# dsp_board_power_amplifier.net
KiCad netlist of a schematic drawn in EAGLE
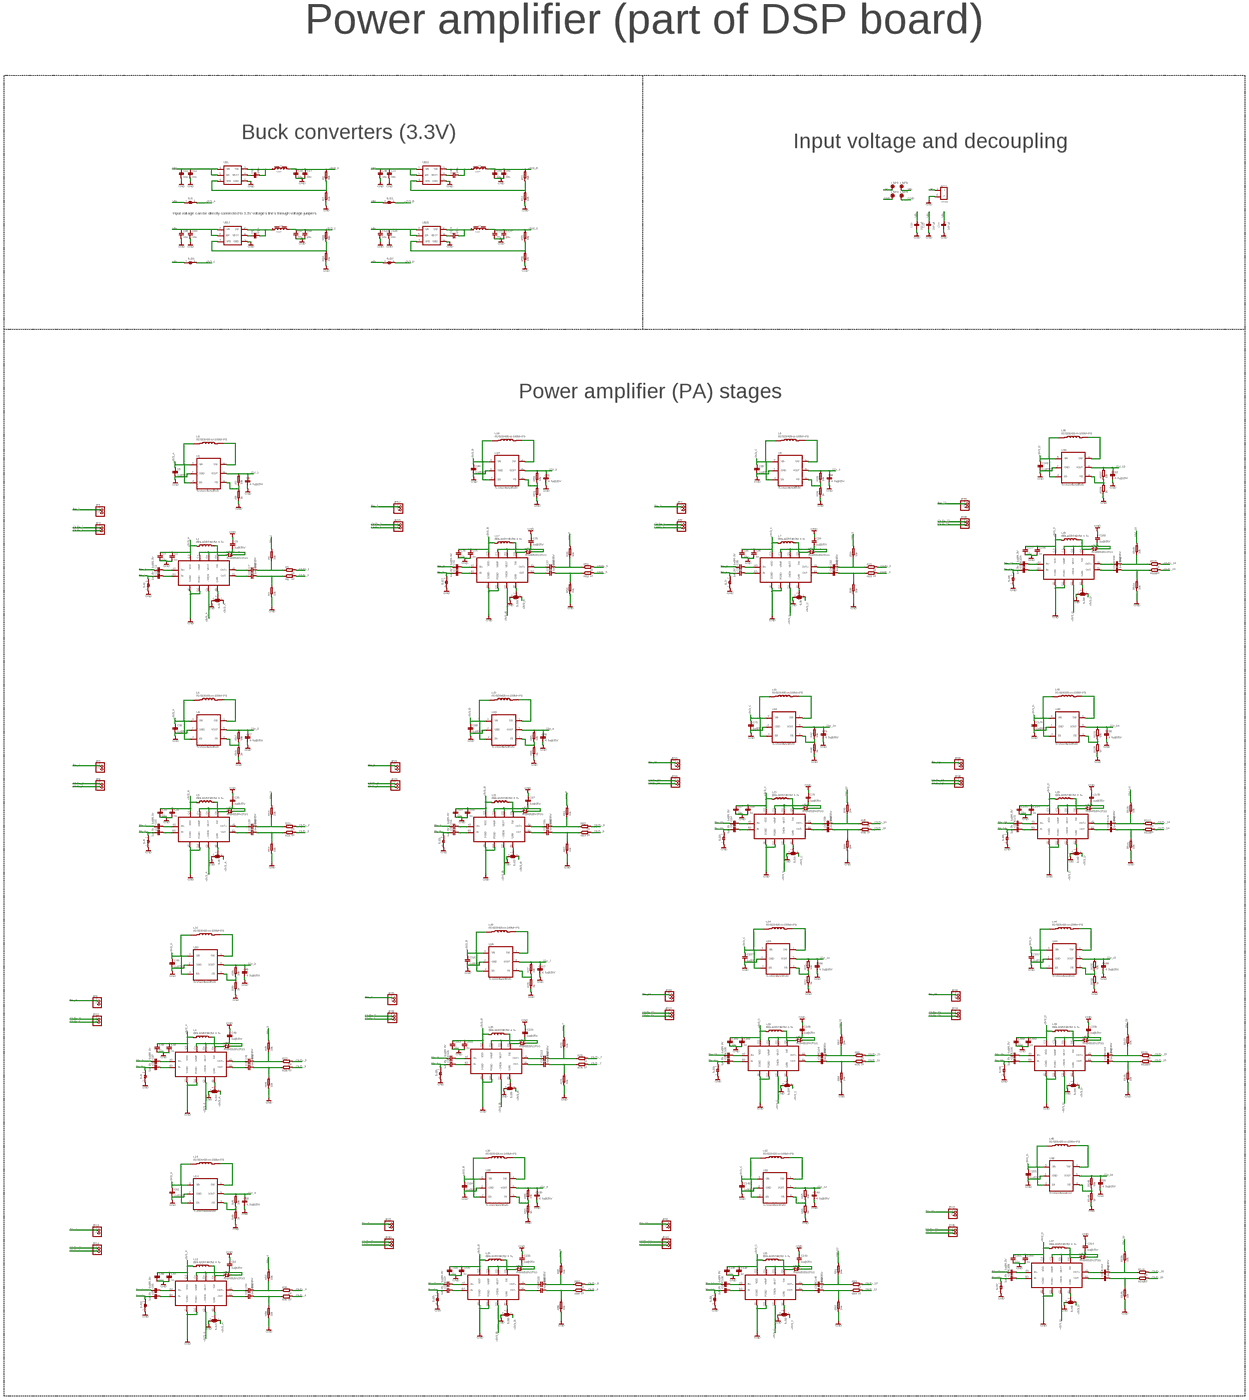
[diagram p0: schematic, sheet 1, overview]
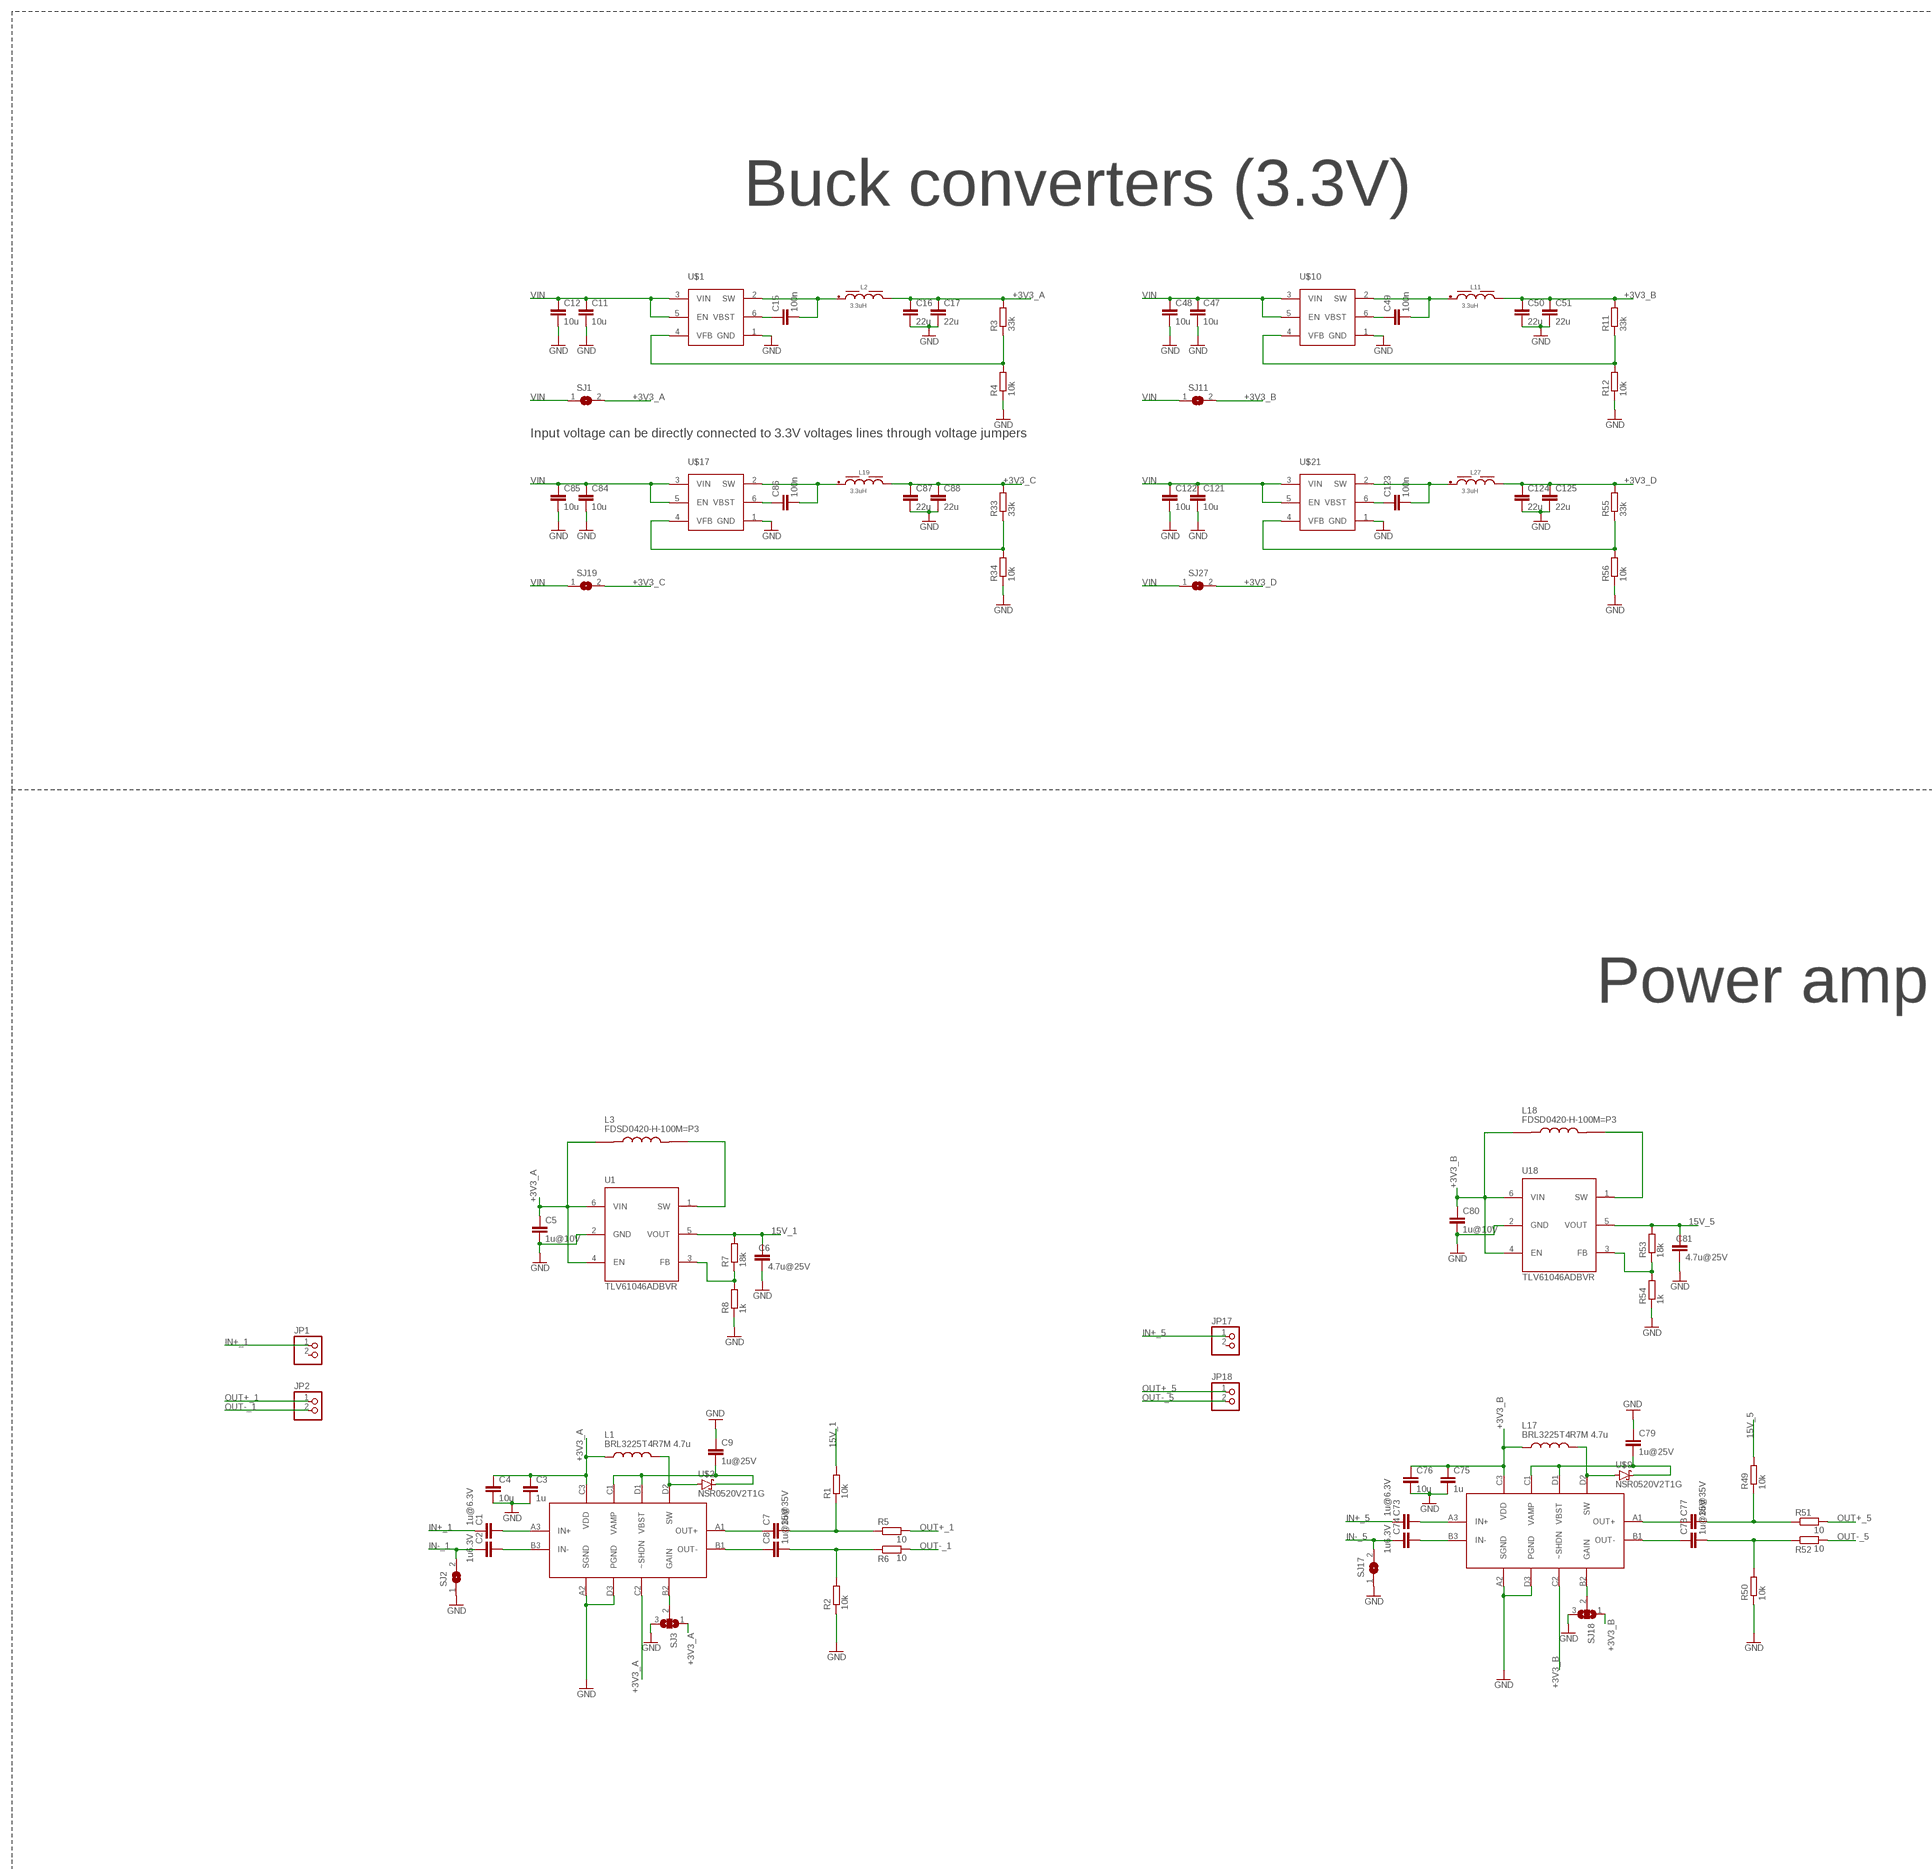
[diagram p1: schematic, sheet 1, part 1 of 6]
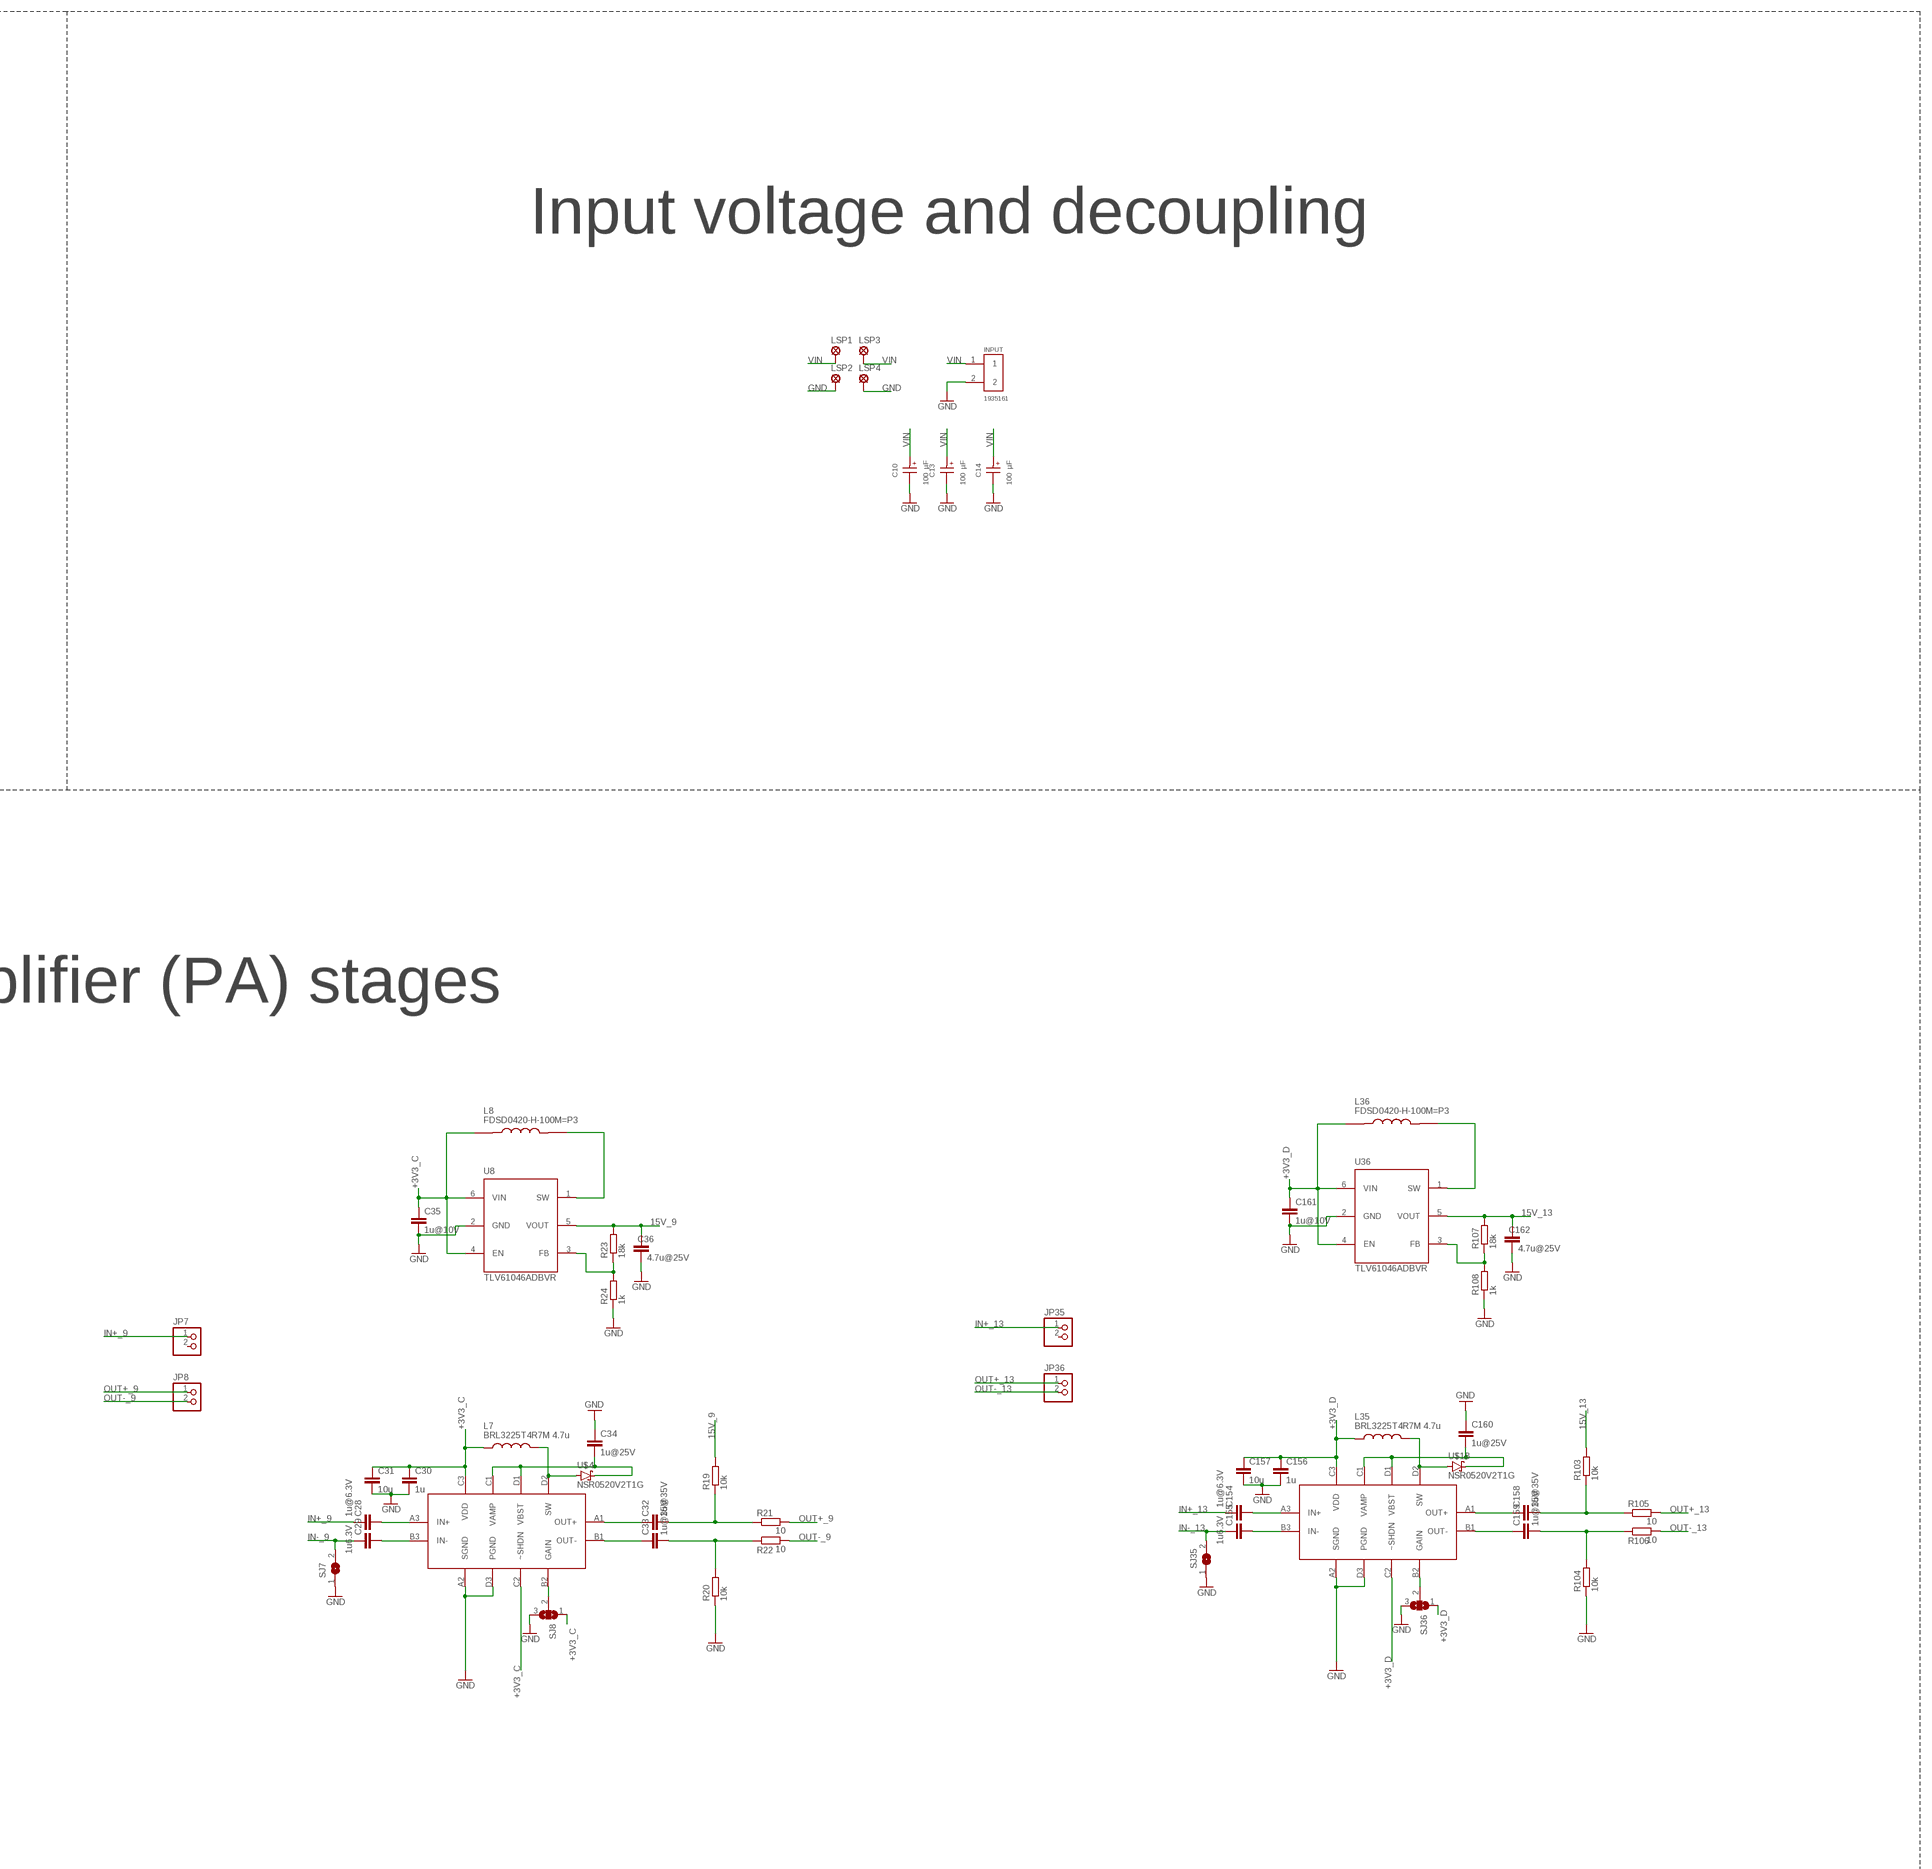
[diagram p2: schematic, sheet 1, part 2 of 6]
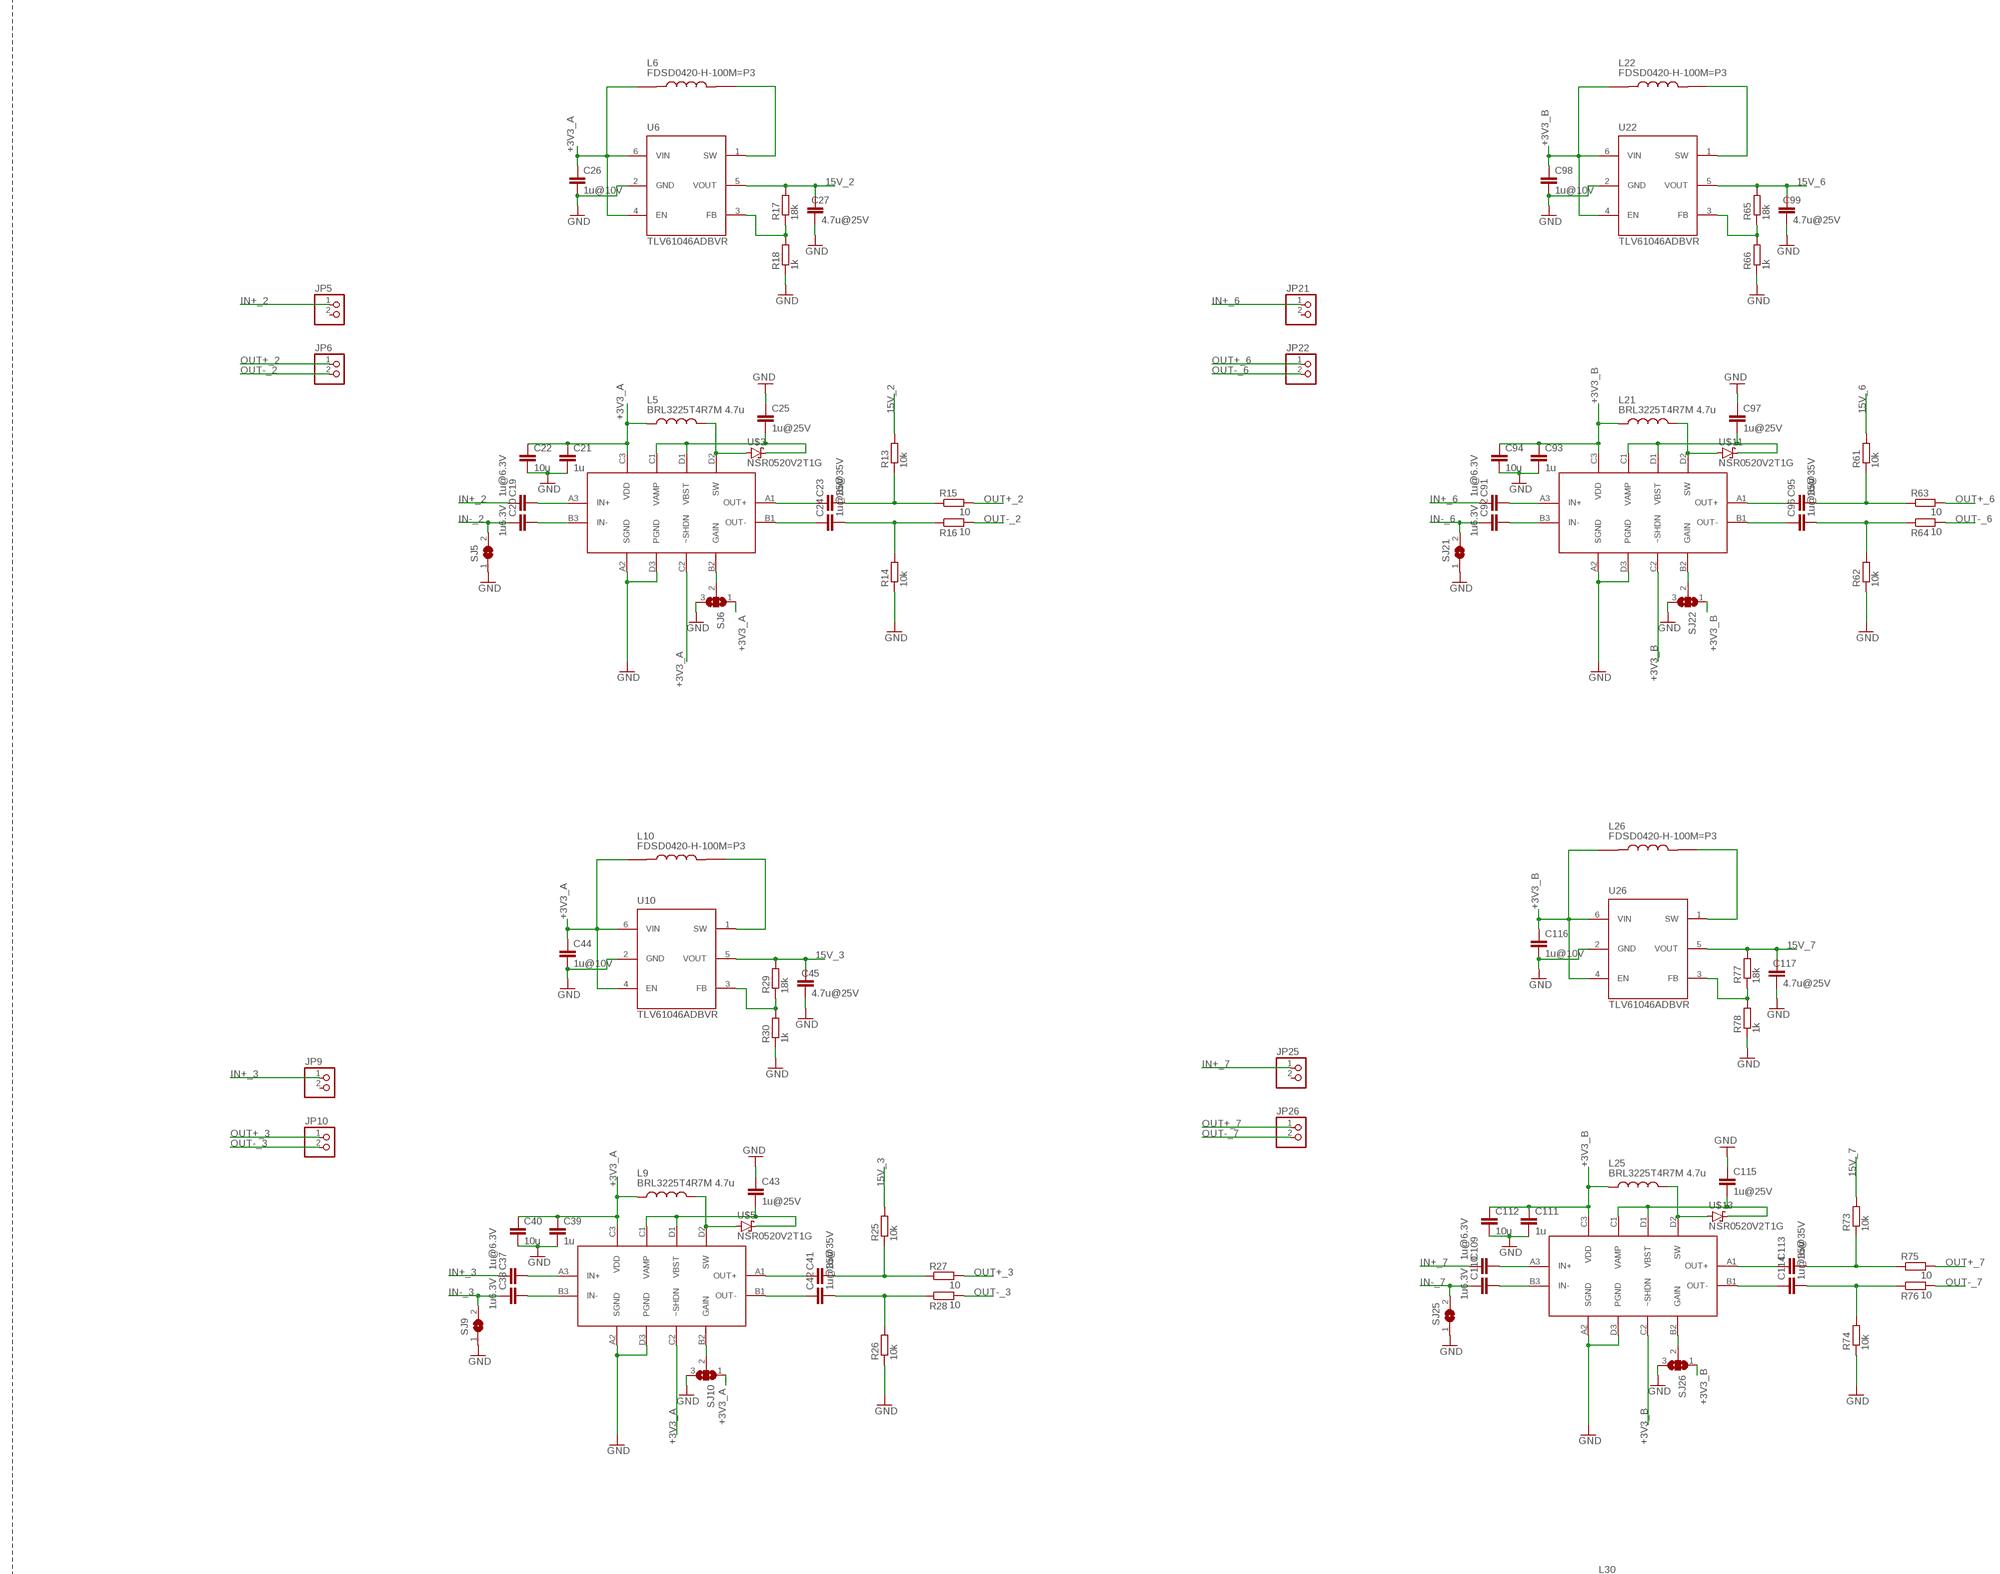
[diagram p3: schematic, sheet 1, part 3 of 6]
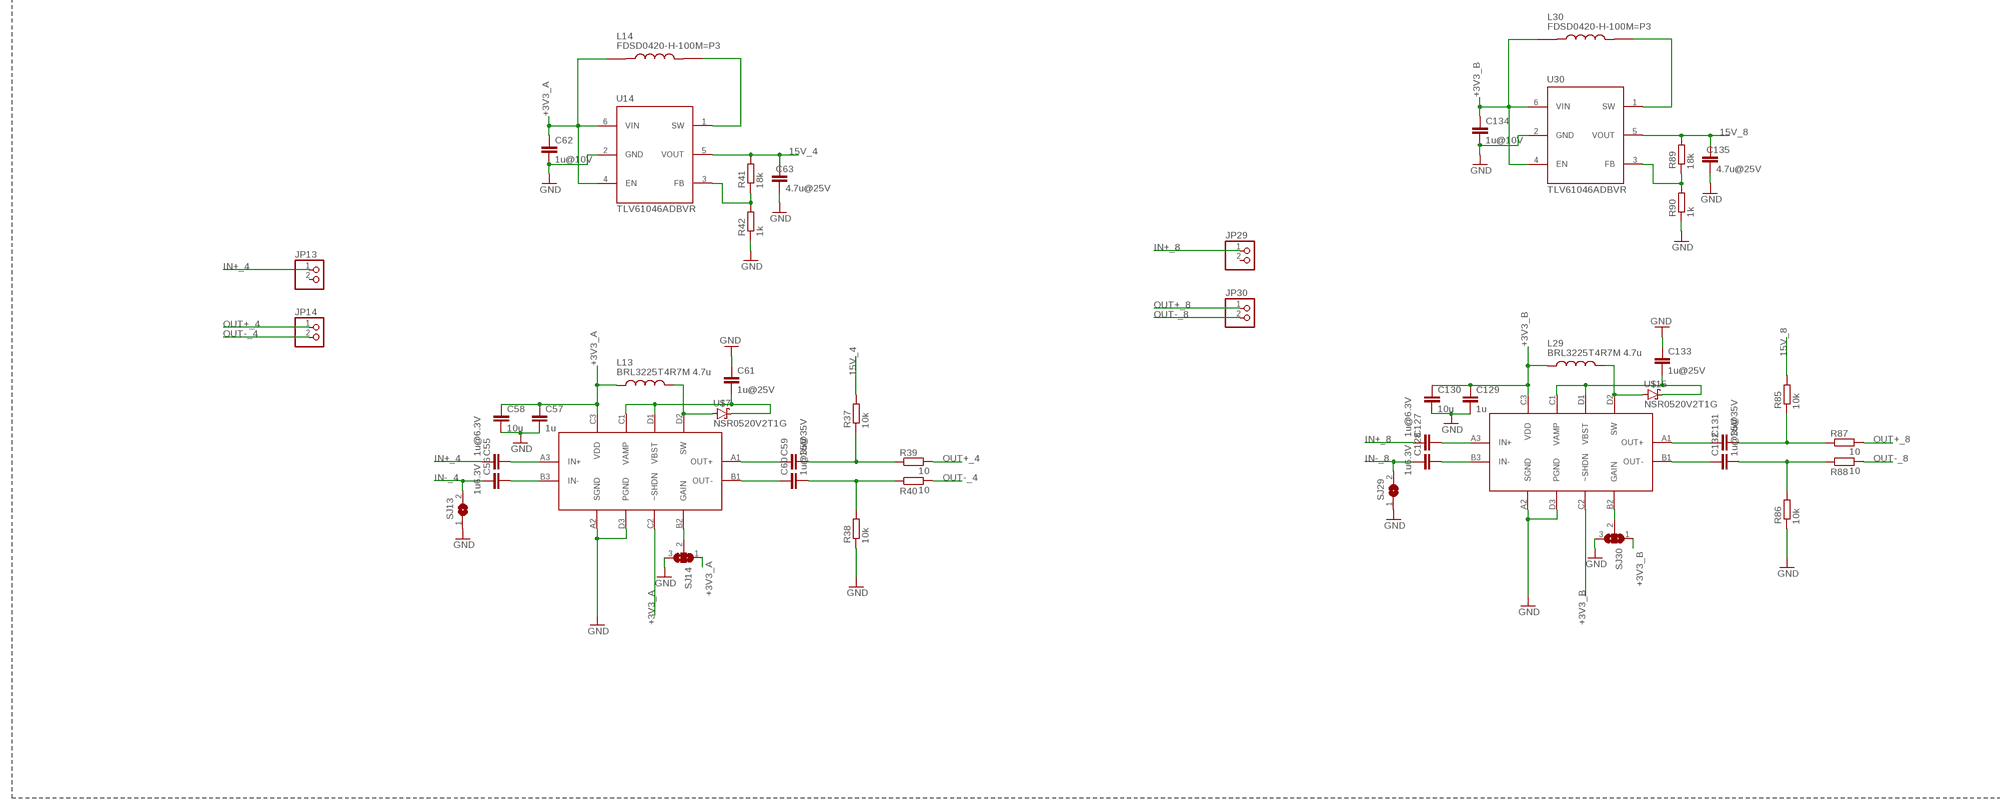
[diagram p4: schematic, sheet 1, part 4 of 6]
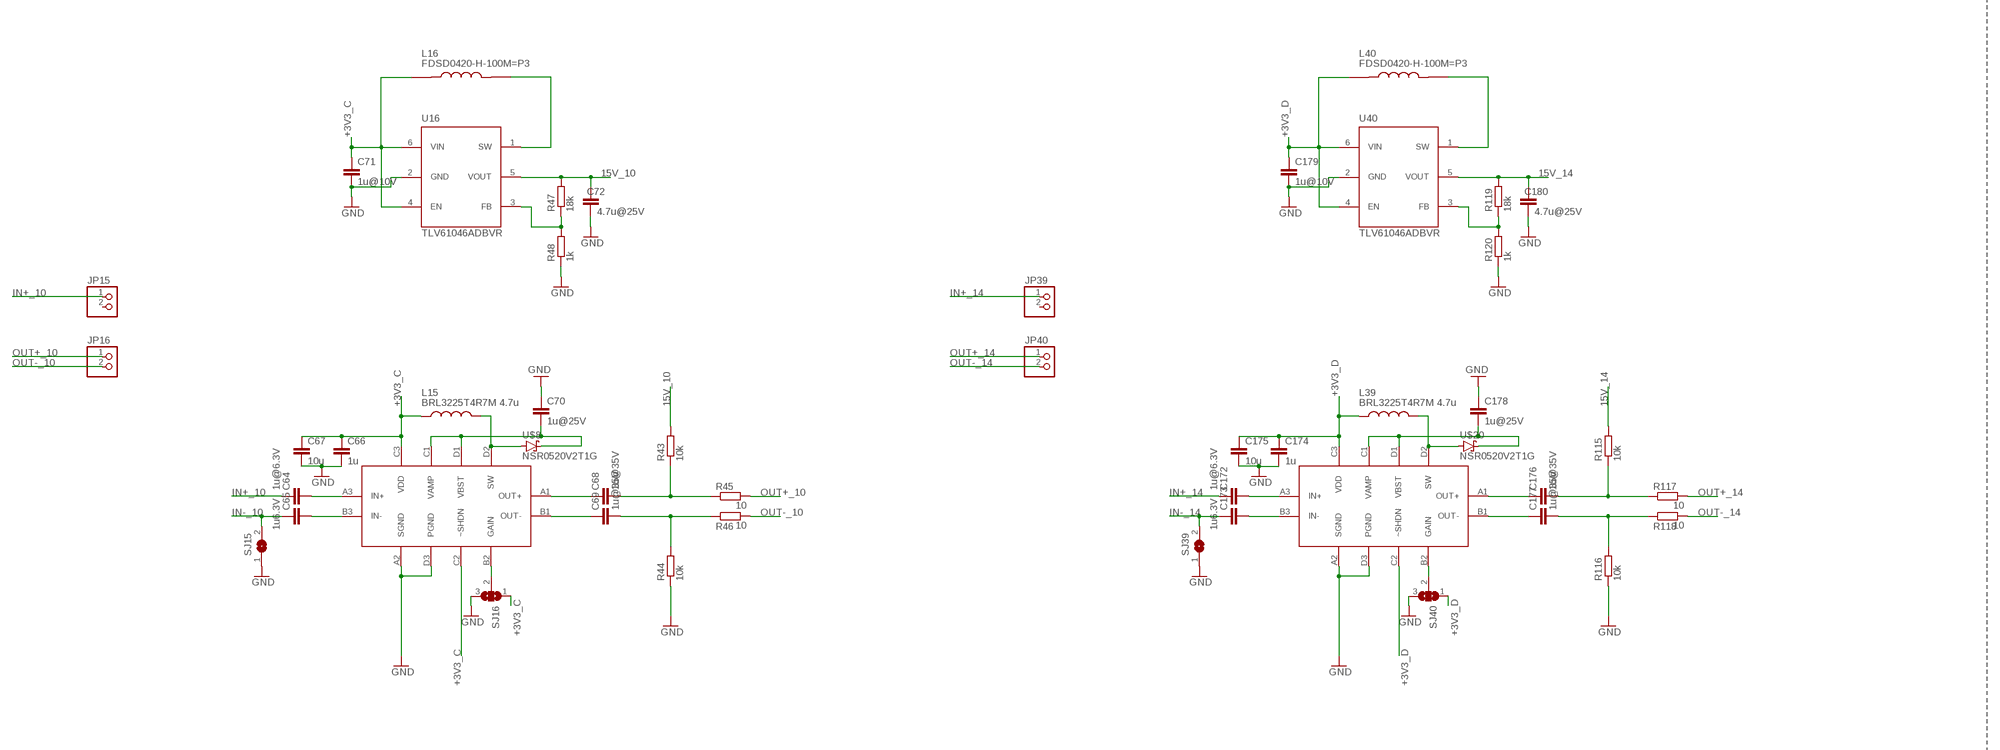
[diagram p5: schematic, sheet 1, part 5 of 6]
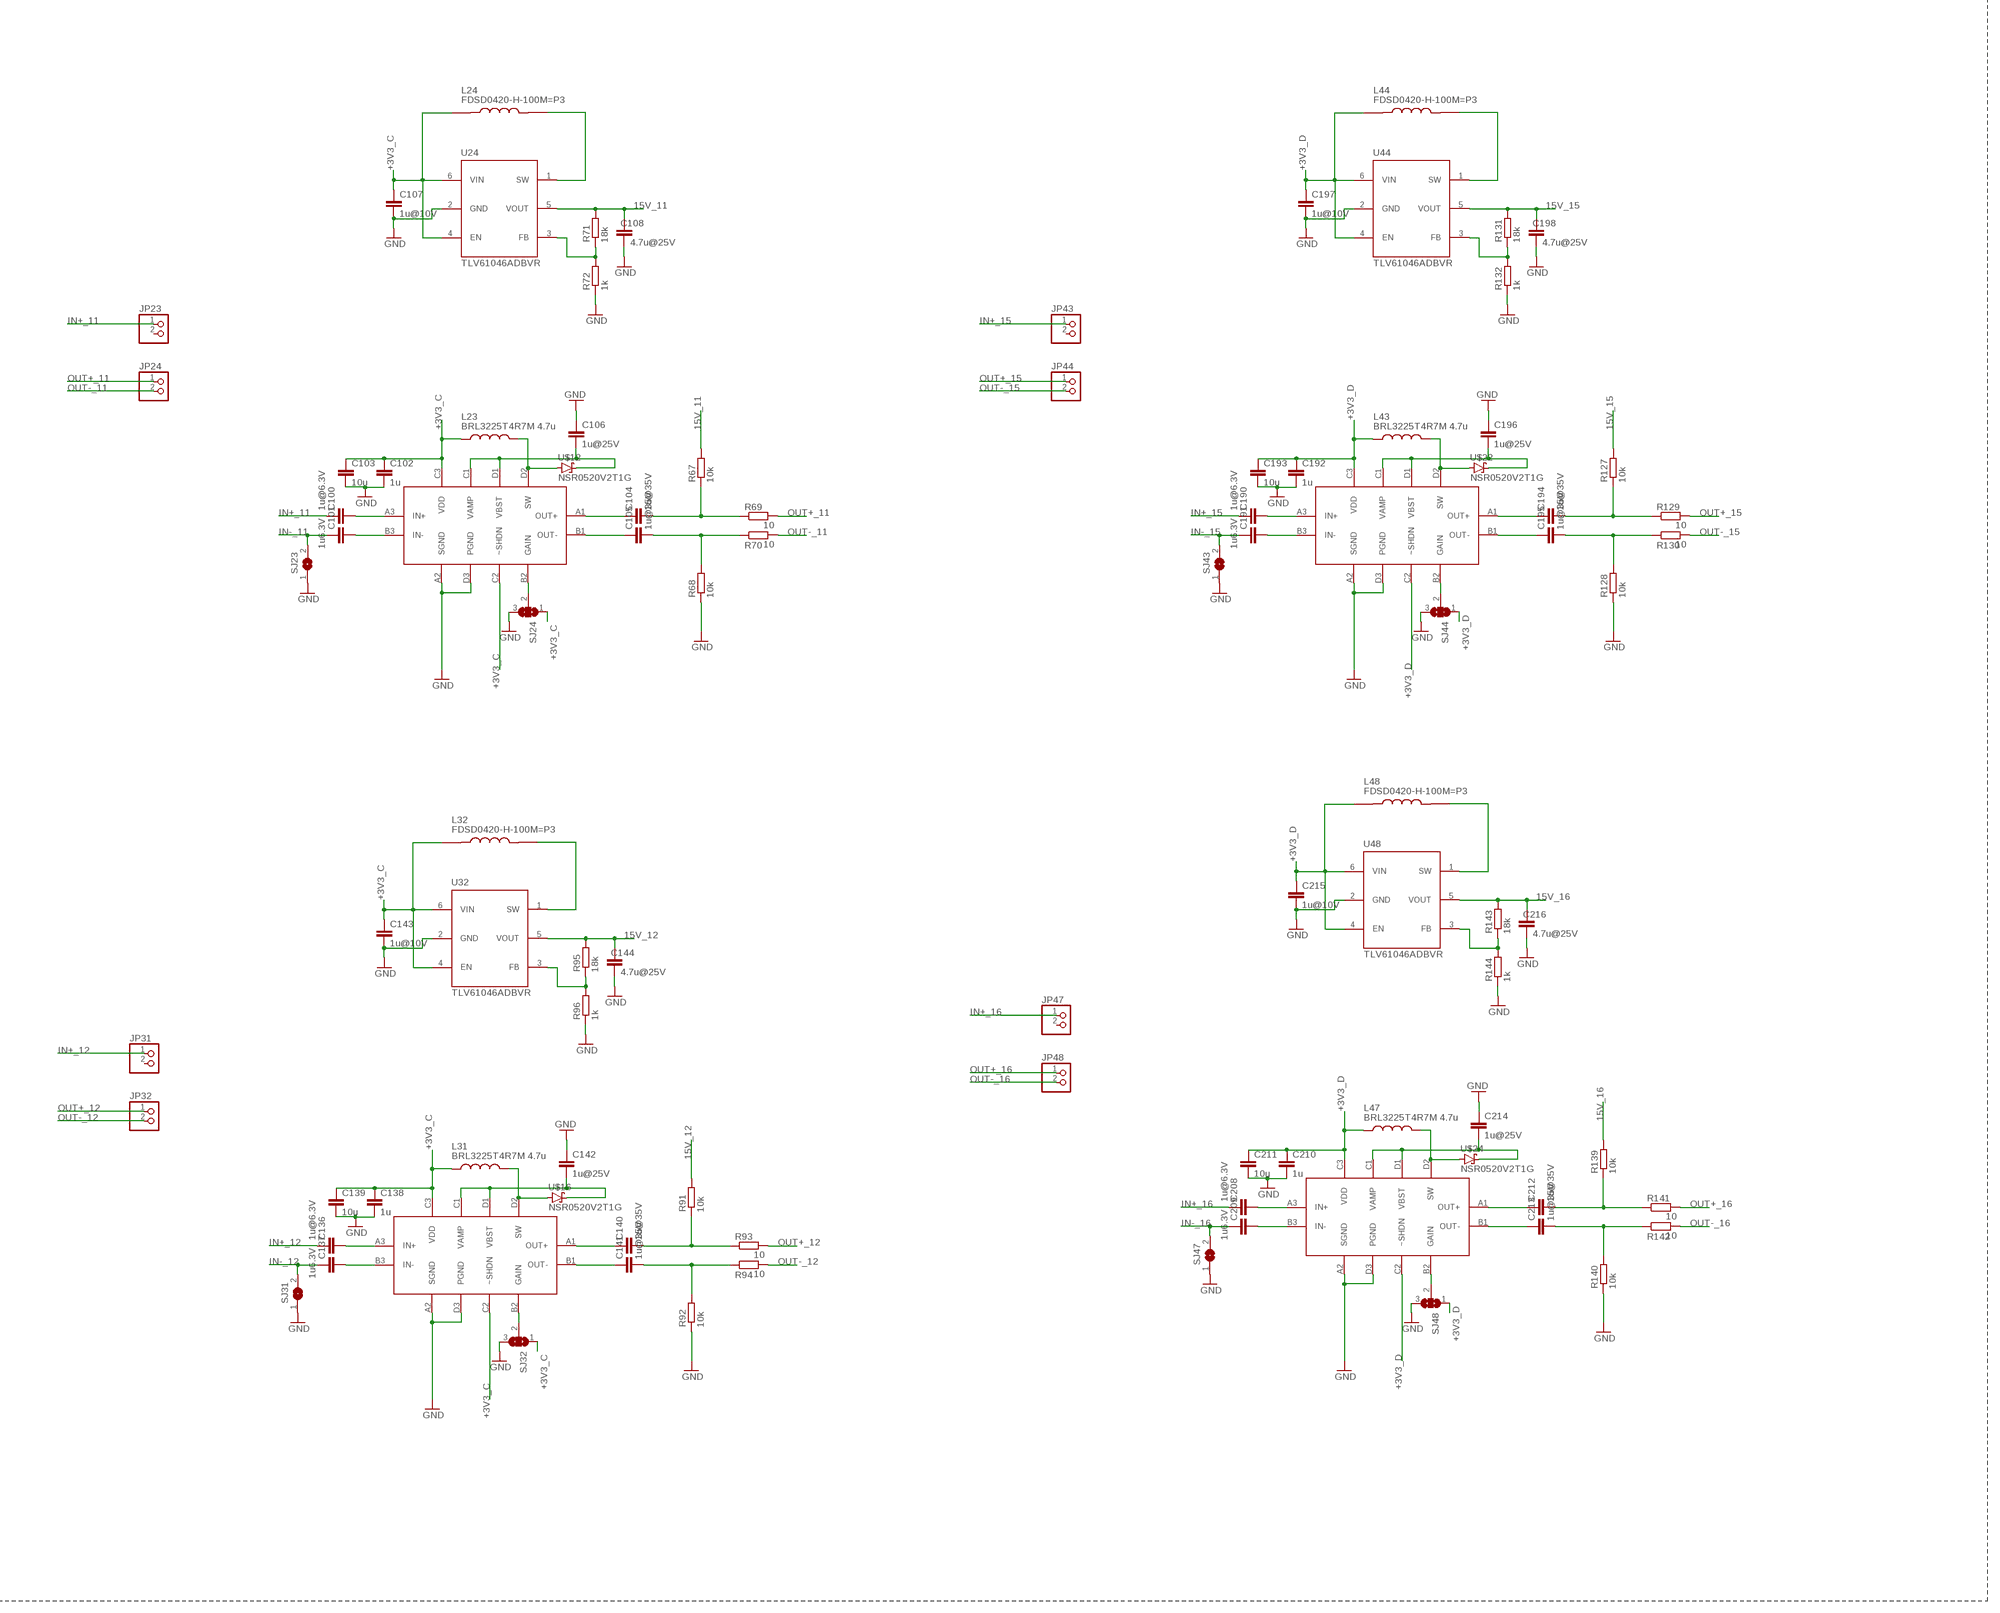
[diagram p6: schematic, sheet 1, part 6 of 6]

(export (version "E")
  (design (tool "Eeschema 10.0.6"))
  (components
    (comp (ref "C1")
      (value "1u@6.3V")
      (footprint "eagle-import:C0805")
      (libsource (lib "eagle-import") (part "C-EUC0805"))
    )
    (comp (ref "C2")
      (value "1u6.3V")
      (footprint "eagle-import:C0805")
      (libsource (lib "eagle-import") (part "C-EUC0805"))
    )
    (comp (ref "C3")
      (value "1u")
      (footprint "eagle-import:C0603")
      (libsource (lib "eagle-import") (part "C-EUC0603"))
    )
    (comp (ref "C4")
      (value "10u")
      (footprint "eagle-import:C0805")
      (libsource (lib "eagle-import") (part "C-EUC0805"))
    )
    (comp (ref "C5")
      (value "1u@10V")
      (footprint "eagle-import:C0603")
      (libsource (lib "eagle-import") (part "C-EUC0603"))
    )
    (comp (ref "C6")
      (value "4.7u@25V")
      (footprint "eagle-import:C0603")
      (libsource (lib "eagle-import") (part "C-EUC0603"))
    )
    (comp (ref "C7")
      (value "1u@35V")
      (footprint "eagle-import:C0603")
      (libsource (lib "eagle-import") (part "C-EUC0603"))
    )
    (comp (ref "C8")
      (value "1u@35V")
      (footprint "eagle-import:C0603")
      (libsource (lib "eagle-import") (part "C-EUC0603"))
    )
    (comp (ref "C9")
      (value "1u@25V")
      (footprint "eagle-import:C0603")
      (libsource (lib "eagle-import") (part "C-EUC0603"))
    )
    (comp (ref "C10")
      (value "100 µF")
      (footprint "eagle-import:WCAP-ASLU_6.3X7.7(DXL)")
      (libsource (lib "eagle-import") (part "WCAP-ASLU_6.3X7.7_865090445008"))
    )
    (comp (ref "C11")
      (value "10u")
      (footprint "eagle-import:C0805")
      (libsource (lib "eagle-import") (part "C-EUC0805"))
    )
    (comp (ref "C12")
      (value "10u")
      (footprint "eagle-import:C0805")
      (libsource (lib "eagle-import") (part "C-EUC0805"))
    )
    (comp (ref "C13")
      (value "100 µF")
      (footprint "eagle-import:WCAP-ASLU_6.3X7.7(DXL)")
      (libsource (lib "eagle-import") (part "WCAP-ASLU_6.3X7.7_865090445008"))
    )
    (comp (ref "C14")
      (value "100 µF")
      (footprint "eagle-import:WCAP-ASLU_6.3X7.7(DXL)")
      (libsource (lib "eagle-import") (part "WCAP-ASLU_6.3X7.7_865090445008"))
    )
    (comp (ref "C15")
      (value "100n")
      (footprint "eagle-import:C0603")
      (libsource (lib "eagle-import") (part "C-EUC0603"))
    )
    (comp (ref "C16")
      (value "22u")
      (footprint "eagle-import:C1206")
      (libsource (lib "eagle-import") (part "C-EUC1206"))
    )
    (comp (ref "C17")
      (value "22u")
      (footprint "eagle-import:C1206")
      (libsource (lib "eagle-import") (part "C-EUC1206"))
    )
    (comp (ref "C19")
      (value "1u@6.3V")
      (footprint "eagle-import:C0805")
      (libsource (lib "eagle-import") (part "C-EUC0805"))
    )
    (comp (ref "C20")
      (value "1u6.3V")
      (footprint "eagle-import:C0805")
      (libsource (lib "eagle-import") (part "C-EUC0805"))
    )
    (comp (ref "C21")
      (value "1u")
      (footprint "eagle-import:C0603")
      (libsource (lib "eagle-import") (part "C-EUC0603"))
    )
    (comp (ref "C22")
      (value "10u")
      (footprint "eagle-import:C0805")
      (libsource (lib "eagle-import") (part "C-EUC0805"))
    )
    (comp (ref "C23")
      (value "1u@35V")
      (footprint "eagle-import:C0603")
      (libsource (lib "eagle-import") (part "C-EUC0603"))
    )
    (comp (ref "C24")
      (value "1u@35V")
      (footprint "eagle-import:C0603")
      (libsource (lib "eagle-import") (part "C-EUC0603"))
    )
    (comp (ref "C25")
      (value "1u@25V")
      (footprint "eagle-import:C0603")
      (libsource (lib "eagle-import") (part "C-EUC0603"))
    )
    (comp (ref "C26")
      (value "1u@10V")
      (footprint "eagle-import:C0603")
      (libsource (lib "eagle-import") (part "C-EUC0603"))
    )
    (comp (ref "C27")
      (value "4.7u@25V")
      (footprint "eagle-import:C0603")
      (libsource (lib "eagle-import") (part "C-EUC0603"))
    )
    (comp (ref "C28")
      (value "1u@6.3V")
      (footprint "eagle-import:C0805")
      (libsource (lib "eagle-import") (part "C-EUC0805"))
    )
    (comp (ref "C29")
      (value "1u6.3V")
      (footprint "eagle-import:C0805")
      (libsource (lib "eagle-import") (part "C-EUC0805"))
    )
    (comp (ref "C30")
      (value "1u")
      (footprint "eagle-import:C0603")
      (libsource (lib "eagle-import") (part "C-EUC0603"))
    )
    (comp (ref "C31")
      (value "10u")
      (footprint "eagle-import:C0805")
      (libsource (lib "eagle-import") (part "C-EUC0805"))
    )
    (comp (ref "C32")
      (value "1u@35V")
      (footprint "eagle-import:C0603")
      (libsource (lib "eagle-import") (part "C-EUC0603"))
    )
    (comp (ref "C33")
      (value "1u@35V")
      (footprint "eagle-import:C0603")
      (libsource (lib "eagle-import") (part "C-EUC0603"))
    )
    (comp (ref "C34")
      (value "1u@25V")
      (footprint "eagle-import:C0603")
      (libsource (lib "eagle-import") (part "C-EUC0603"))
    )
    (comp (ref "C35")
      (value "1u@10V")
      (footprint "eagle-import:C0603")
      (libsource (lib "eagle-import") (part "C-EUC0603"))
    )
    (comp (ref "C36")
      (value "4.7u@25V")
      (footprint "eagle-import:C0603")
      (libsource (lib "eagle-import") (part "C-EUC0603"))
    )
    (comp (ref "C37")
      (value "1u@6.3V")
      (footprint "eagle-import:C0805")
      (libsource (lib "eagle-import") (part "C-EUC0805"))
    )
    (comp (ref "C38")
      (value "1u6.3V")
      (footprint "eagle-import:C0805")
      (libsource (lib "eagle-import") (part "C-EUC0805"))
    )
    (comp (ref "C39")
      (value "1u")
      (footprint "eagle-import:C0603")
      (libsource (lib "eagle-import") (part "C-EUC0603"))
    )
    (comp (ref "C40")
      (value "10u")
      (footprint "eagle-import:C0805")
      (libsource (lib "eagle-import") (part "C-EUC0805"))
    )
    (comp (ref "C41")
      (value "1u@35V")
      (footprint "eagle-import:C0603")
      (libsource (lib "eagle-import") (part "C-EUC0603"))
    )
    (comp (ref "C42")
      (value "1u@35V")
      (footprint "eagle-import:C0603")
      (libsource (lib "eagle-import") (part "C-EUC0603"))
    )
    (comp (ref "C43")
      (value "1u@25V")
      (footprint "eagle-import:C0603")
      (libsource (lib "eagle-import") (part "C-EUC0603"))
    )
    (comp (ref "C44")
      (value "1u@10V")
      (footprint "eagle-import:C0603")
      (libsource (lib "eagle-import") (part "C-EUC0603"))
    )
    (comp (ref "C45")
      (value "4.7u@25V")
      (footprint "eagle-import:C0603")
      (libsource (lib "eagle-import") (part "C-EUC0603"))
    )
    (comp (ref "C47")
      (value "10u")
      (footprint "eagle-import:C0805")
      (libsource (lib "eagle-import") (part "C-EUC0805"))
    )
    (comp (ref "C48")
      (value "10u")
      (footprint "eagle-import:C0805")
      (libsource (lib "eagle-import") (part "C-EUC0805"))
    )
    (comp (ref "C49")
      (value "100n")
      (footprint "eagle-import:C0603")
      (libsource (lib "eagle-import") (part "C-EUC0603"))
    )
    (comp (ref "C50")
      (value "22u")
      (footprint "eagle-import:C1206")
      (libsource (lib "eagle-import") (part "C-EUC1206"))
    )
    (comp (ref "C51")
      (value "22u")
      (footprint "eagle-import:C1206")
      (libsource (lib "eagle-import") (part "C-EUC1206"))
    )
    (comp (ref "C55")
      (value "1u@6.3V")
      (footprint "eagle-import:C0805")
      (libsource (lib "eagle-import") (part "C-EUC0805"))
    )
    (comp (ref "C56")
      (value "1u6.3V")
      (footprint "eagle-import:C0805")
      (libsource (lib "eagle-import") (part "C-EUC0805"))
    )
    (comp (ref "C57")
      (value "1u")
      (footprint "eagle-import:C0603")
      (libsource (lib "eagle-import") (part "C-EUC0603"))
    )
    (comp (ref "C58")
      (value "10u")
      (footprint "eagle-import:C0805")
      (libsource (lib "eagle-import") (part "C-EUC0805"))
    )
    (comp (ref "C59")
      (value "1u@35V")
      (footprint "eagle-import:C0603")
      (libsource (lib "eagle-import") (part "C-EUC0603"))
    )
    (comp (ref "C60")
      (value "1u@35V")
      (footprint "eagle-import:C0603")
      (libsource (lib "eagle-import") (part "C-EUC0603"))
    )
    (comp (ref "C61")
      (value "1u@25V")
      (footprint "eagle-import:C0603")
      (libsource (lib "eagle-import") (part "C-EUC0603"))
    )
    (comp (ref "C62")
      (value "1u@10V")
      (footprint "eagle-import:C0603")
      (libsource (lib "eagle-import") (part "C-EUC0603"))
    )
    (comp (ref "C63")
      (value "4.7u@25V")
      (footprint "eagle-import:C0603")
      (libsource (lib "eagle-import") (part "C-EUC0603"))
    )
    (comp (ref "C64")
      (value "1u@6.3V")
      (footprint "eagle-import:C0805")
      (libsource (lib "eagle-import") (part "C-EUC0805"))
    )
    (comp (ref "C65")
      (value "1u6.3V")
      (footprint "eagle-import:C0805")
      (libsource (lib "eagle-import") (part "C-EUC0805"))
    )
    (comp (ref "C66")
      (value "1u")
      (footprint "eagle-import:C0603")
      (libsource (lib "eagle-import") (part "C-EUC0603"))
    )
    (comp (ref "C67")
      (value "10u")
      (footprint "eagle-import:C0805")
      (libsource (lib "eagle-import") (part "C-EUC0805"))
    )
    (comp (ref "C68")
      (value "1u@35V")
      (footprint "eagle-import:C0603")
      (libsource (lib "eagle-import") (part "C-EUC0603"))
    )
    (comp (ref "C69")
      (value "1u@35V")
      (footprint "eagle-import:C0603")
      (libsource (lib "eagle-import") (part "C-EUC0603"))
    )
    (comp (ref "C70")
      (value "1u@25V")
      (footprint "eagle-import:C0603")
      (libsource (lib "eagle-import") (part "C-EUC0603"))
    )
    (comp (ref "C71")
      (value "1u@10V")
      (footprint "eagle-import:C0603")
      (libsource (lib "eagle-import") (part "C-EUC0603"))
    )
    (comp (ref "C72")
      (value "4.7u@25V")
      (footprint "eagle-import:C0603")
      (libsource (lib "eagle-import") (part "C-EUC0603"))
    )
    (comp (ref "C73")
      (value "1u@6.3V")
      (footprint "eagle-import:C0805")
      (libsource (lib "eagle-import") (part "C-EUC0805"))
    )
    (comp (ref "C74")
      (value "1u6.3V")
      (footprint "eagle-import:C0805")
      (libsource (lib "eagle-import") (part "C-EUC0805"))
    )
    (comp (ref "C75")
      (value "1u")
      (footprint "eagle-import:C0603")
      (libsource (lib "eagle-import") (part "C-EUC0603"))
    )
    (comp (ref "C76")
      (value "10u")
      (footprint "eagle-import:C0805")
      (libsource (lib "eagle-import") (part "C-EUC0805"))
    )
    (comp (ref "C77")
      (value "1u@35V")
      (footprint "eagle-import:C0603")
      (libsource (lib "eagle-import") (part "C-EUC0603"))
    )
    (comp (ref "C78")
      (value "1u@35V")
      (footprint "eagle-import:C0603")
      (libsource (lib "eagle-import") (part "C-EUC0603"))
    )
    (comp (ref "C79")
      (value "1u@25V")
      (footprint "eagle-import:C0603")
      (libsource (lib "eagle-import") (part "C-EUC0603"))
    )
    (comp (ref "C80")
      (value "1u@10V")
      (footprint "eagle-import:C0603")
      (libsource (lib "eagle-import") (part "C-EUC0603"))
    )
    (comp (ref "C81")
      (value "4.7u@25V")
      (footprint "eagle-import:C0603")
      (libsource (lib "eagle-import") (part "C-EUC0603"))
    )
    (comp (ref "C84")
      (value "10u")
      (footprint "eagle-import:C0805")
      (libsource (lib "eagle-import") (part "C-EUC0805"))
    )
    (comp (ref "C85")
      (value "10u")
      (footprint "eagle-import:C0805")
      (libsource (lib "eagle-import") (part "C-EUC0805"))
    )
    (comp (ref "C86")
      (value "100n")
      (footprint "eagle-import:C0603")
      (libsource (lib "eagle-import") (part "C-EUC0603"))
    )
    (comp (ref "C87")
      (value "22u")
      (footprint "eagle-import:C1206")
      (libsource (lib "eagle-import") (part "C-EUC1206"))
    )
    (comp (ref "C88")
      (value "22u")
      (footprint "eagle-import:C1206")
      (libsource (lib "eagle-import") (part "C-EUC1206"))
    )
    (comp (ref "C91")
      (value "1u@6.3V")
      (footprint "eagle-import:C0805")
      (libsource (lib "eagle-import") (part "C-EUC0805"))
    )
    (comp (ref "C92")
      (value "1u6.3V")
      (footprint "eagle-import:C0805")
      (libsource (lib "eagle-import") (part "C-EUC0805"))
    )
    (comp (ref "C93")
      (value "1u")
      (footprint "eagle-import:C0603")
      (libsource (lib "eagle-import") (part "C-EUC0603"))
    )
    (comp (ref "C94")
      (value "10u")
      (footprint "eagle-import:C0805")
      (libsource (lib "eagle-import") (part "C-EUC0805"))
    )
    (comp (ref "C95")
      (value "1u@35V")
      (footprint "eagle-import:C0603")
      (libsource (lib "eagle-import") (part "C-EUC0603"))
    )
    (comp (ref "C96")
      (value "1u@35V")
      (footprint "eagle-import:C0603")
      (libsource (lib "eagle-import") (part "C-EUC0603"))
    )
    (comp (ref "C97")
      (value "1u@25V")
      (footprint "eagle-import:C0603")
      (libsource (lib "eagle-import") (part "C-EUC0603"))
    )
    (comp (ref "C98")
      (value "1u@10V")
      (footprint "eagle-import:C0603")
      (libsource (lib "eagle-import") (part "C-EUC0603"))
    )
    (comp (ref "C99")
      (value "4.7u@25V")
      (footprint "eagle-import:C0603")
      (libsource (lib "eagle-import") (part "C-EUC0603"))
    )
    (comp (ref "C100")
      (value "1u@6.3V")
      (footprint "eagle-import:C0805")
      (libsource (lib "eagle-import") (part "C-EUC0805"))
    )
    (comp (ref "C101")
      (value "1u6.3V")
      (footprint "eagle-import:C0805")
      (libsource (lib "eagle-import") (part "C-EUC0805"))
    )
    (comp (ref "C102")
      (value "1u")
      (footprint "eagle-import:C0603")
      (libsource (lib "eagle-import") (part "C-EUC0603"))
    )
    (comp (ref "C103")
      (value "10u")
      (footprint "eagle-import:C0805")
      (libsource (lib "eagle-import") (part "C-EUC0805"))
    )
    (comp (ref "C104")
      (value "1u@35V")
      (footprint "eagle-import:C0603")
      (libsource (lib "eagle-import") (part "C-EUC0603"))
    )
    (comp (ref "C105")
      (value "1u@35V")
      (footprint "eagle-import:C0603")
      (libsource (lib "eagle-import") (part "C-EUC0603"))
    )
    (comp (ref "C106")
      (value "1u@25V")
      (footprint "eagle-import:C0603")
      (libsource (lib "eagle-import") (part "C-EUC0603"))
    )
    (comp (ref "C107")
      (value "1u@10V")
      (footprint "eagle-import:C0603")
      (libsource (lib "eagle-import") (part "C-EUC0603"))
    )
    (comp (ref "C108")
      (value "4.7u@25V")
      (footprint "eagle-import:C0603")
      (libsource (lib "eagle-import") (part "C-EUC0603"))
    )
    (comp (ref "C109")
      (value "1u@6.3V")
      (footprint "eagle-import:C0805")
      (libsource (lib "eagle-import") (part "C-EUC0805"))
    )
    (comp (ref "C110")
      (value "1u6.3V")
      (footprint "eagle-import:C0805")
      (libsource (lib "eagle-import") (part "C-EUC0805"))
    )
    (comp (ref "C111")
      (value "1u")
      (footprint "eagle-import:C0603")
      (libsource (lib "eagle-import") (part "C-EUC0603"))
    )
    (comp (ref "C112")
      (value "10u")
      (footprint "eagle-import:C0805")
      (libsource (lib "eagle-import") (part "C-EUC0805"))
    )
    (comp (ref "C113")
      (value "1u@35V")
      (footprint "eagle-import:C0603")
      (libsource (lib "eagle-import") (part "C-EUC0603"))
    )
    (comp (ref "C114")
      (value "1u@35V")
      (footprint "eagle-import:C0603")
      (libsource (lib "eagle-import") (part "C-EUC0603"))
    )
    (comp (ref "C115")
      (value "1u@25V")
      (footprint "eagle-import:C0603")
      (libsource (lib "eagle-import") (part "C-EUC0603"))
    )
    (comp (ref "C116")
      (value "1u@10V")
      (footprint "eagle-import:C0603")
      (libsource (lib "eagle-import") (part "C-EUC0603"))
    )
    (comp (ref "C117")
      (value "4.7u@25V")
      (footprint "eagle-import:C0603")
      (libsource (lib "eagle-import") (part "C-EUC0603"))
    )
    (comp (ref "C121")
      (value "10u")
      (footprint "eagle-import:C0805")
      (libsource (lib "eagle-import") (part "C-EUC0805"))
    )
    (comp (ref "C122")
      (value "10u")
      (footprint "eagle-import:C0805")
      (libsource (lib "eagle-import") (part "C-EUC0805"))
    )
    (comp (ref "C123")
      (value "100n")
      (footprint "eagle-import:C0603")
      (libsource (lib "eagle-import") (part "C-EUC0603"))
    )
    (comp (ref "C124")
      (value "22u")
      (footprint "eagle-import:C1206")
      (libsource (lib "eagle-import") (part "C-EUC1206"))
    )
    (comp (ref "C125")
      (value "22u")
      (footprint "eagle-import:C1206")
      (libsource (lib "eagle-import") (part "C-EUC1206"))
    )
    (comp (ref "C127")
      (value "1u@6.3V")
      (footprint "eagle-import:C0805")
      (libsource (lib "eagle-import") (part "C-EUC0805"))
    )
    (comp (ref "C128")
      (value "1u6.3V")
      (footprint "eagle-import:C0805")
      (libsource (lib "eagle-import") (part "C-EUC0805"))
    )
    (comp (ref "C129")
      (value "1u")
      (footprint "eagle-import:C0603")
      (libsource (lib "eagle-import") (part "C-EUC0603"))
    )
    (comp (ref "C130")
      (value "10u")
      (footprint "eagle-import:C0805")
      (libsource (lib "eagle-import") (part "C-EUC0805"))
    )
    (comp (ref "C131")
      (value "1u@35V")
      (footprint "eagle-import:C0603")
      (libsource (lib "eagle-import") (part "C-EUC0603"))
    )
    (comp (ref "C132")
      (value "1u@35V")
      (footprint "eagle-import:C0603")
      (libsource (lib "eagle-import") (part "C-EUC0603"))
    )
    (comp (ref "C133")
      (value "1u@25V")
      (footprint "eagle-import:C0603")
      (libsource (lib "eagle-import") (part "C-EUC0603"))
    )
    (comp (ref "C134")
      (value "1u@10V")
      (footprint "eagle-import:C0603")
      (libsource (lib "eagle-import") (part "C-EUC0603"))
    )
    (comp (ref "C135")
      (value "4.7u@25V")
      (footprint "eagle-import:C0603")
      (libsource (lib "eagle-import") (part "C-EUC0603"))
    )
    (comp (ref "C136")
      (value "1u@6.3V")
      (footprint "eagle-import:C0805")
      (libsource (lib "eagle-import") (part "C-EUC0805"))
    )
    (comp (ref "C137")
      (value "1u6.3V")
      (footprint "eagle-import:C0805")
      (libsource (lib "eagle-import") (part "C-EUC0805"))
    )
    (comp (ref "C138")
      (value "1u")
      (footprint "eagle-import:C0603")
      (libsource (lib "eagle-import") (part "C-EUC0603"))
    )
    (comp (ref "C139")
      (value "10u")
      (footprint "eagle-import:C0805")
      (libsource (lib "eagle-import") (part "C-EUC0805"))
    )
    (comp (ref "C140")
      (value "1u@35V")
      (footprint "eagle-import:C0603")
      (libsource (lib "eagle-import") (part "C-EUC0603"))
    )
    (comp (ref "C141")
      (value "1u@35V")
      (footprint "eagle-import:C0603")
      (libsource (lib "eagle-import") (part "C-EUC0603"))
    )
    (comp (ref "C142")
      (value "1u@25V")
      (footprint "eagle-import:C0603")
      (libsource (lib "eagle-import") (part "C-EUC0603"))
    )
    (comp (ref "C143")
      (value "1u@10V")
      (footprint "eagle-import:C0603")
      (libsource (lib "eagle-import") (part "C-EUC0603"))
    )
    (comp (ref "C144")
      (value "4.7u@25V")
      (footprint "eagle-import:C0603")
      (libsource (lib "eagle-import") (part "C-EUC0603"))
    )
    (comp (ref "C154")
      (value "1u@6.3V")
      (footprint "eagle-import:C0805")
      (libsource (lib "eagle-import") (part "C-EUC0805"))
    )
    (comp (ref "C155")
      (value "1u6.3V")
      (footprint "eagle-import:C0805")
      (libsource (lib "eagle-import") (part "C-EUC0805"))
    )
    (comp (ref "C156")
      (value "1u")
      (footprint "eagle-import:C0603")
      (libsource (lib "eagle-import") (part "C-EUC0603"))
    )
    (comp (ref "C157")
      (value "10u")
      (footprint "eagle-import:C0805")
      (libsource (lib "eagle-import") (part "C-EUC0805"))
    )
    (comp (ref "C158")
      (value "1u@35V")
      (footprint "eagle-import:C0603")
      (libsource (lib "eagle-import") (part "C-EUC0603"))
    )
    (comp (ref "C159")
      (value "1u@35V")
      (footprint "eagle-import:C0603")
      (libsource (lib "eagle-import") (part "C-EUC0603"))
    )
    (comp (ref "C160")
      (value "1u@25V")
      (footprint "eagle-import:C0603")
      (libsource (lib "eagle-import") (part "C-EUC0603"))
    )
    (comp (ref "C161")
      (value "1u@10V")
      (footprint "eagle-import:C0603")
      (libsource (lib "eagle-import") (part "C-EUC0603"))
    )
    (comp (ref "C162")
      (value "4.7u@25V")
      (footprint "eagle-import:C0603")
      (libsource (lib "eagle-import") (part "C-EUC0603"))
    )
    (comp (ref "C172")
      (value "1u@6.3V")
      (footprint "eagle-import:C0805")
      (libsource (lib "eagle-import") (part "C-EUC0805"))
    )
    (comp (ref "C173")
      (value "1u6.3V")
      (footprint "eagle-import:C0805")
      (libsource (lib "eagle-import") (part "C-EUC0805"))
    )
    (comp (ref "C174")
      (value "1u")
      (footprint "eagle-import:C0603")
      (libsource (lib "eagle-import") (part "C-EUC0603"))
    )
    (comp (ref "C175")
      (value "10u")
      (footprint "eagle-import:C0805")
      (libsource (lib "eagle-import") (part "C-EUC0805"))
    )
    (comp (ref "C176")
      (value "1u@35V")
      (footprint "eagle-import:C0603")
      (libsource (lib "eagle-import") (part "C-EUC0603"))
    )
    (comp (ref "C177")
      (value "1u@35V")
      (footprint "eagle-import:C0603")
      (libsource (lib "eagle-import") (part "C-EUC0603"))
    )
    (comp (ref "C178")
      (value "1u@25V")
      (footprint "eagle-import:C0603")
      (libsource (lib "eagle-import") (part "C-EUC0603"))
    )
    (comp (ref "C179")
      (value "1u@10V")
      (footprint "eagle-import:C0603")
      (libsource (lib "eagle-import") (part "C-EUC0603"))
    )
    (comp (ref "C180")
      (value "4.7u@25V")
      (footprint "eagle-import:C0603")
      (libsource (lib "eagle-import") (part "C-EUC0603"))
    )
    (comp (ref "C190")
      (value "1u@6.3V")
      (footprint "eagle-import:C0805")
      (libsource (lib "eagle-import") (part "C-EUC0805"))
    )
    (comp (ref "C191")
      (value "1u6.3V")
      (footprint "eagle-import:C0805")
      (libsource (lib "eagle-import") (part "C-EUC0805"))
    )
    (comp (ref "C192")
      (value "1u")
      (footprint "eagle-import:C0603")
      (libsource (lib "eagle-import") (part "C-EUC0603"))
    )
    (comp (ref "C193")
      (value "10u")
      (footprint "eagle-import:C0805")
      (libsource (lib "eagle-import") (part "C-EUC0805"))
    )
    (comp (ref "C194")
      (value "1u@35V")
      (footprint "eagle-import:C0603")
      (libsource (lib "eagle-import") (part "C-EUC0603"))
    )
    (comp (ref "C195")
      (value "1u@35V")
      (footprint "eagle-import:C0603")
      (libsource (lib "eagle-import") (part "C-EUC0603"))
    )
    (comp (ref "C196")
      (value "1u@25V")
      (footprint "eagle-import:C0603")
      (libsource (lib "eagle-import") (part "C-EUC0603"))
    )
    (comp (ref "C197")
      (value "1u@10V")
      (footprint "eagle-import:C0603")
      (libsource (lib "eagle-import") (part "C-EUC0603"))
    )
    (comp (ref "C198")
      (value "4.7u@25V")
      (footprint "eagle-import:C0603")
      (libsource (lib "eagle-import") (part "C-EUC0603"))
    )
    (comp (ref "C208")
      (value "1u@6.3V")
      (footprint "eagle-import:C0805")
      (libsource (lib "eagle-import") (part "C-EUC0805"))
    )
    (comp (ref "C209")
      (value "1u6.3V")
      (footprint "eagle-import:C0805")
      (libsource (lib "eagle-import") (part "C-EUC0805"))
    )
    (comp (ref "C210")
      (value "1u")
      (footprint "eagle-import:C0603")
      (libsource (lib "eagle-import") (part "C-EUC0603"))
    )
    (comp (ref "C211")
      (value "10u")
      (footprint "eagle-import:C0805")
      (libsource (lib "eagle-import") (part "C-EUC0805"))
    )
    (comp (ref "C212")
      (value "1u@35V")
      (footprint "eagle-import:C0603")
      (libsource (lib "eagle-import") (part "C-EUC0603"))
    )
    (comp (ref "C213")
      (value "1u@35V")
      (footprint "eagle-import:C0603")
      (libsource (lib "eagle-import") (part "C-EUC0603"))
    )
    (comp (ref "C214")
      (value "1u@25V")
      (footprint "eagle-import:C0603")
      (libsource (lib "eagle-import") (part "C-EUC0603"))
    )
    (comp (ref "C215")
      (value "1u@10V")
      (footprint "eagle-import:C0603")
      (libsource (lib "eagle-import") (part "C-EUC0603"))
    )
    (comp (ref "C216")
      (value "4.7u@25V")
      (footprint "eagle-import:C0603")
      (libsource (lib "eagle-import") (part "C-EUC0603"))
    )
    (comp (ref "INPUT")
      (value "1935161")
      (footprint "eagle-import:PHOENIX_1935161")
      (fields (field (name "MF") "Phoenix Contact"))
      (libsource (lib "eagle-import") (part "1935161"))
    )
    (comp (ref "JP1")
      (value "PINHD-1X2")
      (footprint "eagle-import:1X02")
      (libsource (lib "eagle-import") (part "PINHD-1X2"))
    )
    (comp (ref "JP2")
      (value "PINHD-1X2")
      (footprint "eagle-import:1X02")
      (libsource (lib "eagle-import") (part "PINHD-1X2"))
    )
    (comp (ref "JP5")
      (value "PINHD-1X2")
      (footprint "eagle-import:1X02")
      (libsource (lib "eagle-import") (part "PINHD-1X2"))
    )
    (comp (ref "JP6")
      (value "PINHD-1X2")
      (footprint "eagle-import:1X02")
      (libsource (lib "eagle-import") (part "PINHD-1X2"))
    )
    (comp (ref "JP7")
      (value "PINHD-1X2")
      (footprint "eagle-import:1X02")
      (libsource (lib "eagle-import") (part "PINHD-1X2"))
    )
    (comp (ref "JP8")
      (value "PINHD-1X2")
      (footprint "eagle-import:1X02")
      (libsource (lib "eagle-import") (part "PINHD-1X2"))
    )
    (comp (ref "JP9")
      (value "PINHD-1X2")
      (footprint "eagle-import:1X02")
      (libsource (lib "eagle-import") (part "PINHD-1X2"))
    )
    (comp (ref "JP10")
      (value "PINHD-1X2")
      (footprint "eagle-import:1X02")
      (libsource (lib "eagle-import") (part "PINHD-1X2"))
    )
    (comp (ref "JP13")
      (value "PINHD-1X2")
      (footprint "eagle-import:1X02")
      (libsource (lib "eagle-import") (part "PINHD-1X2"))
    )
    (comp (ref "JP14")
      (value "PINHD-1X2")
      (footprint "eagle-import:1X02")
      (libsource (lib "eagle-import") (part "PINHD-1X2"))
    )
    (comp (ref "JP15")
      (value "PINHD-1X2")
      (footprint "eagle-import:1X02")
      (libsource (lib "eagle-import") (part "PINHD-1X2"))
    )
    (comp (ref "JP16")
      (value "PINHD-1X2")
      (footprint "eagle-import:1X02")
      (libsource (lib "eagle-import") (part "PINHD-1X2"))
    )
    (comp (ref "JP17")
      (value "PINHD-1X2")
      (footprint "eagle-import:1X02")
      (libsource (lib "eagle-import") (part "PINHD-1X2"))
    )
    (comp (ref "JP18")
      (value "PINHD-1X2")
      (footprint "eagle-import:1X02")
      (libsource (lib "eagle-import") (part "PINHD-1X2"))
    )
    (comp (ref "JP21")
      (value "PINHD-1X2")
      (footprint "eagle-import:1X02")
      (libsource (lib "eagle-import") (part "PINHD-1X2"))
    )
    (comp (ref "JP22")
      (value "PINHD-1X2")
      (footprint "eagle-import:1X02")
      (libsource (lib "eagle-import") (part "PINHD-1X2"))
    )
    (comp (ref "JP23")
      (value "PINHD-1X2")
      (footprint "eagle-import:1X02")
      (libsource (lib "eagle-import") (part "PINHD-1X2"))
    )
    (comp (ref "JP24")
      (value "PINHD-1X2")
      (footprint "eagle-import:1X02")
      (libsource (lib "eagle-import") (part "PINHD-1X2"))
    )
    (comp (ref "JP25")
      (value "PINHD-1X2")
      (footprint "eagle-import:1X02")
      (libsource (lib "eagle-import") (part "PINHD-1X2"))
    )
    (comp (ref "JP26")
      (value "PINHD-1X2")
      (footprint "eagle-import:1X02")
      (libsource (lib "eagle-import") (part "PINHD-1X2"))
    )
    (comp (ref "JP29")
      (value "PINHD-1X2")
      (footprint "eagle-import:1X02")
      (libsource (lib "eagle-import") (part "PINHD-1X2"))
    )
    (comp (ref "JP30")
      (value "PINHD-1X2")
      (footprint "eagle-import:1X02")
      (libsource (lib "eagle-import") (part "PINHD-1X2"))
    )
    (comp (ref "JP31")
      (value "PINHD-1X2")
      (footprint "eagle-import:1X02")
      (libsource (lib "eagle-import") (part "PINHD-1X2"))
    )
    (comp (ref "JP32")
      (value "PINHD-1X2")
      (footprint "eagle-import:1X02")
      (libsource (lib "eagle-import") (part "PINHD-1X2"))
    )
    (comp (ref "JP35")
      (value "PINHD-1X2")
      (footprint "eagle-import:1X02")
      (libsource (lib "eagle-import") (part "PINHD-1X2"))
    )
    (comp (ref "JP36")
      (value "PINHD-1X2")
      (footprint "eagle-import:1X02")
      (libsource (lib "eagle-import") (part "PINHD-1X2"))
    )
    (comp (ref "JP39")
      (value "PINHD-1X2")
      (footprint "eagle-import:1X02")
      (libsource (lib "eagle-import") (part "PINHD-1X2"))
    )
    (comp (ref "JP40")
      (value "PINHD-1X2")
      (footprint "eagle-import:1X02")
      (libsource (lib "eagle-import") (part "PINHD-1X2"))
    )
    (comp (ref "JP43")
      (value "PINHD-1X2")
      (footprint "eagle-import:1X02")
      (libsource (lib "eagle-import") (part "PINHD-1X2"))
    )
    (comp (ref "JP44")
      (value "PINHD-1X2")
      (footprint "eagle-import:1X02")
      (libsource (lib "eagle-import") (part "PINHD-1X2"))
    )
    (comp (ref "JP47")
      (value "PINHD-1X2")
      (footprint "eagle-import:1X02")
      (libsource (lib "eagle-import") (part "PINHD-1X2"))
    )
    (comp (ref "JP48")
      (value "PINHD-1X2")
      (footprint "eagle-import:1X02")
      (libsource (lib "eagle-import") (part "PINHD-1X2"))
    )
    (comp (ref "L1")
      (value "BRL3225T4R7M 4.7u")
      (footprint "eagle-import:INDC3225X170N")
      (fields (field (name "MF") "Taiyo Yuden") (field (name "MP") "BRL3225T4R7M"))
      (libsource (lib "eagle-import") (part "BRL3225T4R7M"))
    )
    (comp (ref "L2")
      (value "3.3uH")
      (footprint "eagle-import:WE-PD_7345P")
      (libsource (lib "eagle-import") (part "WE-PD_7345P_7447773033"))
    )
    (comp (ref "L3")
      (value "FDSD0420-H-100M=P3")
      (footprint "eagle-import:IND_FDSD0420-H-100M=P3")
      (fields (field (name "MF") "Murata"))
      (libsource (lib "eagle-import") (part "FDSD0420-H-100M=P3"))
    )
    (comp (ref "L5")
      (value "BRL3225T4R7M 4.7u")
      (footprint "eagle-import:INDC3225X170N")
      (fields (field (name "MF") "Taiyo Yuden") (field (name "MP") "BRL3225T4R7M"))
      (libsource (lib "eagle-import") (part "BRL3225T4R7M"))
    )
    (comp (ref "L6")
      (value "FDSD0420-H-100M=P3")
      (footprint "eagle-import:IND_FDSD0420-H-100M=P3")
      (fields (field (name "MF") "Murata"))
      (libsource (lib "eagle-import") (part "FDSD0420-H-100M=P3"))
    )
    (comp (ref "L7")
      (value "BRL3225T4R7M 4.7u")
      (footprint "eagle-import:INDC3225X170N")
      (fields (field (name "MF") "Taiyo Yuden") (field (name "MP") "BRL3225T4R7M"))
      (libsource (lib "eagle-import") (part "BRL3225T4R7M"))
    )
    (comp (ref "L8")
      (value "FDSD0420-H-100M=P3")
      (footprint "eagle-import:IND_FDSD0420-H-100M=P3")
      (fields (field (name "MF") "Murata"))
      (libsource (lib "eagle-import") (part "FDSD0420-H-100M=P3"))
    )
    (comp (ref "L9")
      (value "BRL3225T4R7M 4.7u")
      (footprint "eagle-import:INDC3225X170N")
      (fields (field (name "MF") "Taiyo Yuden") (field (name "MP") "BRL3225T4R7M"))
      (libsource (lib "eagle-import") (part "BRL3225T4R7M"))
    )
    (comp (ref "L10")
      (value "FDSD0420-H-100M=P3")
      (footprint "eagle-import:IND_FDSD0420-H-100M=P3")
      (fields (field (name "MF") "Murata"))
      (libsource (lib "eagle-import") (part "FDSD0420-H-100M=P3"))
    )
    (comp (ref "L11")
      (value "3.3uH")
      (footprint "eagle-import:WE-PD_7345P")
      (libsource (lib "eagle-import") (part "WE-PD_7345P_7447773033"))
    )
    (comp (ref "L13")
      (value "BRL3225T4R7M 4.7u")
      (footprint "eagle-import:INDC3225X170N")
      (fields (field (name "MF") "Taiyo Yuden") (field (name "MP") "BRL3225T4R7M"))
      (libsource (lib "eagle-import") (part "BRL3225T4R7M"))
    )
    (comp (ref "L14")
      (value "FDSD0420-H-100M=P3")
      (footprint "eagle-import:IND_FDSD0420-H-100M=P3")
      (fields (field (name "MF") "Murata"))
      (libsource (lib "eagle-import") (part "FDSD0420-H-100M=P3"))
    )
    (comp (ref "L15")
      (value "BRL3225T4R7M 4.7u")
      (footprint "eagle-import:INDC3225X170N")
      (fields (field (name "MF") "Taiyo Yuden") (field (name "MP") "BRL3225T4R7M"))
      (libsource (lib "eagle-import") (part "BRL3225T4R7M"))
    )
    (comp (ref "L16")
      (value "FDSD0420-H-100M=P3")
      (footprint "eagle-import:IND_FDSD0420-H-100M=P3")
      (fields (field (name "MF") "Murata"))
      (libsource (lib "eagle-import") (part "FDSD0420-H-100M=P3"))
    )
    (comp (ref "L17")
      (value "BRL3225T4R7M 4.7u")
      (footprint "eagle-import:INDC3225X170N")
      (fields (field (name "MF") "Taiyo Yuden") (field (name "MP") "BRL3225T4R7M"))
      (libsource (lib "eagle-import") (part "BRL3225T4R7M"))
    )
    (comp (ref "L18")
      (value "FDSD0420-H-100M=P3")
      (footprint "eagle-import:IND_FDSD0420-H-100M=P3")
      (fields (field (name "MF") "Murata"))
      (libsource (lib "eagle-import") (part "FDSD0420-H-100M=P3"))
    )
    (comp (ref "L19")
      (value "3.3uH")
      (footprint "eagle-import:WE-PD_7345P")
      (libsource (lib "eagle-import") (part "WE-PD_7345P_7447773033"))
    )
    (comp (ref "L21")
      (value "BRL3225T4R7M 4.7u")
      (footprint "eagle-import:INDC3225X170N")
      (fields (field (name "MF") "Taiyo Yuden") (field (name "MP") "BRL3225T4R7M"))
      (libsource (lib "eagle-import") (part "BRL3225T4R7M"))
    )
    (comp (ref "L22")
      (value "FDSD0420-H-100M=P3")
      (footprint "eagle-import:IND_FDSD0420-H-100M=P3")
      (fields (field (name "MF") "Murata"))
      (libsource (lib "eagle-import") (part "FDSD0420-H-100M=P3"))
    )
    (comp (ref "L23")
      (value "BRL3225T4R7M 4.7u")
      (footprint "eagle-import:INDC3225X170N")
      (fields (field (name "MF") "Taiyo Yuden") (field (name "MP") "BRL3225T4R7M"))
      (libsource (lib "eagle-import") (part "BRL3225T4R7M"))
    )
    (comp (ref "L24")
      (value "FDSD0420-H-100M=P3")
      (footprint "eagle-import:IND_FDSD0420-H-100M=P3")
      (fields (field (name "MF") "Murata"))
      (libsource (lib "eagle-import") (part "FDSD0420-H-100M=P3"))
    )
    (comp (ref "L25")
      (value "BRL3225T4R7M 4.7u")
      (footprint "eagle-import:INDC3225X170N")
      (fields (field (name "MF") "Taiyo Yuden") (field (name "MP") "BRL3225T4R7M"))
      (libsource (lib "eagle-import") (part "BRL3225T4R7M"))
    )
    (comp (ref "L26")
      (value "FDSD0420-H-100M=P3")
      (footprint "eagle-import:IND_FDSD0420-H-100M=P3")
      (fields (field (name "MF") "Murata"))
      (libsource (lib "eagle-import") (part "FDSD0420-H-100M=P3"))
    )
    (comp (ref "L27")
      (value "3.3uH")
      (footprint "eagle-import:WE-PD_7345P")
      (libsource (lib "eagle-import") (part "WE-PD_7345P_7447773033"))
    )
    (comp (ref "L29")
      (value "BRL3225T4R7M 4.7u")
      (footprint "eagle-import:INDC3225X170N")
      (fields (field (name "MF") "Taiyo Yuden") (field (name "MP") "BRL3225T4R7M"))
      (libsource (lib "eagle-import") (part "BRL3225T4R7M"))
    )
    (comp (ref "L30")
      (value "FDSD0420-H-100M=P3")
      (footprint "eagle-import:IND_FDSD0420-H-100M=P3")
      (fields (field (name "MF") "Murata"))
      (libsource (lib "eagle-import") (part "FDSD0420-H-100M=P3"))
    )
    (comp (ref "L31")
      (value "BRL3225T4R7M 4.7u")
      (footprint "eagle-import:INDC3225X170N")
      (fields (field (name "MF") "Taiyo Yuden") (field (name "MP") "BRL3225T4R7M"))
      (libsource (lib "eagle-import") (part "BRL3225T4R7M"))
    )
    (comp (ref "L32")
      (value "FDSD0420-H-100M=P3")
      (footprint "eagle-import:IND_FDSD0420-H-100M=P3")
      (fields (field (name "MF") "Murata"))
      (libsource (lib "eagle-import") (part "FDSD0420-H-100M=P3"))
    )
    (comp (ref "L35")
      (value "BRL3225T4R7M 4.7u")
      (footprint "eagle-import:INDC3225X170N")
      (fields (field (name "MF") "Taiyo Yuden") (field (name "MP") "BRL3225T4R7M"))
      (libsource (lib "eagle-import") (part "BRL3225T4R7M"))
    )
    (comp (ref "L36")
      (value "FDSD0420-H-100M=P3")
      (footprint "eagle-import:IND_FDSD0420-H-100M=P3")
      (fields (field (name "MF") "Murata"))
      (libsource (lib "eagle-import") (part "FDSD0420-H-100M=P3"))
    )
    (comp (ref "L39")
      (value "BRL3225T4R7M 4.7u")
      (footprint "eagle-import:INDC3225X170N")
      (fields (field (name "MF") "Taiyo Yuden") (field (name "MP") "BRL3225T4R7M"))
      (libsource (lib "eagle-import") (part "BRL3225T4R7M"))
    )
    (comp (ref "L40")
      (value "FDSD0420-H-100M=P3")
      (footprint "eagle-import:IND_FDSD0420-H-100M=P3")
      (fields (field (name "MF") "Murata"))
      (libsource (lib "eagle-import") (part "FDSD0420-H-100M=P3"))
    )
    (comp (ref "L43")
      (value "BRL3225T4R7M 4.7u")
      (footprint "eagle-import:INDC3225X170N")
      (fields (field (name "MF") "Taiyo Yuden") (field (name "MP") "BRL3225T4R7M"))
      (libsource (lib "eagle-import") (part "BRL3225T4R7M"))
    )
    (comp (ref "L44")
      (value "FDSD0420-H-100M=P3")
      (footprint "eagle-import:IND_FDSD0420-H-100M=P3")
      (fields (field (name "MF") "Murata"))
      (libsource (lib "eagle-import") (part "FDSD0420-H-100M=P3"))
    )
    (comp (ref "L47")
      (value "BRL3225T4R7M 4.7u")
      (footprint "eagle-import:INDC3225X170N")
      (fields (field (name "MF") "Taiyo Yuden") (field (name "MP") "BRL3225T4R7M"))
      (libsource (lib "eagle-import") (part "BRL3225T4R7M"))
    )
    (comp (ref "L48")
      (value "FDSD0420-H-100M=P3")
      (footprint "eagle-import:IND_FDSD0420-H-100M=P3")
      (fields (field (name "MF") "Murata"))
      (libsource (lib "eagle-import") (part "FDSD0420-H-100M=P3"))
    )
    (comp (ref "LSP1")
      (value "LSP10")
      (footprint "eagle-import:LSP10")
      (libsource (lib "eagle-import") (part "LSP10"))
    )
    (comp (ref "LSP2")
      (value "LSP10")
      (footprint "eagle-import:LSP10")
      (libsource (lib "eagle-import") (part "LSP10"))
    )
    (comp (ref "LSP3")
      (value "LSP10")
      (footprint "eagle-import:LSP10")
      (libsource (lib "eagle-import") (part "LSP10"))
    )
    (comp (ref "LSP4")
      (value "LSP10")
      (footprint "eagle-import:LSP10")
      (libsource (lib "eagle-import") (part "LSP10"))
    )
    (comp (ref "R1")
      (value "10k")
      (footprint "eagle-import:R0603")
      (libsource (lib "eagle-import") (part "R-EU_R0603"))
    )
    (comp (ref "R2")
      (value "10k")
      (footprint "eagle-import:R0603")
      (libsource (lib "eagle-import") (part "R-EU_R0603"))
    )
    (comp (ref "R3")
      (value "33k")
      (footprint "eagle-import:R0603")
      (libsource (lib "eagle-import") (part "R-EU_R0603"))
    )
    (comp (ref "R4")
      (value "10k")
      (footprint "eagle-import:R0603")
      (libsource (lib "eagle-import") (part "R-EU_R0603"))
    )
    (comp (ref "R5")
      (value "10")
      (footprint "eagle-import:R0603")
      (libsource (lib "eagle-import") (part "R-EU_R0603"))
    )
    (comp (ref "R6")
      (value "10")
      (footprint "eagle-import:R0603")
      (libsource (lib "eagle-import") (part "R-EU_R0603"))
    )
    (comp (ref "R7")
      (value "18k")
      (footprint "eagle-import:R0603")
      (libsource (lib "eagle-import") (part "R-EU_R0603"))
    )
    (comp (ref "R8")
      (value "1k")
      (footprint "eagle-import:R0603")
      (libsource (lib "eagle-import") (part "R-EU_R0603"))
    )
    (comp (ref "R11")
      (value "33k")
      (footprint "eagle-import:R0603")
      (libsource (lib "eagle-import") (part "R-EU_R0603"))
    )
    (comp (ref "R12")
      (value "10k")
      (footprint "eagle-import:R0603")
      (libsource (lib "eagle-import") (part "R-EU_R0603"))
    )
    (comp (ref "R13")
      (value "10k")
      (footprint "eagle-import:R0603")
      (libsource (lib "eagle-import") (part "R-EU_R0603"))
    )
    (comp (ref "R14")
      (value "10k")
      (footprint "eagle-import:R0603")
      (libsource (lib "eagle-import") (part "R-EU_R0603"))
    )
    (comp (ref "R15")
      (value "10")
      (footprint "eagle-import:R0603")
      (libsource (lib "eagle-import") (part "R-EU_R0603"))
    )
    (comp (ref "R16")
      (value "10")
      (footprint "eagle-import:R0603")
      (libsource (lib "eagle-import") (part "R-EU_R0603"))
    )
    (comp (ref "R17")
      (value "18k")
      (footprint "eagle-import:R0603")
      (libsource (lib "eagle-import") (part "R-EU_R0603"))
    )
    (comp (ref "R18")
      (value "1k")
      (footprint "eagle-import:R0603")
      (libsource (lib "eagle-import") (part "R-EU_R0603"))
    )
    (comp (ref "R19")
      (value "10k")
      (footprint "eagle-import:R0603")
      (libsource (lib "eagle-import") (part "R-EU_R0603"))
    )
    (comp (ref "R20")
      (value "10k")
      (footprint "eagle-import:R0603")
      (libsource (lib "eagle-import") (part "R-EU_R0603"))
    )
    (comp (ref "R21")
      (value "10")
      (footprint "eagle-import:R0603")
      (libsource (lib "eagle-import") (part "R-EU_R0603"))
    )
    (comp (ref "R22")
      (value "10")
      (footprint "eagle-import:R0603")
      (libsource (lib "eagle-import") (part "R-EU_R0603"))
    )
    (comp (ref "R23")
      (value "18k")
      (footprint "eagle-import:R0603")
      (libsource (lib "eagle-import") (part "R-EU_R0603"))
    )
    (comp (ref "R24")
      (value "1k")
      (footprint "eagle-import:R0603")
      (libsource (lib "eagle-import") (part "R-EU_R0603"))
    )
    (comp (ref "R25")
      (value "10k")
      (footprint "eagle-import:R0603")
      (libsource (lib "eagle-import") (part "R-EU_R0603"))
    )
    (comp (ref "R26")
      (value "10k")
      (footprint "eagle-import:R0603")
      (libsource (lib "eagle-import") (part "R-EU_R0603"))
    )
    (comp (ref "R27")
      (value "10")
      (footprint "eagle-import:R0603")
      (libsource (lib "eagle-import") (part "R-EU_R0603"))
    )
    (comp (ref "R28")
      (value "10")
      (footprint "eagle-import:R0603")
      (libsource (lib "eagle-import") (part "R-EU_R0603"))
    )
    (comp (ref "R29")
      (value "18k")
      (footprint "eagle-import:R0603")
      (libsource (lib "eagle-import") (part "R-EU_R0603"))
    )
    (comp (ref "R30")
      (value "1k")
      (footprint "eagle-import:R0603")
      (libsource (lib "eagle-import") (part "R-EU_R0603"))
    )
    (comp (ref "R33")
      (value "33k")
      (footprint "eagle-import:R0603")
      (libsource (lib "eagle-import") (part "R-EU_R0603"))
    )
    (comp (ref "R34")
      (value "10k")
      (footprint "eagle-import:R0603")
      (libsource (lib "eagle-import") (part "R-EU_R0603"))
    )
    (comp (ref "R37")
      (value "10k")
      (footprint "eagle-import:R0603")
      (libsource (lib "eagle-import") (part "R-EU_R0603"))
    )
    (comp (ref "R38")
      (value "10k")
      (footprint "eagle-import:R0603")
      (libsource (lib "eagle-import") (part "R-EU_R0603"))
    )
    (comp (ref "R39")
      (value "10")
      (footprint "eagle-import:R0603")
      (libsource (lib "eagle-import") (part "R-EU_R0603"))
    )
    (comp (ref "R40")
      (value "10")
      (footprint "eagle-import:R0603")
      (libsource (lib "eagle-import") (part "R-EU_R0603"))
    )
    (comp (ref "R41")
      (value "18k")
      (footprint "eagle-import:R0603")
      (libsource (lib "eagle-import") (part "R-EU_R0603"))
    )
    (comp (ref "R42")
      (value "1k")
      (footprint "eagle-import:R0603")
      (libsource (lib "eagle-import") (part "R-EU_R0603"))
    )
    (comp (ref "R43")
      (value "10k")
      (footprint "eagle-import:R0603")
      (libsource (lib "eagle-import") (part "R-EU_R0603"))
    )
    (comp (ref "R44")
      (value "10k")
      (footprint "eagle-import:R0603")
      (libsource (lib "eagle-import") (part "R-EU_R0603"))
    )
    (comp (ref "R45")
      (value "10")
      (footprint "eagle-import:R0603")
      (libsource (lib "eagle-import") (part "R-EU_R0603"))
    )
    (comp (ref "R46")
      (value "10")
      (footprint "eagle-import:R0603")
      (libsource (lib "eagle-import") (part "R-EU_R0603"))
    )
    (comp (ref "R47")
      (value "18k")
      (footprint "eagle-import:R0603")
      (libsource (lib "eagle-import") (part "R-EU_R0603"))
    )
    (comp (ref "R48")
      (value "1k")
      (footprint "eagle-import:R0603")
      (libsource (lib "eagle-import") (part "R-EU_R0603"))
    )
    (comp (ref "R49")
      (value "10k")
      (footprint "eagle-import:R0603")
      (libsource (lib "eagle-import") (part "R-EU_R0603"))
    )
    (comp (ref "R50")
      (value "10k")
      (footprint "eagle-import:R0603")
      (libsource (lib "eagle-import") (part "R-EU_R0603"))
    )
    (comp (ref "R51")
      (value "10")
      (footprint "eagle-import:R0603")
      (libsource (lib "eagle-import") (part "R-EU_R0603"))
    )
    (comp (ref "R52")
      (value "10")
      (footprint "eagle-import:R0603")
      (libsource (lib "eagle-import") (part "R-EU_R0603"))
    )
    (comp (ref "R53")
      (value "18k")
      (footprint "eagle-import:R0603")
      (libsource (lib "eagle-import") (part "R-EU_R0603"))
    )
    (comp (ref "R54")
      (value "1k")
      (footprint "eagle-import:R0603")
      (libsource (lib "eagle-import") (part "R-EU_R0603"))
    )
    (comp (ref "R55")
      (value "33k")
      (footprint "eagle-import:R0603")
      (libsource (lib "eagle-import") (part "R-EU_R0603"))
    )
    (comp (ref "R56")
      (value "10k")
      (footprint "eagle-import:R0603")
      (libsource (lib "eagle-import") (part "R-EU_R0603"))
    )
    (comp (ref "R61")
      (value "10k")
      (footprint "eagle-import:R0603")
      (libsource (lib "eagle-import") (part "R-EU_R0603"))
    )
    (comp (ref "R62")
      (value "10k")
      (footprint "eagle-import:R0603")
      (libsource (lib "eagle-import") (part "R-EU_R0603"))
    )
    (comp (ref "R63")
      (value "10")
      (footprint "eagle-import:R0603")
      (libsource (lib "eagle-import") (part "R-EU_R0603"))
    )
    (comp (ref "R64")
      (value "10")
      (footprint "eagle-import:R0603")
      (libsource (lib "eagle-import") (part "R-EU_R0603"))
    )
    (comp (ref "R65")
      (value "18k")
      (footprint "eagle-import:R0603")
      (libsource (lib "eagle-import") (part "R-EU_R0603"))
    )
    (comp (ref "R66")
      (value "1k")
      (footprint "eagle-import:R0603")
      (libsource (lib "eagle-import") (part "R-EU_R0603"))
    )
    (comp (ref "R67")
      (value "10k")
      (footprint "eagle-import:R0603")
      (libsource (lib "eagle-import") (part "R-EU_R0603"))
    )
    (comp (ref "R68")
      (value "10k")
      (footprint "eagle-import:R0603")
      (libsource (lib "eagle-import") (part "R-EU_R0603"))
    )
    (comp (ref "R69")
      (value "10")
      (footprint "eagle-import:R0603")
      (libsource (lib "eagle-import") (part "R-EU_R0603"))
    )
    (comp (ref "R70")
      (value "10")
      (footprint "eagle-import:R0603")
      (libsource (lib "eagle-import") (part "R-EU_R0603"))
    )
    (comp (ref "R71")
      (value "18k")
      (footprint "eagle-import:R0603")
      (libsource (lib "eagle-import") (part "R-EU_R0603"))
    )
    (comp (ref "R72")
      (value "1k")
      (footprint "eagle-import:R0603")
      (libsource (lib "eagle-import") (part "R-EU_R0603"))
    )
    (comp (ref "R73")
      (value "10k")
      (footprint "eagle-import:R0603")
      (libsource (lib "eagle-import") (part "R-EU_R0603"))
    )
    (comp (ref "R74")
      (value "10k")
      (footprint "eagle-import:R0603")
      (libsource (lib "eagle-import") (part "R-EU_R0603"))
    )
    (comp (ref "R75")
      (value "10")
      (footprint "eagle-import:R0603")
      (libsource (lib "eagle-import") (part "R-EU_R0603"))
    )
    (comp (ref "R76")
      (value "10")
      (footprint "eagle-import:R0603")
      (libsource (lib "eagle-import") (part "R-EU_R0603"))
    )
    (comp (ref "R77")
      (value "18k")
      (footprint "eagle-import:R0603")
      (libsource (lib "eagle-import") (part "R-EU_R0603"))
    )
    (comp (ref "R78")
      (value "1k")
      (footprint "eagle-import:R0603")
      (libsource (lib "eagle-import") (part "R-EU_R0603"))
    )
    (comp (ref "R85")
      (value "10k")
      (footprint "eagle-import:R0603")
      (libsource (lib "eagle-import") (part "R-EU_R0603"))
    )
    (comp (ref "R86")
      (value "10k")
      (footprint "eagle-import:R0603")
      (libsource (lib "eagle-import") (part "R-EU_R0603"))
    )
    (comp (ref "R87")
      (value "10")
      (footprint "eagle-import:R0603")
      (libsource (lib "eagle-import") (part "R-EU_R0603"))
    )
    (comp (ref "R88")
      (value "10")
      (footprint "eagle-import:R0603")
      (libsource (lib "eagle-import") (part "R-EU_R0603"))
    )
    (comp (ref "R89")
      (value "18k")
      (footprint "eagle-import:R0603")
      (libsource (lib "eagle-import") (part "R-EU_R0603"))
    )
    (comp (ref "R90")
      (value "1k")
      (footprint "eagle-import:R0603")
      (libsource (lib "eagle-import") (part "R-EU_R0603"))
    )
    (comp (ref "R91")
      (value "10k")
      (footprint "eagle-import:R0603")
      (libsource (lib "eagle-import") (part "R-EU_R0603"))
    )
    (comp (ref "R92")
      (value "10k")
      (footprint "eagle-import:R0603")
      (libsource (lib "eagle-import") (part "R-EU_R0603"))
    )
    (comp (ref "R93")
      (value "10")
      (footprint "eagle-import:R0603")
      (libsource (lib "eagle-import") (part "R-EU_R0603"))
    )
    (comp (ref "R94")
      (value "10")
      (footprint "eagle-import:R0603")
      (libsource (lib "eagle-import") (part "R-EU_R0603"))
    )
    (comp (ref "R95")
      (value "18k")
      (footprint "eagle-import:R0603")
      (libsource (lib "eagle-import") (part "R-EU_R0603"))
    )
    (comp (ref "R96")
      (value "1k")
      (footprint "eagle-import:R0603")
      (libsource (lib "eagle-import") (part "R-EU_R0603"))
    )
    (comp (ref "R103")
      (value "10k")
      (footprint "eagle-import:R0603")
      (libsource (lib "eagle-import") (part "R-EU_R0603"))
    )
    (comp (ref "R104")
      (value "10k")
      (footprint "eagle-import:R0603")
      (libsource (lib "eagle-import") (part "R-EU_R0603"))
    )
    (comp (ref "R105")
      (value "10")
      (footprint "eagle-import:R0603")
      (libsource (lib "eagle-import") (part "R-EU_R0603"))
    )
    (comp (ref "R106")
      (value "10")
      (footprint "eagle-import:R0603")
      (libsource (lib "eagle-import") (part "R-EU_R0603"))
    )
    (comp (ref "R107")
      (value "18k")
      (footprint "eagle-import:R0603")
      (libsource (lib "eagle-import") (part "R-EU_R0603"))
    )
    (comp (ref "R108")
      (value "1k")
      (footprint "eagle-import:R0603")
      (libsource (lib "eagle-import") (part "R-EU_R0603"))
    )
    (comp (ref "R115")
      (value "10k")
      (footprint "eagle-import:R0603")
      (libsource (lib "eagle-import") (part "R-EU_R0603"))
    )
    (comp (ref "R116")
      (value "10k")
      (footprint "eagle-import:R0603")
      (libsource (lib "eagle-import") (part "R-EU_R0603"))
    )
    (comp (ref "R117")
      (value "10")
      (footprint "eagle-import:R0603")
      (libsource (lib "eagle-import") (part "R-EU_R0603"))
    )
    (comp (ref "R118")
      (value "10")
      (footprint "eagle-import:R0603")
      (libsource (lib "eagle-import") (part "R-EU_R0603"))
    )
    (comp (ref "R119")
      (value "18k")
      (footprint "eagle-import:R0603")
      (libsource (lib "eagle-import") (part "R-EU_R0603"))
    )
    (comp (ref "R120")
      (value "1k")
      (footprint "eagle-import:R0603")
      (libsource (lib "eagle-import") (part "R-EU_R0603"))
    )
    (comp (ref "R127")
      (value "10k")
      (footprint "eagle-import:R0603")
      (libsource (lib "eagle-import") (part "R-EU_R0603"))
    )
    (comp (ref "R128")
      (value "10k")
      (footprint "eagle-import:R0603")
      (libsource (lib "eagle-import") (part "R-EU_R0603"))
    )
    (comp (ref "R129")
      (value "10")
      (footprint "eagle-import:R0603")
      (libsource (lib "eagle-import") (part "R-EU_R0603"))
    )
    (comp (ref "R130")
      (value "10")
      (footprint "eagle-import:R0603")
      (libsource (lib "eagle-import") (part "R-EU_R0603"))
    )
    (comp (ref "R131")
      (value "18k")
      (footprint "eagle-import:R0603")
      (libsource (lib "eagle-import") (part "R-EU_R0603"))
    )
    (comp (ref "R132")
      (value "1k")
      (footprint "eagle-import:R0603")
      (libsource (lib "eagle-import") (part "R-EU_R0603"))
    )
    (comp (ref "R139")
      (value "10k")
      (footprint "eagle-import:R0603")
      (libsource (lib "eagle-import") (part "R-EU_R0603"))
    )
    (comp (ref "R140")
      (value "10k")
      (footprint "eagle-import:R0603")
      (libsource (lib "eagle-import") (part "R-EU_R0603"))
    )
    (comp (ref "R141")
      (value "10")
      (footprint "eagle-import:R0603")
      (libsource (lib "eagle-import") (part "R-EU_R0603"))
    )
    (comp (ref "R142")
      (value "10")
      (footprint "eagle-import:R0603")
      (libsource (lib "eagle-import") (part "R-EU_R0603"))
    )
    (comp (ref "R143")
      (value "18k")
      (footprint "eagle-import:R0603")
      (libsource (lib "eagle-import") (part "R-EU_R0603"))
    )
    (comp (ref "R144")
      (value "1k")
      (footprint "eagle-import:R0603")
      (libsource (lib "eagle-import") (part "R-EU_R0603"))
    )
    (comp (ref "SJ1") (value "SJ") (footprint "eagle-import:SJ") (libsource (lib "eagle-import") (part "SJ")))
    (comp (ref "SJ2") (value "SJ") (footprint "eagle-import:SJ") (libsource (lib "eagle-import") (part "SJ")))
    (comp (ref "SJ3")
      (value "SJ2W")
      (footprint "eagle-import:SJ_2")
      (libsource (lib "eagle-import") (part "SJ2W"))
    )
    (comp (ref "SJ5") (value "SJ") (footprint "eagle-import:SJ") (libsource (lib "eagle-import") (part "SJ")))
    (comp (ref "SJ6")
      (value "SJ2W")
      (footprint "eagle-import:SJ_2")
      (libsource (lib "eagle-import") (part "SJ2W"))
    )
    (comp (ref "SJ7") (value "SJ") (footprint "eagle-import:SJ") (libsource (lib "eagle-import") (part "SJ")))
    (comp (ref "SJ8")
      (value "SJ2W")
      (footprint "eagle-import:SJ_2")
      (libsource (lib "eagle-import") (part "SJ2W"))
    )
    (comp (ref "SJ9") (value "SJ") (footprint "eagle-import:SJ") (libsource (lib "eagle-import") (part "SJ")))
    (comp (ref "SJ10")
      (value "SJ2W")
      (footprint "eagle-import:SJ_2")
      (libsource (lib "eagle-import") (part "SJ2W"))
    )
    (comp (ref "SJ11")
      (value "SJ")
      (footprint "eagle-import:SJ")
      (libsource (lib "eagle-import") (part "SJ"))
    )
    (comp (ref "SJ13")
      (value "SJ")
      (footprint "eagle-import:SJ")
      (libsource (lib "eagle-import") (part "SJ"))
    )
    (comp (ref "SJ14")
      (value "SJ2W")
      (footprint "eagle-import:SJ_2")
      (libsource (lib "eagle-import") (part "SJ2W"))
    )
    (comp (ref "SJ15")
      (value "SJ")
      (footprint "eagle-import:SJ")
      (libsource (lib "eagle-import") (part "SJ"))
    )
    (comp (ref "SJ16")
      (value "SJ2W")
      (footprint "eagle-import:SJ_2")
      (libsource (lib "eagle-import") (part "SJ2W"))
    )
    (comp (ref "SJ17")
      (value "SJ")
      (footprint "eagle-import:SJ")
      (libsource (lib "eagle-import") (part "SJ"))
    )
    (comp (ref "SJ18")
      (value "SJ2W")
      (footprint "eagle-import:SJ_2")
      (libsource (lib "eagle-import") (part "SJ2W"))
    )
    (comp (ref "SJ19")
      (value "SJ")
      (footprint "eagle-import:SJ")
      (libsource (lib "eagle-import") (part "SJ"))
    )
    (comp (ref "SJ21")
      (value "SJ")
      (footprint "eagle-import:SJ")
      (libsource (lib "eagle-import") (part "SJ"))
    )
    (comp (ref "SJ22")
      (value "SJ2W")
      (footprint "eagle-import:SJ_2")
      (libsource (lib "eagle-import") (part "SJ2W"))
    )
    (comp (ref "SJ23")
      (value "SJ")
      (footprint "eagle-import:SJ")
      (libsource (lib "eagle-import") (part "SJ"))
    )
    (comp (ref "SJ24")
      (value "SJ2W")
      (footprint "eagle-import:SJ_2")
      (libsource (lib "eagle-import") (part "SJ2W"))
    )
    (comp (ref "SJ25")
      (value "SJ")
      (footprint "eagle-import:SJ")
      (libsource (lib "eagle-import") (part "SJ"))
    )
    (comp (ref "SJ26")
      (value "SJ2W")
      (footprint "eagle-import:SJ_2")
      (libsource (lib "eagle-import") (part "SJ2W"))
    )
    (comp (ref "SJ27")
      (value "SJ")
      (footprint "eagle-import:SJ")
      (libsource (lib "eagle-import") (part "SJ"))
    )
    (comp (ref "SJ29")
      (value "SJ")
      (footprint "eagle-import:SJ")
      (libsource (lib "eagle-import") (part "SJ"))
    )
    (comp (ref "SJ30")
      (value "SJ2W")
      (footprint "eagle-import:SJ_2")
      (libsource (lib "eagle-import") (part "SJ2W"))
    )
    (comp (ref "SJ31")
      (value "SJ")
      (footprint "eagle-import:SJ")
      (libsource (lib "eagle-import") (part "SJ"))
    )
    (comp (ref "SJ32")
      (value "SJ2W")
      (footprint "eagle-import:SJ_2")
      (libsource (lib "eagle-import") (part "SJ2W"))
    )
    (comp (ref "SJ35")
      (value "SJ")
      (footprint "eagle-import:SJ")
      (libsource (lib "eagle-import") (part "SJ"))
    )
    (comp (ref "SJ36")
      (value "SJ2W")
      (footprint "eagle-import:SJ_2")
      (libsource (lib "eagle-import") (part "SJ2W"))
    )
    (comp (ref "SJ39")
      (value "SJ")
      (footprint "eagle-import:SJ")
      (libsource (lib "eagle-import") (part "SJ"))
    )
    (comp (ref "SJ40")
      (value "SJ2W")
      (footprint "eagle-import:SJ_2")
      (libsource (lib "eagle-import") (part "SJ2W"))
    )
    (comp (ref "SJ43")
      (value "SJ")
      (footprint "eagle-import:SJ")
      (libsource (lib "eagle-import") (part "SJ"))
    )
    (comp (ref "SJ44")
      (value "SJ2W")
      (footprint "eagle-import:SJ_2")
      (libsource (lib "eagle-import") (part "SJ2W"))
    )
    (comp (ref "SJ47")
      (value "SJ")
      (footprint "eagle-import:SJ")
      (libsource (lib "eagle-import") (part "SJ"))
    )
    (comp (ref "SJ48")
      (value "SJ2W")
      (footprint "eagle-import:SJ_2")
      (libsource (lib "eagle-import") (part "SJ2W"))
    )
    (comp (ref "U$1")
      (value "TPS562209")
      (footprint "eagle-import:SOT95P280X110-6N")
      (libsource (lib "eagle-import") (part "TPS562209"))
    )
    (comp (ref "U$2")
      (value "NSR0520V2T1G")
      (footprint "eagle-import:SOD523")
      (libsource (lib "eagle-import") (part "NSR0520V2T1G"))
    )
    (comp (ref "U$3")
      (value "NSR0520V2T1G")
      (footprint "eagle-import:SOD523")
      (libsource (lib "eagle-import") (part "NSR0520V2T1G"))
    )
    (comp (ref "U$4")
      (value "NSR0520V2T1G")
      (footprint "eagle-import:SOD523")
      (libsource (lib "eagle-import") (part "NSR0520V2T1G"))
    )
    (comp (ref "U$5")
      (value "NSR0520V2T1G")
      (footprint "eagle-import:SOD523")
      (libsource (lib "eagle-import") (part "NSR0520V2T1G"))
    )
    (comp (ref "U$7")
      (value "NSR0520V2T1G")
      (footprint "eagle-import:SOD523")
      (libsource (lib "eagle-import") (part "NSR0520V2T1G"))
    )
    (comp (ref "U$8")
      (value "NSR0520V2T1G")
      (footprint "eagle-import:SOD523")
      (libsource (lib "eagle-import") (part "NSR0520V2T1G"))
    )
    (comp (ref "U$9")
      (value "NSR0520V2T1G")
      (footprint "eagle-import:SOD523")
      (libsource (lib "eagle-import") (part "NSR0520V2T1G"))
    )
    (comp (ref "U$10")
      (value "TPS562209")
      (footprint "eagle-import:SOT95P280X110-6N")
      (libsource (lib "eagle-import") (part "TPS562209"))
    )
    (comp (ref "U$11")
      (value "NSR0520V2T1G")
      (footprint "eagle-import:SOD523")
      (libsource (lib "eagle-import") (part "NSR0520V2T1G"))
    )
    (comp (ref "U$12")
      (value "NSR0520V2T1G")
      (footprint "eagle-import:SOD523")
      (libsource (lib "eagle-import") (part "NSR0520V2T1G"))
    )
    (comp (ref "U$13")
      (value "NSR0520V2T1G")
      (footprint "eagle-import:SOD523")
      (libsource (lib "eagle-import") (part "NSR0520V2T1G"))
    )
    (comp (ref "U$15")
      (value "NSR0520V2T1G")
      (footprint "eagle-import:SOD523")
      (libsource (lib "eagle-import") (part "NSR0520V2T1G"))
    )
    (comp (ref "U$16")
      (value "NSR0520V2T1G")
      (footprint "eagle-import:SOD523")
      (libsource (lib "eagle-import") (part "NSR0520V2T1G"))
    )
    (comp (ref "U$17")
      (value "TPS562209")
      (footprint "eagle-import:SOT95P280X110-6N")
      (libsource (lib "eagle-import") (part "TPS562209"))
    )
    (comp (ref "U$18")
      (value "NSR0520V2T1G")
      (footprint "eagle-import:SOD523")
      (libsource (lib "eagle-import") (part "NSR0520V2T1G"))
    )
    (comp (ref "U$20")
      (value "NSR0520V2T1G")
      (footprint "eagle-import:SOD523")
      (libsource (lib "eagle-import") (part "NSR0520V2T1G"))
    )
    (comp (ref "U$21")
      (value "TPS562209")
      (footprint "eagle-import:SOT95P280X110-6N")
      (libsource (lib "eagle-import") (part "TPS562209"))
    )
    (comp (ref "U$22")
      (value "NSR0520V2T1G")
      (footprint "eagle-import:SOD523")
      (libsource (lib "eagle-import") (part "NSR0520V2T1G"))
    )
    (comp (ref "U$24")
      (value "NSR0520V2T1G")
      (footprint "eagle-import:SOD523")
      (libsource (lib "eagle-import") (part "NSR0520V2T1G"))
    )
    (comp (ref "U1")
      (value "TLV61046ADBVR")
      (footprint "eagle-import:SOT95P280X145-6N")
      (fields (field (name "MF") "Texas Instruments"))
      (libsource (lib "eagle-import") (part "TLV61046ADBVR"))
    )
    (comp (ref "U2")
      (value "LM48580")
      (footprint "eagle-import:BGA12N40P3X4_119X159X62N")
      (libsource (lib "eagle-import") (part "LM48580"))
    )
    (comp (ref "U5")
      (value "LM48580")
      (footprint "eagle-import:BGA12N40P3X4_119X159X62N")
      (libsource (lib "eagle-import") (part "LM48580"))
    )
    (comp (ref "U6")
      (value "TLV61046ADBVR")
      (footprint "eagle-import:SOT95P280X145-6N")
      (fields (field (name "MF") "Texas Instruments"))
      (libsource (lib "eagle-import") (part "TLV61046ADBVR"))
    )
    (comp (ref "U7")
      (value "LM48580")
      (footprint "eagle-import:BGA12N40P3X4_119X159X62N")
      (libsource (lib "eagle-import") (part "LM48580"))
    )
    (comp (ref "U8")
      (value "TLV61046ADBVR")
      (footprint "eagle-import:SOT95P280X145-6N")
      (fields (field (name "MF") "Texas Instruments"))
      (libsource (lib "eagle-import") (part "TLV61046ADBVR"))
    )
    (comp (ref "U9")
      (value "LM48580")
      (footprint "eagle-import:BGA12N40P3X4_119X159X62N")
      (libsource (lib "eagle-import") (part "LM48580"))
    )
    (comp (ref "U10")
      (value "TLV61046ADBVR")
      (footprint "eagle-import:SOT95P280X145-6N")
      (fields (field (name "MF") "Texas Instruments"))
      (libsource (lib "eagle-import") (part "TLV61046ADBVR"))
    )
    (comp (ref "U13")
      (value "LM48580")
      (footprint "eagle-import:BGA12N40P3X4_119X159X62N")
      (libsource (lib "eagle-import") (part "LM48580"))
    )
    (comp (ref "U14")
      (value "TLV61046ADBVR")
      (footprint "eagle-import:SOT95P280X145-6N")
      (fields (field (name "MF") "Texas Instruments"))
      (libsource (lib "eagle-import") (part "TLV61046ADBVR"))
    )
    (comp (ref "U15")
      (value "LM48580")
      (footprint "eagle-import:BGA12N40P3X4_119X159X62N")
      (libsource (lib "eagle-import") (part "LM48580"))
    )
    (comp (ref "U16")
      (value "TLV61046ADBVR")
      (footprint "eagle-import:SOT95P280X145-6N")
      (fields (field (name "MF") "Texas Instruments"))
      (libsource (lib "eagle-import") (part "TLV61046ADBVR"))
    )
    (comp (ref "U17")
      (value "LM48580")
      (footprint "eagle-import:BGA12N40P3X4_119X159X62N")
      (libsource (lib "eagle-import") (part "LM48580"))
    )
    (comp (ref "U18")
      (value "TLV61046ADBVR")
      (footprint "eagle-import:SOT95P280X145-6N")
      (fields (field (name "MF") "Texas Instruments"))
      (libsource (lib "eagle-import") (part "TLV61046ADBVR"))
    )
    (comp (ref "U21")
      (value "LM48580")
      (footprint "eagle-import:BGA12N40P3X4_119X159X62N")
      (libsource (lib "eagle-import") (part "LM48580"))
    )
    (comp (ref "U22")
      (value "TLV61046ADBVR")
      (footprint "eagle-import:SOT95P280X145-6N")
      (fields (field (name "MF") "Texas Instruments"))
      (libsource (lib "eagle-import") (part "TLV61046ADBVR"))
    )
    (comp (ref "U23")
      (value "LM48580")
      (footprint "eagle-import:BGA12N40P3X4_119X159X62N")
      (libsource (lib "eagle-import") (part "LM48580"))
    )
    (comp (ref "U24")
      (value "TLV61046ADBVR")
      (footprint "eagle-import:SOT95P280X145-6N")
      (fields (field (name "MF") "Texas Instruments"))
      (libsource (lib "eagle-import") (part "TLV61046ADBVR"))
    )
    (comp (ref "U25")
      (value "LM48580")
      (footprint "eagle-import:BGA12N40P3X4_119X159X62N")
      (libsource (lib "eagle-import") (part "LM48580"))
    )
    (comp (ref "U26")
      (value "TLV61046ADBVR")
      (footprint "eagle-import:SOT95P280X145-6N")
      (fields (field (name "MF") "Texas Instruments"))
      (libsource (lib "eagle-import") (part "TLV61046ADBVR"))
    )
    (comp (ref "U29")
      (value "LM48580")
      (footprint "eagle-import:BGA12N40P3X4_119X159X62N")
      (libsource (lib "eagle-import") (part "LM48580"))
    )
    (comp (ref "U30")
      (value "TLV61046ADBVR")
      (footprint "eagle-import:SOT95P280X145-6N")
      (fields (field (name "MF") "Texas Instruments"))
      (libsource (lib "eagle-import") (part "TLV61046ADBVR"))
    )
    (comp (ref "U31")
      (value "LM48580")
      (footprint "eagle-import:BGA12N40P3X4_119X159X62N")
      (libsource (lib "eagle-import") (part "LM48580"))
    )
    (comp (ref "U32")
      (value "TLV61046ADBVR")
      (footprint "eagle-import:SOT95P280X145-6N")
      (fields (field (name "MF") "Texas Instruments"))
      (libsource (lib "eagle-import") (part "TLV61046ADBVR"))
    )
    (comp (ref "U35")
      (value "LM48580")
      (footprint "eagle-import:BGA12N40P3X4_119X159X62N")
      (libsource (lib "eagle-import") (part "LM48580"))
    )
    (comp (ref "U36")
      (value "TLV61046ADBVR")
      (footprint "eagle-import:SOT95P280X145-6N")
      (fields (field (name "MF") "Texas Instruments"))
      (libsource (lib "eagle-import") (part "TLV61046ADBVR"))
    )
    (comp (ref "U39")
      (value "LM48580")
      (footprint "eagle-import:BGA12N40P3X4_119X159X62N")
      (libsource (lib "eagle-import") (part "LM48580"))
    )
    (comp (ref "U40")
      (value "TLV61046ADBVR")
      (footprint "eagle-import:SOT95P280X145-6N")
      (fields (field (name "MF") "Texas Instruments"))
      (libsource (lib "eagle-import") (part "TLV61046ADBVR"))
    )
    (comp (ref "U43")
      (value "LM48580")
      (footprint "eagle-import:BGA12N40P3X4_119X159X62N")
      (libsource (lib "eagle-import") (part "LM48580"))
    )
    (comp (ref "U44")
      (value "TLV61046ADBVR")
      (footprint "eagle-import:SOT95P280X145-6N")
      (fields (field (name "MF") "Texas Instruments"))
      (libsource (lib "eagle-import") (part "TLV61046ADBVR"))
    )
    (comp (ref "U47")
      (value "LM48580")
      (footprint "eagle-import:BGA12N40P3X4_119X159X62N")
      (libsource (lib "eagle-import") (part "LM48580"))
    )
    (comp (ref "U48")
      (value "TLV61046ADBVR")
      (footprint "eagle-import:SOT95P280X145-6N")
      (fields (field (name "MF") "Texas Instruments"))
      (libsource (lib "eagle-import") (part "TLV61046ADBVR"))
    )
  )
  (nets
    (net (code "1") (name "/+3V3_A") (class "Default")
      (node (ref "C16") (pin "1") (pinfunction "1_1") (pintype "passive"))
      (node (ref "C17") (pin "1") (pinfunction "1_1") (pintype "passive"))
      (node (ref "C21") (pin "1") (pinfunction "1_1") (pintype "passive"))
      (node (ref "C22") (pin "1") (pinfunction "1_1") (pintype "passive"))
      (node (ref "C26") (pin "1") (pinfunction "1_1") (pintype "passive"))
      (node (ref "C3") (pin "1") (pinfunction "1_1") (pintype "passive"))
      (node (ref "C39") (pin "1") (pinfunction "1_1") (pintype "passive"))
      (node (ref "C4") (pin "1") (pinfunction "1_1") (pintype "passive"))
      (node (ref "C40") (pin "1") (pinfunction "1_1") (pintype "passive"))
      (node (ref "C44") (pin "1") (pinfunction "1_1") (pintype "passive"))
      (node (ref "C5") (pin "1") (pinfunction "1_1") (pintype "passive"))
      (node (ref "C57") (pin "1") (pinfunction "1_1") (pintype "passive"))
      (node (ref "C58") (pin "1") (pinfunction "1_1") (pintype "passive"))
      (node (ref "C62") (pin "1") (pinfunction "1_1") (pintype "passive"))
      (node (ref "L1") (pin "1") (pinfunction "1_1") (pintype "passive"))
      (node (ref "L10") (pin "1") (pinfunction "1_1") (pintype "passive"))
      (node (ref "L13") (pin "1") (pinfunction "1_1") (pintype "passive"))
      (node (ref "L14") (pin "1") (pinfunction "1_1") (pintype "passive"))
      (node (ref "L2") (pin "2") (pinfunction "2_2") (pintype "passive"))
      (node (ref "L3") (pin "1") (pinfunction "1_1") (pintype "passive"))
      (node (ref "L5") (pin "1") (pinfunction "1_1") (pintype "passive"))
      (node (ref "L6") (pin "1") (pinfunction "1_1") (pintype "passive"))
      (node (ref "L9") (pin "1") (pinfunction "1_1") (pintype "passive"))
      (node (ref "R3") (pin "2") (pinfunction "2_2") (pintype "passive"))
      (node (ref "SJ1") (pin "2") (pinfunction "2_2") (pintype "passive"))
      (node (ref "SJ10") (pin "1") (pinfunction "1_1") (pintype "passive"))
      (node (ref "SJ14") (pin "1") (pinfunction "1_1") (pintype "passive"))
      (node (ref "SJ3") (pin "1") (pinfunction "1_1") (pintype "passive"))
      (node (ref "SJ6") (pin "1") (pinfunction "1_1") (pintype "passive"))
      (node (ref "U1") (pin "4") (pinfunction "EN_4") (pintype "input"))
      (node (ref "U1") (pin "6") (pinfunction "VIN_6") (pintype "input"))
      (node (ref "U10") (pin "4") (pinfunction "EN_4") (pintype "input"))
      (node (ref "U10") (pin "6") (pinfunction "VIN_6") (pintype "input"))
      (node (ref "U13") (pin "C2") (pinfunction "~{SHDN}_C2") (pintype "bidirectional"))
      (node (ref "U13") (pin "C3") (pinfunction "VDD_C3") (pintype "bidirectional"))
      (node (ref "U14") (pin "4") (pinfunction "EN_4") (pintype "input"))
      (node (ref "U14") (pin "6") (pinfunction "VIN_6") (pintype "input"))
      (node (ref "U2") (pin "C2") (pinfunction "~{SHDN}_C2") (pintype "bidirectional"))
      (node (ref "U2") (pin "C3") (pinfunction "VDD_C3") (pintype "bidirectional"))
      (node (ref "U5") (pin "C2") (pinfunction "~{SHDN}_C2") (pintype "bidirectional"))
      (node (ref "U5") (pin "C3") (pinfunction "VDD_C3") (pintype "bidirectional"))
      (node (ref "U6") (pin "4") (pinfunction "EN_4") (pintype "input"))
      (node (ref "U6") (pin "6") (pinfunction "VIN_6") (pintype "input"))
      (node (ref "U9") (pin "C2") (pinfunction "~{SHDN}_C2") (pintype "bidirectional"))
      (node (ref "U9") (pin "C3") (pinfunction "VDD_C3") (pintype "bidirectional"))
    )
    (net (code "2") (name "/+3V3_B") (class "Default")
      (node (ref "C111") (pin "1") (pinfunction "1_1") (pintype "passive"))
      (node (ref "C112") (pin "1") (pinfunction "1_1") (pintype "passive"))
      (node (ref "C116") (pin "1") (pinfunction "1_1") (pintype "passive"))
      (node (ref "C129") (pin "1") (pinfunction "1_1") (pintype "passive"))
      (node (ref "C130") (pin "1") (pinfunction "1_1") (pintype "passive"))
      (node (ref "C134") (pin "1") (pinfunction "1_1") (pintype "passive"))
      (node (ref "C50") (pin "1") (pinfunction "1_1") (pintype "passive"))
      (node (ref "C51") (pin "1") (pinfunction "1_1") (pintype "passive"))
      (node (ref "C75") (pin "1") (pinfunction "1_1") (pintype "passive"))
      (node (ref "C76") (pin "1") (pinfunction "1_1") (pintype "passive"))
      (node (ref "C80") (pin "1") (pinfunction "1_1") (pintype "passive"))
      (node (ref "C93") (pin "1") (pinfunction "1_1") (pintype "passive"))
      (node (ref "C94") (pin "1") (pinfunction "1_1") (pintype "passive"))
      (node (ref "C98") (pin "1") (pinfunction "1_1") (pintype "passive"))
      (node (ref "L11") (pin "2") (pinfunction "2_2") (pintype "passive"))
      (node (ref "L17") (pin "1") (pinfunction "1_1") (pintype "passive"))
      (node (ref "L18") (pin "1") (pinfunction "1_1") (pintype "passive"))
      (node (ref "L21") (pin "1") (pinfunction "1_1") (pintype "passive"))
      (node (ref "L22") (pin "1") (pinfunction "1_1") (pintype "passive"))
      (node (ref "L25") (pin "1") (pinfunction "1_1") (pintype "passive"))
      (node (ref "L26") (pin "1") (pinfunction "1_1") (pintype "passive"))
      (node (ref "L29") (pin "1") (pinfunction "1_1") (pintype "passive"))
      (node (ref "L30") (pin "1") (pinfunction "1_1") (pintype "passive"))
      (node (ref "R11") (pin "2") (pinfunction "2_2") (pintype "passive"))
      (node (ref "SJ11") (pin "2") (pinfunction "2_2") (pintype "passive"))
      (node (ref "SJ18") (pin "1") (pinfunction "1_1") (pintype "passive"))
      (node (ref "SJ22") (pin "1") (pinfunction "1_1") (pintype "passive"))
      (node (ref "SJ26") (pin "1") (pinfunction "1_1") (pintype "passive"))
      (node (ref "SJ30") (pin "1") (pinfunction "1_1") (pintype "passive"))
      (node (ref "U17") (pin "C2") (pinfunction "~{SHDN}_C2") (pintype "bidirectional"))
      (node (ref "U17") (pin "C3") (pinfunction "VDD_C3") (pintype "bidirectional"))
      (node (ref "U18") (pin "4") (pinfunction "EN_4") (pintype "input"))
      (node (ref "U18") (pin "6") (pinfunction "VIN_6") (pintype "input"))
      (node (ref "U21") (pin "C2") (pinfunction "~{SHDN}_C2") (pintype "bidirectional"))
      (node (ref "U21") (pin "C3") (pinfunction "VDD_C3") (pintype "bidirectional"))
      (node (ref "U22") (pin "4") (pinfunction "EN_4") (pintype "input"))
      (node (ref "U22") (pin "6") (pinfunction "VIN_6") (pintype "input"))
      (node (ref "U25") (pin "C2") (pinfunction "~{SHDN}_C2") (pintype "bidirectional"))
      (node (ref "U25") (pin "C3") (pinfunction "VDD_C3") (pintype "bidirectional"))
      (node (ref "U26") (pin "4") (pinfunction "EN_4") (pintype "input"))
      (node (ref "U26") (pin "6") (pinfunction "VIN_6") (pintype "input"))
      (node (ref "U29") (pin "C2") (pinfunction "~{SHDN}_C2") (pintype "bidirectional"))
      (node (ref "U29") (pin "C3") (pinfunction "VDD_C3") (pintype "bidirectional"))
      (node (ref "U30") (pin "4") (pinfunction "EN_4") (pintype "input"))
      (node (ref "U30") (pin "6") (pinfunction "VIN_6") (pintype "input"))
    )
    (net (code "3") (name "/+3V3_C") (class "Default")
      (node (ref "C102") (pin "1") (pinfunction "1_1") (pintype "passive"))
      (node (ref "C103") (pin "1") (pinfunction "1_1") (pintype "passive"))
      (node (ref "C107") (pin "1") (pinfunction "1_1") (pintype "passive"))
      (node (ref "C138") (pin "1") (pinfunction "1_1") (pintype "passive"))
      (node (ref "C139") (pin "1") (pinfunction "1_1") (pintype "passive"))
      (node (ref "C143") (pin "1") (pinfunction "1_1") (pintype "passive"))
      (node (ref "C30") (pin "1") (pinfunction "1_1") (pintype "passive"))
      (node (ref "C31") (pin "1") (pinfunction "1_1") (pintype "passive"))
      (node (ref "C35") (pin "1") (pinfunction "1_1") (pintype "passive"))
      (node (ref "C66") (pin "1") (pinfunction "1_1") (pintype "passive"))
      (node (ref "C67") (pin "1") (pinfunction "1_1") (pintype "passive"))
      (node (ref "C71") (pin "1") (pinfunction "1_1") (pintype "passive"))
      (node (ref "C87") (pin "1") (pinfunction "1_1") (pintype "passive"))
      (node (ref "C88") (pin "1") (pinfunction "1_1") (pintype "passive"))
      (node (ref "L15") (pin "1") (pinfunction "1_1") (pintype "passive"))
      (node (ref "L16") (pin "1") (pinfunction "1_1") (pintype "passive"))
      (node (ref "L19") (pin "2") (pinfunction "2_2") (pintype "passive"))
      (node (ref "L23") (pin "1") (pinfunction "1_1") (pintype "passive"))
      (node (ref "L24") (pin "1") (pinfunction "1_1") (pintype "passive"))
      (node (ref "L31") (pin "1") (pinfunction "1_1") (pintype "passive"))
      (node (ref "L32") (pin "1") (pinfunction "1_1") (pintype "passive"))
      (node (ref "L7") (pin "1") (pinfunction "1_1") (pintype "passive"))
      (node (ref "L8") (pin "1") (pinfunction "1_1") (pintype "passive"))
      (node (ref "R33") (pin "2") (pinfunction "2_2") (pintype "passive"))
      (node (ref "SJ16") (pin "1") (pinfunction "1_1") (pintype "passive"))
      (node (ref "SJ19") (pin "2") (pinfunction "2_2") (pintype "passive"))
      (node (ref "SJ24") (pin "1") (pinfunction "1_1") (pintype "passive"))
      (node (ref "SJ32") (pin "1") (pinfunction "1_1") (pintype "passive"))
      (node (ref "SJ8") (pin "1") (pinfunction "1_1") (pintype "passive"))
      (node (ref "U15") (pin "C2") (pinfunction "~{SHDN}_C2") (pintype "bidirectional"))
      (node (ref "U15") (pin "C3") (pinfunction "VDD_C3") (pintype "bidirectional"))
      (node (ref "U16") (pin "4") (pinfunction "EN_4") (pintype "input"))
      (node (ref "U16") (pin "6") (pinfunction "VIN_6") (pintype "input"))
      (node (ref "U23") (pin "C2") (pinfunction "~{SHDN}_C2") (pintype "bidirectional"))
      (node (ref "U23") (pin "C3") (pinfunction "VDD_C3") (pintype "bidirectional"))
      (node (ref "U24") (pin "4") (pinfunction "EN_4") (pintype "input"))
      (node (ref "U24") (pin "6") (pinfunction "VIN_6") (pintype "input"))
      (node (ref "U31") (pin "C2") (pinfunction "~{SHDN}_C2") (pintype "bidirectional"))
      (node (ref "U31") (pin "C3") (pinfunction "VDD_C3") (pintype "bidirectional"))
      (node (ref "U32") (pin "4") (pinfunction "EN_4") (pintype "input"))
      (node (ref "U32") (pin "6") (pinfunction "VIN_6") (pintype "input"))
      (node (ref "U7") (pin "C2") (pinfunction "~{SHDN}_C2") (pintype "bidirectional"))
      (node (ref "U7") (pin "C3") (pinfunction "VDD_C3") (pintype "bidirectional"))
      (node (ref "U8") (pin "4") (pinfunction "EN_4") (pintype "input"))
      (node (ref "U8") (pin "6") (pinfunction "VIN_6") (pintype "input"))
    )
    (net (code "4") (name "/+3V3_D") (class "Default")
      (node (ref "C124") (pin "1") (pinfunction "1_1") (pintype "passive"))
      (node (ref "C125") (pin "1") (pinfunction "1_1") (pintype "passive"))
      (node (ref "C156") (pin "1") (pinfunction "1_1") (pintype "passive"))
      (node (ref "C157") (pin "1") (pinfunction "1_1") (pintype "passive"))
      (node (ref "C161") (pin "1") (pinfunction "1_1") (pintype "passive"))
      (node (ref "C174") (pin "1") (pinfunction "1_1") (pintype "passive"))
      (node (ref "C175") (pin "1") (pinfunction "1_1") (pintype "passive"))
      (node (ref "C179") (pin "1") (pinfunction "1_1") (pintype "passive"))
      (node (ref "C192") (pin "1") (pinfunction "1_1") (pintype "passive"))
      (node (ref "C193") (pin "1") (pinfunction "1_1") (pintype "passive"))
      (node (ref "C197") (pin "1") (pinfunction "1_1") (pintype "passive"))
      (node (ref "C210") (pin "1") (pinfunction "1_1") (pintype "passive"))
      (node (ref "C211") (pin "1") (pinfunction "1_1") (pintype "passive"))
      (node (ref "C215") (pin "1") (pinfunction "1_1") (pintype "passive"))
      (node (ref "L27") (pin "2") (pinfunction "2_2") (pintype "passive"))
      (node (ref "L35") (pin "1") (pinfunction "1_1") (pintype "passive"))
      (node (ref "L36") (pin "1") (pinfunction "1_1") (pintype "passive"))
      (node (ref "L39") (pin "1") (pinfunction "1_1") (pintype "passive"))
      (node (ref "L40") (pin "1") (pinfunction "1_1") (pintype "passive"))
      (node (ref "L43") (pin "1") (pinfunction "1_1") (pintype "passive"))
      (node (ref "L44") (pin "1") (pinfunction "1_1") (pintype "passive"))
      (node (ref "L47") (pin "1") (pinfunction "1_1") (pintype "passive"))
      (node (ref "L48") (pin "1") (pinfunction "1_1") (pintype "passive"))
      (node (ref "R55") (pin "2") (pinfunction "2_2") (pintype "passive"))
      (node (ref "SJ27") (pin "2") (pinfunction "2_2") (pintype "passive"))
      (node (ref "SJ36") (pin "1") (pinfunction "1_1") (pintype "passive"))
      (node (ref "SJ40") (pin "1") (pinfunction "1_1") (pintype "passive"))
      (node (ref "SJ44") (pin "1") (pinfunction "1_1") (pintype "passive"))
      (node (ref "SJ48") (pin "1") (pinfunction "1_1") (pintype "passive"))
      (node (ref "U35") (pin "C2") (pinfunction "~{SHDN}_C2") (pintype "bidirectional"))
      (node (ref "U35") (pin "C3") (pinfunction "VDD_C3") (pintype "bidirectional"))
      (node (ref "U36") (pin "4") (pinfunction "EN_4") (pintype "input"))
      (node (ref "U36") (pin "6") (pinfunction "VIN_6") (pintype "input"))
      (node (ref "U39") (pin "C2") (pinfunction "~{SHDN}_C2") (pintype "bidirectional"))
      (node (ref "U39") (pin "C3") (pinfunction "VDD_C3") (pintype "bidirectional"))
      (node (ref "U40") (pin "4") (pinfunction "EN_4") (pintype "input"))
      (node (ref "U40") (pin "6") (pinfunction "VIN_6") (pintype "input"))
      (node (ref "U43") (pin "C2") (pinfunction "~{SHDN}_C2") (pintype "bidirectional"))
      (node (ref "U43") (pin "C3") (pinfunction "VDD_C3") (pintype "bidirectional"))
      (node (ref "U44") (pin "4") (pinfunction "EN_4") (pintype "input"))
      (node (ref "U44") (pin "6") (pinfunction "VIN_6") (pintype "input"))
      (node (ref "U47") (pin "C2") (pinfunction "~{SHDN}_C2") (pintype "bidirectional"))
      (node (ref "U47") (pin "C3") (pinfunction "VDD_C3") (pintype "bidirectional"))
      (node (ref "U48") (pin "4") (pinfunction "EN_4") (pintype "input"))
      (node (ref "U48") (pin "6") (pinfunction "VIN_6") (pintype "input"))
    )
    (net (code "5") (name "/15V_1") (class "Default")
      (node (ref "C6") (pin "1") (pinfunction "1_1") (pintype "passive"))
      (node (ref "R1") (pin "2") (pinfunction "2_2") (pintype "passive"))
      (node (ref "R7") (pin "2") (pinfunction "2_2") (pintype "passive"))
      (node (ref "U1") (pin "5") (pinfunction "VOUT_5") (pintype "output"))
    )
    (net (code "6") (name "/15V_2") (class "Default")
      (node (ref "C27") (pin "1") (pinfunction "1_1") (pintype "passive"))
      (node (ref "R13") (pin "2") (pinfunction "2_2") (pintype "passive"))
      (node (ref "R17") (pin "2") (pinfunction "2_2") (pintype "passive"))
      (node (ref "U6") (pin "5") (pinfunction "VOUT_5") (pintype "output"))
    )
    (net (code "7") (name "/15V_3") (class "Default")
      (node (ref "C45") (pin "1") (pinfunction "1_1") (pintype "passive"))
      (node (ref "R25") (pin "2") (pinfunction "2_2") (pintype "passive"))
      (node (ref "R29") (pin "2") (pinfunction "2_2") (pintype "passive"))
      (node (ref "U10") (pin "5") (pinfunction "VOUT_5") (pintype "output"))
    )
    (net (code "8") (name "/15V_4") (class "Default")
      (node (ref "C63") (pin "1") (pinfunction "1_1") (pintype "passive"))
      (node (ref "R37") (pin "2") (pinfunction "2_2") (pintype "passive"))
      (node (ref "R41") (pin "2") (pinfunction "2_2") (pintype "passive"))
      (node (ref "U14") (pin "5") (pinfunction "VOUT_5") (pintype "output"))
    )
    (net (code "9") (name "/15V_5") (class "Default")
      (node (ref "C81") (pin "1") (pinfunction "1_1") (pintype "passive"))
      (node (ref "R49") (pin "2") (pinfunction "2_2") (pintype "passive"))
      (node (ref "R53") (pin "2") (pinfunction "2_2") (pintype "passive"))
      (node (ref "U18") (pin "5") (pinfunction "VOUT_5") (pintype "output"))
    )
    (net (code "10") (name "/15V_6") (class "Default")
      (node (ref "C99") (pin "1") (pinfunction "1_1") (pintype "passive"))
      (node (ref "R61") (pin "2") (pinfunction "2_2") (pintype "passive"))
      (node (ref "R65") (pin "2") (pinfunction "2_2") (pintype "passive"))
      (node (ref "U22") (pin "5") (pinfunction "VOUT_5") (pintype "output"))
    )
    (net (code "11") (name "/15V_7") (class "Default")
      (node (ref "C117") (pin "1") (pinfunction "1_1") (pintype "passive"))
      (node (ref "R73") (pin "2") (pinfunction "2_2") (pintype "passive"))
      (node (ref "R77") (pin "2") (pinfunction "2_2") (pintype "passive"))
      (node (ref "U26") (pin "5") (pinfunction "VOUT_5") (pintype "output"))
    )
    (net (code "12") (name "/15V_8") (class "Default")
      (node (ref "C135") (pin "1") (pinfunction "1_1") (pintype "passive"))
      (node (ref "R85") (pin "2") (pinfunction "2_2") (pintype "passive"))
      (node (ref "R89") (pin "2") (pinfunction "2_2") (pintype "passive"))
      (node (ref "U30") (pin "5") (pinfunction "VOUT_5") (pintype "output"))
    )
    (net (code "13") (name "/15V_9") (class "Default")
      (node (ref "C36") (pin "1") (pinfunction "1_1") (pintype "passive"))
      (node (ref "R19") (pin "2") (pinfunction "2_2") (pintype "passive"))
      (node (ref "R23") (pin "2") (pinfunction "2_2") (pintype "passive"))
      (node (ref "U8") (pin "5") (pinfunction "VOUT_5") (pintype "output"))
    )
    (net (code "14") (name "/15V_10") (class "Default")
      (node (ref "C72") (pin "1") (pinfunction "1_1") (pintype "passive"))
      (node (ref "R43") (pin "2") (pinfunction "2_2") (pintype "passive"))
      (node (ref "R47") (pin "2") (pinfunction "2_2") (pintype "passive"))
      (node (ref "U16") (pin "5") (pinfunction "VOUT_5") (pintype "output"))
    )
    (net (code "15") (name "/15V_11") (class "Default")
      (node (ref "C108") (pin "1") (pinfunction "1_1") (pintype "passive"))
      (node (ref "R67") (pin "2") (pinfunction "2_2") (pintype "passive"))
      (node (ref "R71") (pin "2") (pinfunction "2_2") (pintype "passive"))
      (node (ref "U24") (pin "5") (pinfunction "VOUT_5") (pintype "output"))
    )
    (net (code "16") (name "/15V_12") (class "Default")
      (node (ref "C144") (pin "1") (pinfunction "1_1") (pintype "passive"))
      (node (ref "R91") (pin "2") (pinfunction "2_2") (pintype "passive"))
      (node (ref "R95") (pin "2") (pinfunction "2_2") (pintype "passive"))
      (node (ref "U32") (pin "5") (pinfunction "VOUT_5") (pintype "output"))
    )
    (net (code "17") (name "/15V_13") (class "Default")
      (node (ref "C162") (pin "1") (pinfunction "1_1") (pintype "passive"))
      (node (ref "R103") (pin "2") (pinfunction "2_2") (pintype "passive"))
      (node (ref "R107") (pin "2") (pinfunction "2_2") (pintype "passive"))
      (node (ref "U36") (pin "5") (pinfunction "VOUT_5") (pintype "output"))
    )
    (net (code "18") (name "/15V_14") (class "Default")
      (node (ref "C180") (pin "1") (pinfunction "1_1") (pintype "passive"))
      (node (ref "R115") (pin "2") (pinfunction "2_2") (pintype "passive"))
      (node (ref "R119") (pin "2") (pinfunction "2_2") (pintype "passive"))
      (node (ref "U40") (pin "5") (pinfunction "VOUT_5") (pintype "output"))
    )
    (net (code "19") (name "/15V_15") (class "Default")
      (node (ref "C198") (pin "1") (pinfunction "1_1") (pintype "passive"))
      (node (ref "R127") (pin "2") (pinfunction "2_2") (pintype "passive"))
      (node (ref "R131") (pin "2") (pinfunction "2_2") (pintype "passive"))
      (node (ref "U44") (pin "5") (pinfunction "VOUT_5") (pintype "output"))
    )
    (net (code "20") (name "/15V_16") (class "Default")
      (node (ref "C216") (pin "1") (pinfunction "1_1") (pintype "passive"))
      (node (ref "R139") (pin "2") (pinfunction "2_2") (pintype "passive"))
      (node (ref "R143") (pin "2") (pinfunction "2_2") (pintype "passive"))
      (node (ref "U48") (pin "5") (pinfunction "VOUT_5") (pintype "output"))
    )
    (net (code "21") (name "/IN+_1") (class "Default")
      (node (ref "C1") (pin "1") (pinfunction "1_1") (pintype "passive"))
      (node (ref "JP1") (pin "1") (pinfunction "1_1") (pintype "passive"))
    )
    (net (code "22") (name "/IN+_2") (class "Default")
      (node (ref "C19") (pin "1") (pinfunction "1_1") (pintype "passive"))
      (node (ref "JP5") (pin "1") (pinfunction "1_1") (pintype "passive"))
    )
    (net (code "23") (name "/IN+_3") (class "Default")
      (node (ref "C37") (pin "1") (pinfunction "1_1") (pintype "passive"))
      (node (ref "JP9") (pin "1") (pinfunction "1_1") (pintype "passive"))
    )
    (net (code "24") (name "/IN+_4") (class "Default")
      (node (ref "C55") (pin "1") (pinfunction "1_1") (pintype "passive"))
      (node (ref "JP13") (pin "1") (pinfunction "1_1") (pintype "passive"))
    )
    (net (code "25") (name "/IN+_5") (class "Default")
      (node (ref "C73") (pin "1") (pinfunction "1_1") (pintype "passive"))
      (node (ref "JP17") (pin "1") (pinfunction "1_1") (pintype "passive"))
    )
    (net (code "26") (name "/IN+_6") (class "Default")
      (node (ref "C91") (pin "1") (pinfunction "1_1") (pintype "passive"))
      (node (ref "JP21") (pin "1") (pinfunction "1_1") (pintype "passive"))
    )
    (net (code "27") (name "/IN+_7") (class "Default")
      (node (ref "C109") (pin "1") (pinfunction "1_1") (pintype "passive"))
      (node (ref "JP25") (pin "1") (pinfunction "1_1") (pintype "passive"))
    )
    (net (code "28") (name "/IN+_8") (class "Default")
      (node (ref "C127") (pin "1") (pinfunction "1_1") (pintype "passive"))
      (node (ref "JP29") (pin "1") (pinfunction "1_1") (pintype "passive"))
    )
    (net (code "29") (name "/IN+_9") (class "Default")
      (node (ref "C28") (pin "1") (pinfunction "1_1") (pintype "passive"))
      (node (ref "JP7") (pin "1") (pinfunction "1_1") (pintype "passive"))
    )
    (net (code "30") (name "/IN+_10") (class "Default")
      (node (ref "C64") (pin "1") (pinfunction "1_1") (pintype "passive"))
      (node (ref "JP15") (pin "1") (pinfunction "1_1") (pintype "passive"))
    )
    (net (code "31") (name "/IN+_11") (class "Default")
      (node (ref "C100") (pin "1") (pinfunction "1_1") (pintype "passive"))
      (node (ref "JP23") (pin "1") (pinfunction "1_1") (pintype "passive"))
    )
    (net (code "32") (name "/IN+_12") (class "Default")
      (node (ref "C136") (pin "1") (pinfunction "1_1") (pintype "passive"))
      (node (ref "JP31") (pin "1") (pinfunction "1_1") (pintype "passive"))
    )
    (net (code "33") (name "/IN+_13") (class "Default")
      (node (ref "C154") (pin "1") (pinfunction "1_1") (pintype "passive"))
      (node (ref "JP35") (pin "1") (pinfunction "1_1") (pintype "passive"))
    )
    (net (code "34") (name "/IN+_14") (class "Default")
      (node (ref "C172") (pin "1") (pinfunction "1_1") (pintype "passive"))
      (node (ref "JP39") (pin "1") (pinfunction "1_1") (pintype "passive"))
    )
    (net (code "35") (name "/IN+_15") (class "Default")
      (node (ref "C190") (pin "1") (pinfunction "1_1") (pintype "passive"))
      (node (ref "JP43") (pin "1") (pinfunction "1_1") (pintype "passive"))
    )
    (net (code "36") (name "/IN+_16") (class "Default")
      (node (ref "C208") (pin "1") (pinfunction "1_1") (pintype "passive"))
      (node (ref "JP47") (pin "1") (pinfunction "1_1") (pintype "passive"))
    )
    (net (code "37") (name "/IN-_1") (class "Default")
      (node (ref "C2") (pin "1") (pinfunction "1_1") (pintype "passive"))
      (node (ref "SJ2") (pin "2") (pinfunction "2_2") (pintype "passive"))
    )
    (net (code "38") (name "/IN-_2") (class "Default")
      (node (ref "C20") (pin "1") (pinfunction "1_1") (pintype "passive"))
      (node (ref "SJ5") (pin "2") (pinfunction "2_2") (pintype "passive"))
    )
    (net (code "39") (name "/IN-_3") (class "Default")
      (node (ref "C38") (pin "1") (pinfunction "1_1") (pintype "passive"))
      (node (ref "SJ9") (pin "2") (pinfunction "2_2") (pintype "passive"))
    )
    (net (code "40") (name "/IN-_4") (class "Default")
      (node (ref "C56") (pin "1") (pinfunction "1_1") (pintype "passive"))
      (node (ref "SJ13") (pin "2") (pinfunction "2_2") (pintype "passive"))
    )
    (net (code "41") (name "/IN-_5") (class "Default")
      (node (ref "C74") (pin "1") (pinfunction "1_1") (pintype "passive"))
      (node (ref "SJ17") (pin "2") (pinfunction "2_2") (pintype "passive"))
    )
    (net (code "42") (name "/IN-_6") (class "Default")
      (node (ref "C92") (pin "1") (pinfunction "1_1") (pintype "passive"))
      (node (ref "SJ21") (pin "2") (pinfunction "2_2") (pintype "passive"))
    )
    (net (code "43") (name "/IN-_7") (class "Default")
      (node (ref "C110") (pin "1") (pinfunction "1_1") (pintype "passive"))
      (node (ref "SJ25") (pin "2") (pinfunction "2_2") (pintype "passive"))
    )
    (net (code "44") (name "/IN-_8") (class "Default")
      (node (ref "C128") (pin "1") (pinfunction "1_1") (pintype "passive"))
      (node (ref "SJ29") (pin "2") (pinfunction "2_2") (pintype "passive"))
    )
    (net (code "45") (name "/IN-_9") (class "Default")
      (node (ref "C29") (pin "1") (pinfunction "1_1") (pintype "passive"))
      (node (ref "SJ7") (pin "2") (pinfunction "2_2") (pintype "passive"))
    )
    (net (code "46") (name "/IN-_10") (class "Default")
      (node (ref "C65") (pin "1") (pinfunction "1_1") (pintype "passive"))
      (node (ref "SJ15") (pin "2") (pinfunction "2_2") (pintype "passive"))
    )
    (net (code "47") (name "/IN-_11") (class "Default")
      (node (ref "C101") (pin "1") (pinfunction "1_1") (pintype "passive"))
      (node (ref "SJ23") (pin "2") (pinfunction "2_2") (pintype "passive"))
    )
    (net (code "48") (name "/IN-_12") (class "Default")
      (node (ref "C137") (pin "1") (pinfunction "1_1") (pintype "passive"))
      (node (ref "SJ31") (pin "2") (pinfunction "2_2") (pintype "passive"))
    )
    (net (code "49") (name "/IN-_13") (class "Default")
      (node (ref "C155") (pin "1") (pinfunction "1_1") (pintype "passive"))
      (node (ref "SJ35") (pin "2") (pinfunction "2_2") (pintype "passive"))
    )
    (net (code "50") (name "/IN-_14") (class "Default")
      (node (ref "C173") (pin "1") (pinfunction "1_1") (pintype "passive"))
      (node (ref "SJ39") (pin "2") (pinfunction "2_2") (pintype "passive"))
    )
    (net (code "51") (name "/IN-_15") (class "Default")
      (node (ref "C191") (pin "1") (pinfunction "1_1") (pintype "passive"))
      (node (ref "SJ43") (pin "2") (pinfunction "2_2") (pintype "passive"))
    )
    (net (code "52") (name "/IN-_16") (class "Default")
      (node (ref "C209") (pin "1") (pinfunction "1_1") (pintype "passive"))
      (node (ref "SJ47") (pin "2") (pinfunction "2_2") (pintype "passive"))
    )
    (net (code "53") (name "/OUT+_1") (class "Default")
      (node (ref "JP2") (pin "1") (pinfunction "1_1") (pintype "passive"))
      (node (ref "R5") (pin "2") (pinfunction "2_2") (pintype "passive"))
    )
    (net (code "54") (name "/OUT+_2") (class "Default")
      (node (ref "JP6") (pin "1") (pinfunction "1_1") (pintype "passive"))
      (node (ref "R15") (pin "2") (pinfunction "2_2") (pintype "passive"))
    )
    (net (code "55") (name "/OUT+_3") (class "Default")
      (node (ref "JP10") (pin "1") (pinfunction "1_1") (pintype "passive"))
      (node (ref "R27") (pin "2") (pinfunction "2_2") (pintype "passive"))
    )
    (net (code "56") (name "/OUT+_4") (class "Default")
      (node (ref "JP14") (pin "1") (pinfunction "1_1") (pintype "passive"))
      (node (ref "R39") (pin "2") (pinfunction "2_2") (pintype "passive"))
    )
    (net (code "57") (name "/OUT+_5") (class "Default")
      (node (ref "JP18") (pin "1") (pinfunction "1_1") (pintype "passive"))
      (node (ref "R51") (pin "2") (pinfunction "2_2") (pintype "passive"))
    )
    (net (code "58") (name "/OUT+_6") (class "Default")
      (node (ref "JP22") (pin "1") (pinfunction "1_1") (pintype "passive"))
      (node (ref "R63") (pin "2") (pinfunction "2_2") (pintype "passive"))
    )
    (net (code "59") (name "/OUT+_7") (class "Default")
      (node (ref "JP26") (pin "1") (pinfunction "1_1") (pintype "passive"))
      (node (ref "R75") (pin "2") (pinfunction "2_2") (pintype "passive"))
    )
    (net (code "60") (name "/OUT+_8") (class "Default")
      (node (ref "JP30") (pin "1") (pinfunction "1_1") (pintype "passive"))
      (node (ref "R87") (pin "2") (pinfunction "2_2") (pintype "passive"))
    )
    (net (code "61") (name "/OUT+_9") (class "Default")
      (node (ref "JP8") (pin "1") (pinfunction "1_1") (pintype "passive"))
      (node (ref "R21") (pin "2") (pinfunction "2_2") (pintype "passive"))
    )
    (net (code "62") (name "/OUT+_10") (class "Default")
      (node (ref "JP16") (pin "1") (pinfunction "1_1") (pintype "passive"))
      (node (ref "R45") (pin "2") (pinfunction "2_2") (pintype "passive"))
    )
    (net (code "63") (name "/OUT+_11") (class "Default")
      (node (ref "JP24") (pin "1") (pinfunction "1_1") (pintype "passive"))
      (node (ref "R69") (pin "2") (pinfunction "2_2") (pintype "passive"))
    )
    (net (code "64") (name "/OUT+_12") (class "Default")
      (node (ref "JP32") (pin "1") (pinfunction "1_1") (pintype "passive"))
      (node (ref "R93") (pin "2") (pinfunction "2_2") (pintype "passive"))
    )
    (net (code "65") (name "/OUT+_13") (class "Default")
      (node (ref "JP36") (pin "1") (pinfunction "1_1") (pintype "passive"))
      (node (ref "R105") (pin "2") (pinfunction "2_2") (pintype "passive"))
    )
    (net (code "66") (name "/OUT+_14") (class "Default")
      (node (ref "JP40") (pin "1") (pinfunction "1_1") (pintype "passive"))
      (node (ref "R117") (pin "2") (pinfunction "2_2") (pintype "passive"))
    )
    (net (code "67") (name "/OUT+_15") (class "Default")
      (node (ref "JP44") (pin "1") (pinfunction "1_1") (pintype "passive"))
      (node (ref "R129") (pin "2") (pinfunction "2_2") (pintype "passive"))
    )
    (net (code "68") (name "/OUT+_16") (class "Default")
      (node (ref "JP48") (pin "1") (pinfunction "1_1") (pintype "passive"))
      (node (ref "R141") (pin "2") (pinfunction "2_2") (pintype "passive"))
    )
    (net (code "69") (name "/OUT-_1") (class "Default")
      (node (ref "JP2") (pin "2") (pinfunction "2_2") (pintype "passive"))
      (node (ref "R6") (pin "2") (pinfunction "2_2") (pintype "passive"))
    )
    (net (code "70") (name "/OUT-_2") (class "Default")
      (node (ref "JP6") (pin "2") (pinfunction "2_2") (pintype "passive"))
      (node (ref "R16") (pin "2") (pinfunction "2_2") (pintype "passive"))
    )
    (net (code "71") (name "/OUT-_3") (class "Default")
      (node (ref "JP10") (pin "2") (pinfunction "2_2") (pintype "passive"))
      (node (ref "R28") (pin "2") (pinfunction "2_2") (pintype "passive"))
    )
    (net (code "72") (name "/OUT-_4") (class "Default")
      (node (ref "JP14") (pin "2") (pinfunction "2_2") (pintype "passive"))
      (node (ref "R40") (pin "2") (pinfunction "2_2") (pintype "passive"))
    )
    (net (code "73") (name "/OUT-_5") (class "Default")
      (node (ref "JP18") (pin "2") (pinfunction "2_2") (pintype "passive"))
      (node (ref "R52") (pin "2") (pinfunction "2_2") (pintype "passive"))
    )
    (net (code "74") (name "/OUT-_6") (class "Default")
      (node (ref "JP22") (pin "2") (pinfunction "2_2") (pintype "passive"))
      (node (ref "R64") (pin "2") (pinfunction "2_2") (pintype "passive"))
    )
    (net (code "75") (name "/OUT-_7") (class "Default")
      (node (ref "JP26") (pin "2") (pinfunction "2_2") (pintype "passive"))
      (node (ref "R76") (pin "2") (pinfunction "2_2") (pintype "passive"))
    )
    (net (code "76") (name "/OUT-_8") (class "Default")
      (node (ref "JP30") (pin "2") (pinfunction "2_2") (pintype "passive"))
      (node (ref "R88") (pin "2") (pinfunction "2_2") (pintype "passive"))
    )
    (net (code "77") (name "/OUT-_9") (class "Default")
      (node (ref "JP8") (pin "2") (pinfunction "2_2") (pintype "passive"))
      (node (ref "R22") (pin "2") (pinfunction "2_2") (pintype "passive"))
    )
    (net (code "78") (name "/OUT-_10") (class "Default")
      (node (ref "JP16") (pin "2") (pinfunction "2_2") (pintype "passive"))
      (node (ref "R46") (pin "2") (pinfunction "2_2") (pintype "passive"))
    )
    (net (code "79") (name "/OUT-_11") (class "Default")
      (node (ref "JP24") (pin "2") (pinfunction "2_2") (pintype "passive"))
      (node (ref "R70") (pin "2") (pinfunction "2_2") (pintype "passive"))
    )
    (net (code "80") (name "/OUT-_12") (class "Default")
      (node (ref "JP32") (pin "2") (pinfunction "2_2") (pintype "passive"))
      (node (ref "R94") (pin "2") (pinfunction "2_2") (pintype "passive"))
    )
    (net (code "81") (name "/OUT-_13") (class "Default")
      (node (ref "JP36") (pin "2") (pinfunction "2_2") (pintype "passive"))
      (node (ref "R106") (pin "2") (pinfunction "2_2") (pintype "passive"))
    )
    (net (code "82") (name "/OUT-_14") (class "Default")
      (node (ref "JP40") (pin "2") (pinfunction "2_2") (pintype "passive"))
      (node (ref "R118") (pin "2") (pinfunction "2_2") (pintype "passive"))
    )
    (net (code "83") (name "/OUT-_15") (class "Default")
      (node (ref "JP44") (pin "2") (pinfunction "2_2") (pintype "passive"))
      (node (ref "R130") (pin "2") (pinfunction "2_2") (pintype "passive"))
    )
    (net (code "84") (name "/OUT-_16") (class "Default")
      (node (ref "JP48") (pin "2") (pinfunction "2_2") (pintype "passive"))
      (node (ref "R142") (pin "2") (pinfunction "2_2") (pintype "passive"))
    )
    (net (code "85") (name "/VIN") (class "Default")
      (node (ref "C10") (pin "1") (pinfunction "+_1") (pintype "passive"))
      (node (ref "C11") (pin "1") (pinfunction "1_1") (pintype "passive"))
      (node (ref "C12") (pin "1") (pinfunction "1_1") (pintype "passive"))
      (node (ref "C121") (pin "1") (pinfunction "1_1") (pintype "passive"))
      (node (ref "C122") (pin "1") (pinfunction "1_1") (pintype "passive"))
      (node (ref "C13") (pin "1") (pinfunction "+_1") (pintype "passive"))
      (node (ref "C14") (pin "1") (pinfunction "+_1") (pintype "passive"))
      (node (ref "C47") (pin "1") (pinfunction "1_1") (pintype "passive"))
      (node (ref "C48") (pin "1") (pinfunction "1_1") (pintype "passive"))
      (node (ref "C84") (pin "1") (pinfunction "1_1") (pintype "passive"))
      (node (ref "C85") (pin "1") (pinfunction "1_1") (pintype "passive"))
      (node (ref "INPUT") (pin "1") (pinfunction "1_1") (pintype "passive"))
      (node (ref "LSP1") (pin "MP") (pinfunction "MP_MP") (pintype "passive"))
      (node (ref "LSP3") (pin "MP") (pinfunction "MP_MP") (pintype "passive"))
      (node (ref "SJ1") (pin "1") (pinfunction "1_1") (pintype "passive"))
      (node (ref "SJ11") (pin "1") (pinfunction "1_1") (pintype "passive"))
      (node (ref "SJ19") (pin "1") (pinfunction "1_1") (pintype "passive"))
      (node (ref "SJ27") (pin "1") (pinfunction "1_1") (pintype "passive"))
      (node (ref "U$1") (pin "3") (pinfunction "VIN_3") (pintype "bidirectional"))
      (node (ref "U$1") (pin "5") (pinfunction "EN_5") (pintype "bidirectional"))
      (node (ref "U$10") (pin "3") (pinfunction "VIN_3") (pintype "bidirectional"))
      (node (ref "U$10") (pin "5") (pinfunction "EN_5") (pintype "bidirectional"))
      (node (ref "U$17") (pin "3") (pinfunction "VIN_3") (pintype "bidirectional"))
      (node (ref "U$17") (pin "5") (pinfunction "EN_5") (pintype "bidirectional"))
      (node (ref "U$21") (pin "3") (pinfunction "VIN_3") (pintype "bidirectional"))
      (node (ref "U$21") (pin "5") (pinfunction "EN_5") (pintype "bidirectional"))
    )
    (net (code "86") (name "GND") (class "Default")
      (node (ref "C10") (pin "2") (pinfunction "-_2") (pintype "passive"))
      (node (ref "C102") (pin "2") (pinfunction "2_2") (pintype "passive"))
      (node (ref "C103") (pin "2") (pinfunction "2_2") (pintype "passive"))
      (node (ref "C106") (pin "1") (pinfunction "1_1") (pintype "passive"))
      (node (ref "C107") (pin "2") (pinfunction "2_2") (pintype "passive"))
      (node (ref "C108") (pin "2") (pinfunction "2_2") (pintype "passive"))
      (node (ref "C11") (pin "2") (pinfunction "2_2") (pintype "passive"))
      (node (ref "C111") (pin "2") (pinfunction "2_2") (pintype "passive"))
      (node (ref "C112") (pin "2") (pinfunction "2_2") (pintype "passive"))
      (node (ref "C115") (pin "1") (pinfunction "1_1") (pintype "passive"))
      (node (ref "C116") (pin "2") (pinfunction "2_2") (pintype "passive"))
      (node (ref "C117") (pin "2") (pinfunction "2_2") (pintype "passive"))
      (node (ref "C12") (pin "2") (pinfunction "2_2") (pintype "passive"))
      (node (ref "C121") (pin "2") (pinfunction "2_2") (pintype "passive"))
      (node (ref "C122") (pin "2") (pinfunction "2_2") (pintype "passive"))
      (node (ref "C124") (pin "2") (pinfunction "2_2") (pintype "passive"))
      (node (ref "C125") (pin "2") (pinfunction "2_2") (pintype "passive"))
      (node (ref "C129") (pin "2") (pinfunction "2_2") (pintype "passive"))
      (node (ref "C13") (pin "2") (pinfunction "-_2") (pintype "passive"))
      (node (ref "C130") (pin "2") (pinfunction "2_2") (pintype "passive"))
      (node (ref "C133") (pin "1") (pinfunction "1_1") (pintype "passive"))
      (node (ref "C134") (pin "2") (pinfunction "2_2") (pintype "passive"))
      (node (ref "C135") (pin "2") (pinfunction "2_2") (pintype "passive"))
      (node (ref "C138") (pin "2") (pinfunction "2_2") (pintype "passive"))
      (node (ref "C139") (pin "2") (pinfunction "2_2") (pintype "passive"))
      (node (ref "C14") (pin "2") (pinfunction "-_2") (pintype "passive"))
      (node (ref "C142") (pin "1") (pinfunction "1_1") (pintype "passive"))
      (node (ref "C143") (pin "2") (pinfunction "2_2") (pintype "passive"))
      (node (ref "C144") (pin "2") (pinfunction "2_2") (pintype "passive"))
      (node (ref "C156") (pin "2") (pinfunction "2_2") (pintype "passive"))
      (node (ref "C157") (pin "2") (pinfunction "2_2") (pintype "passive"))
      (node (ref "C16") (pin "2") (pinfunction "2_2") (pintype "passive"))
      (node (ref "C160") (pin "1") (pinfunction "1_1") (pintype "passive"))
      (node (ref "C161") (pin "2") (pinfunction "2_2") (pintype "passive"))
      (node (ref "C162") (pin "2") (pinfunction "2_2") (pintype "passive"))
      (node (ref "C17") (pin "2") (pinfunction "2_2") (pintype "passive"))
      (node (ref "C174") (pin "2") (pinfunction "2_2") (pintype "passive"))
      (node (ref "C175") (pin "2") (pinfunction "2_2") (pintype "passive"))
      (node (ref "C178") (pin "1") (pinfunction "1_1") (pintype "passive"))
      (node (ref "C179") (pin "2") (pinfunction "2_2") (pintype "passive"))
      (node (ref "C180") (pin "2") (pinfunction "2_2") (pintype "passive"))
      (node (ref "C192") (pin "2") (pinfunction "2_2") (pintype "passive"))
      (node (ref "C193") (pin "2") (pinfunction "2_2") (pintype "passive"))
      (node (ref "C196") (pin "1") (pinfunction "1_1") (pintype "passive"))
      (node (ref "C197") (pin "2") (pinfunction "2_2") (pintype "passive"))
      (node (ref "C198") (pin "2") (pinfunction "2_2") (pintype "passive"))
      (node (ref "C21") (pin "2") (pinfunction "2_2") (pintype "passive"))
      (node (ref "C210") (pin "2") (pinfunction "2_2") (pintype "passive"))
      (node (ref "C211") (pin "2") (pinfunction "2_2") (pintype "passive"))
      (node (ref "C214") (pin "1") (pinfunction "1_1") (pintype "passive"))
      (node (ref "C215") (pin "2") (pinfunction "2_2") (pintype "passive"))
      (node (ref "C216") (pin "2") (pinfunction "2_2") (pintype "passive"))
      (node (ref "C22") (pin "2") (pinfunction "2_2") (pintype "passive"))
      (node (ref "C25") (pin "1") (pinfunction "1_1") (pintype "passive"))
      (node (ref "C26") (pin "2") (pinfunction "2_2") (pintype "passive"))
      (node (ref "C27") (pin "2") (pinfunction "2_2") (pintype "passive"))
      (node (ref "C3") (pin "2") (pinfunction "2_2") (pintype "passive"))
      (node (ref "C30") (pin "2") (pinfunction "2_2") (pintype "passive"))
      (node (ref "C31") (pin "2") (pinfunction "2_2") (pintype "passive"))
      (node (ref "C34") (pin "1") (pinfunction "1_1") (pintype "passive"))
      (node (ref "C35") (pin "2") (pinfunction "2_2") (pintype "passive"))
      (node (ref "C36") (pin "2") (pinfunction "2_2") (pintype "passive"))
      (node (ref "C39") (pin "2") (pinfunction "2_2") (pintype "passive"))
      (node (ref "C4") (pin "2") (pinfunction "2_2") (pintype "passive"))
      (node (ref "C40") (pin "2") (pinfunction "2_2") (pintype "passive"))
      (node (ref "C43") (pin "1") (pinfunction "1_1") (pintype "passive"))
      (node (ref "C44") (pin "2") (pinfunction "2_2") (pintype "passive"))
      (node (ref "C45") (pin "2") (pinfunction "2_2") (pintype "passive"))
      (node (ref "C47") (pin "2") (pinfunction "2_2") (pintype "passive"))
      (node (ref "C48") (pin "2") (pinfunction "2_2") (pintype "passive"))
      (node (ref "C5") (pin "2") (pinfunction "2_2") (pintype "passive"))
      (node (ref "C50") (pin "2") (pinfunction "2_2") (pintype "passive"))
      (node (ref "C51") (pin "2") (pinfunction "2_2") (pintype "passive"))
      (node (ref "C57") (pin "2") (pinfunction "2_2") (pintype "passive"))
      (node (ref "C58") (pin "2") (pinfunction "2_2") (pintype "passive"))
      (node (ref "C6") (pin "2") (pinfunction "2_2") (pintype "passive"))
      (node (ref "C61") (pin "1") (pinfunction "1_1") (pintype "passive"))
      (node (ref "C62") (pin "2") (pinfunction "2_2") (pintype "passive"))
      (node (ref "C63") (pin "2") (pinfunction "2_2") (pintype "passive"))
      (node (ref "C66") (pin "2") (pinfunction "2_2") (pintype "passive"))
      (node (ref "C67") (pin "2") (pinfunction "2_2") (pintype "passive"))
      (node (ref "C70") (pin "1") (pinfunction "1_1") (pintype "passive"))
      (node (ref "C71") (pin "2") (pinfunction "2_2") (pintype "passive"))
      (node (ref "C72") (pin "2") (pinfunction "2_2") (pintype "passive"))
      (node (ref "C75") (pin "2") (pinfunction "2_2") (pintype "passive"))
      (node (ref "C76") (pin "2") (pinfunction "2_2") (pintype "passive"))
      (node (ref "C79") (pin "1") (pinfunction "1_1") (pintype "passive"))
      (node (ref "C80") (pin "2") (pinfunction "2_2") (pintype "passive"))
      (node (ref "C81") (pin "2") (pinfunction "2_2") (pintype "passive"))
      (node (ref "C84") (pin "2") (pinfunction "2_2") (pintype "passive"))
      (node (ref "C85") (pin "2") (pinfunction "2_2") (pintype "passive"))
      (node (ref "C87") (pin "2") (pinfunction "2_2") (pintype "passive"))
      (node (ref "C88") (pin "2") (pinfunction "2_2") (pintype "passive"))
      (node (ref "C9") (pin "1") (pinfunction "1_1") (pintype "passive"))
      (node (ref "C93") (pin "2") (pinfunction "2_2") (pintype "passive"))
      (node (ref "C94") (pin "2") (pinfunction "2_2") (pintype "passive"))
      (node (ref "C97") (pin "1") (pinfunction "1_1") (pintype "passive"))
      (node (ref "C98") (pin "2") (pinfunction "2_2") (pintype "passive"))
      (node (ref "C99") (pin "2") (pinfunction "2_2") (pintype "passive"))
      (node (ref "INPUT") (pin "2") (pinfunction "2_2") (pintype "passive"))
      (node (ref "LSP2") (pin "MP") (pinfunction "MP_MP") (pintype "passive"))
      (node (ref "LSP4") (pin "MP") (pinfunction "MP_MP") (pintype "passive"))
      (node (ref "R104") (pin "1") (pinfunction "1_1") (pintype "passive"))
      (node (ref "R108") (pin "1") (pinfunction "1_1") (pintype "passive"))
      (node (ref "R116") (pin "1") (pinfunction "1_1") (pintype "passive"))
      (node (ref "R12") (pin "1") (pinfunction "1_1") (pintype "passive"))
      (node (ref "R120") (pin "1") (pinfunction "1_1") (pintype "passive"))
      (node (ref "R128") (pin "1") (pinfunction "1_1") (pintype "passive"))
      (node (ref "R132") (pin "1") (pinfunction "1_1") (pintype "passive"))
      (node (ref "R14") (pin "1") (pinfunction "1_1") (pintype "passive"))
      (node (ref "R140") (pin "1") (pinfunction "1_1") (pintype "passive"))
      (node (ref "R144") (pin "1") (pinfunction "1_1") (pintype "passive"))
      (node (ref "R18") (pin "1") (pinfunction "1_1") (pintype "passive"))
      (node (ref "R2") (pin "1") (pinfunction "1_1") (pintype "passive"))
      (node (ref "R20") (pin "1") (pinfunction "1_1") (pintype "passive"))
      (node (ref "R24") (pin "1") (pinfunction "1_1") (pintype "passive"))
      (node (ref "R26") (pin "1") (pinfunction "1_1") (pintype "passive"))
      (node (ref "R30") (pin "1") (pinfunction "1_1") (pintype "passive"))
      (node (ref "R34") (pin "1") (pinfunction "1_1") (pintype "passive"))
      (node (ref "R38") (pin "1") (pinfunction "1_1") (pintype "passive"))
      (node (ref "R4") (pin "1") (pinfunction "1_1") (pintype "passive"))
      (node (ref "R42") (pin "1") (pinfunction "1_1") (pintype "passive"))
      (node (ref "R44") (pin "1") (pinfunction "1_1") (pintype "passive"))
      (node (ref "R48") (pin "1") (pinfunction "1_1") (pintype "passive"))
      (node (ref "R50") (pin "1") (pinfunction "1_1") (pintype "passive"))
      (node (ref "R54") (pin "1") (pinfunction "1_1") (pintype "passive"))
      (node (ref "R56") (pin "1") (pinfunction "1_1") (pintype "passive"))
      (node (ref "R62") (pin "1") (pinfunction "1_1") (pintype "passive"))
      (node (ref "R66") (pin "1") (pinfunction "1_1") (pintype "passive"))
      (node (ref "R68") (pin "1") (pinfunction "1_1") (pintype "passive"))
      (node (ref "R72") (pin "1") (pinfunction "1_1") (pintype "passive"))
      (node (ref "R74") (pin "1") (pinfunction "1_1") (pintype "passive"))
      (node (ref "R78") (pin "1") (pinfunction "1_1") (pintype "passive"))
      (node (ref "R8") (pin "1") (pinfunction "1_1") (pintype "passive"))
      (node (ref "R86") (pin "1") (pinfunction "1_1") (pintype "passive"))
      (node (ref "R90") (pin "1") (pinfunction "1_1") (pintype "passive"))
      (node (ref "R92") (pin "1") (pinfunction "1_1") (pintype "passive"))
      (node (ref "R96") (pin "1") (pinfunction "1_1") (pintype "passive"))
      (node (ref "SJ10") (pin "3") (pinfunction "3_3") (pintype "passive"))
      (node (ref "SJ13") (pin "1") (pinfunction "1_1") (pintype "passive"))
      (node (ref "SJ14") (pin "3") (pinfunction "3_3") (pintype "passive"))
      (node (ref "SJ15") (pin "1") (pinfunction "1_1") (pintype "passive"))
      (node (ref "SJ16") (pin "3") (pinfunction "3_3") (pintype "passive"))
      (node (ref "SJ17") (pin "1") (pinfunction "1_1") (pintype "passive"))
      (node (ref "SJ18") (pin "3") (pinfunction "3_3") (pintype "passive"))
      (node (ref "SJ2") (pin "1") (pinfunction "1_1") (pintype "passive"))
      (node (ref "SJ21") (pin "1") (pinfunction "1_1") (pintype "passive"))
      (node (ref "SJ22") (pin "3") (pinfunction "3_3") (pintype "passive"))
      (node (ref "SJ23") (pin "1") (pinfunction "1_1") (pintype "passive"))
      (node (ref "SJ24") (pin "3") (pinfunction "3_3") (pintype "passive"))
      (node (ref "SJ25") (pin "1") (pinfunction "1_1") (pintype "passive"))
      (node (ref "SJ26") (pin "3") (pinfunction "3_3") (pintype "passive"))
      (node (ref "SJ29") (pin "1") (pinfunction "1_1") (pintype "passive"))
      (node (ref "SJ3") (pin "3") (pinfunction "3_3") (pintype "passive"))
      (node (ref "SJ30") (pin "3") (pinfunction "3_3") (pintype "passive"))
      (node (ref "SJ31") (pin "1") (pinfunction "1_1") (pintype "passive"))
      (node (ref "SJ32") (pin "3") (pinfunction "3_3") (pintype "passive"))
      (node (ref "SJ35") (pin "1") (pinfunction "1_1") (pintype "passive"))
      (node (ref "SJ36") (pin "3") (pinfunction "3_3") (pintype "passive"))
      (node (ref "SJ39") (pin "1") (pinfunction "1_1") (pintype "passive"))
      (node (ref "SJ40") (pin "3") (pinfunction "3_3") (pintype "passive"))
      (node (ref "SJ43") (pin "1") (pinfunction "1_1") (pintype "passive"))
      (node (ref "SJ44") (pin "3") (pinfunction "3_3") (pintype "passive"))
      (node (ref "SJ47") (pin "1") (pinfunction "1_1") (pintype "passive"))
      (node (ref "SJ48") (pin "3") (pinfunction "3_3") (pintype "passive"))
      (node (ref "SJ5") (pin "1") (pinfunction "1_1") (pintype "passive"))
      (node (ref "SJ6") (pin "3") (pinfunction "3_3") (pintype "passive"))
      (node (ref "SJ7") (pin "1") (pinfunction "1_1") (pintype "passive"))
      (node (ref "SJ8") (pin "3") (pinfunction "3_3") (pintype "passive"))
      (node (ref "SJ9") (pin "1") (pinfunction "1_1") (pintype "passive"))
      (node (ref "U$1") (pin "1") (pinfunction "GND_1") (pintype "bidirectional"))
      (node (ref "U$10") (pin "1") (pinfunction "GND_1") (pintype "bidirectional"))
      (node (ref "U$17") (pin "1") (pinfunction "GND_1") (pintype "bidirectional"))
      (node (ref "U$21") (pin "1") (pinfunction "GND_1") (pintype "bidirectional"))
      (node (ref "U1") (pin "2") (pinfunction "GND_2") (pintype "power_in"))
      (node (ref "U10") (pin "2") (pinfunction "GND_2") (pintype "power_in"))
      (node (ref "U13") (pin "A2") (pinfunction "SGND_A2") (pintype "bidirectional"))
      (node (ref "U13") (pin "D3") (pinfunction "PGND_D3") (pintype "bidirectional"))
      (node (ref "U14") (pin "2") (pinfunction "GND_2") (pintype "power_in"))
      (node (ref "U15") (pin "A2") (pinfunction "SGND_A2") (pintype "bidirectional"))
      (node (ref "U15") (pin "D3") (pinfunction "PGND_D3") (pintype "bidirectional"))
      (node (ref "U16") (pin "2") (pinfunction "GND_2") (pintype "power_in"))
      (node (ref "U17") (pin "A2") (pinfunction "SGND_A2") (pintype "bidirectional"))
      (node (ref "U17") (pin "D3") (pinfunction "PGND_D3") (pintype "bidirectional"))
      (node (ref "U18") (pin "2") (pinfunction "GND_2") (pintype "power_in"))
      (node (ref "U2") (pin "A2") (pinfunction "SGND_A2") (pintype "bidirectional"))
      (node (ref "U2") (pin "D3") (pinfunction "PGND_D3") (pintype "bidirectional"))
      (node (ref "U21") (pin "A2") (pinfunction "SGND_A2") (pintype "bidirectional"))
      (node (ref "U21") (pin "D3") (pinfunction "PGND_D3") (pintype "bidirectional"))
      (node (ref "U22") (pin "2") (pinfunction "GND_2") (pintype "power_in"))
      (node (ref "U23") (pin "A2") (pinfunction "SGND_A2") (pintype "bidirectional"))
      (node (ref "U23") (pin "D3") (pinfunction "PGND_D3") (pintype "bidirectional"))
      (node (ref "U24") (pin "2") (pinfunction "GND_2") (pintype "power_in"))
      (node (ref "U25") (pin "A2") (pinfunction "SGND_A2") (pintype "bidirectional"))
      (node (ref "U25") (pin "D3") (pinfunction "PGND_D3") (pintype "bidirectional"))
      (node (ref "U26") (pin "2") (pinfunction "GND_2") (pintype "power_in"))
      (node (ref "U29") (pin "A2") (pinfunction "SGND_A2") (pintype "bidirectional"))
      (node (ref "U29") (pin "D3") (pinfunction "PGND_D3") (pintype "bidirectional"))
      (node (ref "U30") (pin "2") (pinfunction "GND_2") (pintype "power_in"))
      (node (ref "U31") (pin "A2") (pinfunction "SGND_A2") (pintype "bidirectional"))
      (node (ref "U31") (pin "D3") (pinfunction "PGND_D3") (pintype "bidirectional"))
      (node (ref "U32") (pin "2") (pinfunction "GND_2") (pintype "power_in"))
      (node (ref "U35") (pin "A2") (pinfunction "SGND_A2") (pintype "bidirectional"))
      (node (ref "U35") (pin "D3") (pinfunction "PGND_D3") (pintype "bidirectional"))
      (node (ref "U36") (pin "2") (pinfunction "GND_2") (pintype "power_in"))
      (node (ref "U39") (pin "A2") (pinfunction "SGND_A2") (pintype "bidirectional"))
      (node (ref "U39") (pin "D3") (pinfunction "PGND_D3") (pintype "bidirectional"))
      (node (ref "U40") (pin "2") (pinfunction "GND_2") (pintype "power_in"))
      (node (ref "U43") (pin "A2") (pinfunction "SGND_A2") (pintype "bidirectional"))
      (node (ref "U43") (pin "D3") (pinfunction "PGND_D3") (pintype "bidirectional"))
      (node (ref "U44") (pin "2") (pinfunction "GND_2") (pintype "power_in"))
      (node (ref "U47") (pin "A2") (pinfunction "SGND_A2") (pintype "bidirectional"))
      (node (ref "U47") (pin "D3") (pinfunction "PGND_D3") (pintype "bidirectional"))
      (node (ref "U48") (pin "2") (pinfunction "GND_2") (pintype "power_in"))
      (node (ref "U5") (pin "A2") (pinfunction "SGND_A2") (pintype "bidirectional"))
      (node (ref "U5") (pin "D3") (pinfunction "PGND_D3") (pintype "bidirectional"))
      (node (ref "U6") (pin "2") (pinfunction "GND_2") (pintype "power_in"))
      (node (ref "U7") (pin "A2") (pinfunction "SGND_A2") (pintype "bidirectional"))
      (node (ref "U7") (pin "D3") (pinfunction "PGND_D3") (pintype "bidirectional"))
      (node (ref "U8") (pin "2") (pinfunction "GND_2") (pintype "power_in"))
      (node (ref "U9") (pin "A2") (pinfunction "SGND_A2") (pintype "bidirectional"))
      (node (ref "U9") (pin "D3") (pinfunction "PGND_D3") (pintype "bidirectional"))
    )
    (net (code "87") (name "Net-(C7-Pad2)") (class "Default")
      (node (ref "C7") (pin "2") (pinfunction "2_2") (pintype "passive"))
      (node (ref "R1") (pin "1") (pinfunction "1_1") (pintype "passive"))
      (node (ref "R5") (pin "1") (pinfunction "1_1") (pintype "passive"))
    )
    (net (code "88") (name "Net-(C8-Pad2)") (class "Default")
      (node (ref "C8") (pin "2") (pinfunction "2_2") (pintype "passive"))
      (node (ref "R2") (pin "2") (pinfunction "2_2") (pintype "passive"))
      (node (ref "R6") (pin "1") (pinfunction "1_1") (pintype "passive"))
    )
    (net (code "89") (name "Net-(C23-Pad2)") (class "Default")
      (node (ref "C23") (pin "2") (pinfunction "2_2") (pintype "passive"))
      (node (ref "R13") (pin "1") (pinfunction "1_1") (pintype "passive"))
      (node (ref "R15") (pin "1") (pinfunction "1_1") (pintype "passive"))
    )
    (net (code "90") (name "Net-(C24-Pad2)") (class "Default")
      (node (ref "C24") (pin "2") (pinfunction "2_2") (pintype "passive"))
      (node (ref "R14") (pin "2") (pinfunction "2_2") (pintype "passive"))
      (node (ref "R16") (pin "1") (pinfunction "1_1") (pintype "passive"))
    )
    (net (code "91") (name "Net-(C32-Pad2)") (class "Default")
      (node (ref "C32") (pin "2") (pinfunction "2_2") (pintype "passive"))
      (node (ref "R19") (pin "1") (pinfunction "1_1") (pintype "passive"))
      (node (ref "R21") (pin "1") (pinfunction "1_1") (pintype "passive"))
    )
    (net (code "92") (name "Net-(C33-Pad2)") (class "Default")
      (node (ref "C33") (pin "2") (pinfunction "2_2") (pintype "passive"))
      (node (ref "R20") (pin "2") (pinfunction "2_2") (pintype "passive"))
      (node (ref "R22") (pin "1") (pinfunction "1_1") (pintype "passive"))
    )
    (net (code "93") (name "Net-(C41-Pad2)") (class "Default")
      (node (ref "C41") (pin "2") (pinfunction "2_2") (pintype "passive"))
      (node (ref "R25") (pin "1") (pinfunction "1_1") (pintype "passive"))
      (node (ref "R27") (pin "1") (pinfunction "1_1") (pintype "passive"))
    )
    (net (code "94") (name "Net-(C42-Pad2)") (class "Default")
      (node (ref "C42") (pin "2") (pinfunction "2_2") (pintype "passive"))
      (node (ref "R26") (pin "2") (pinfunction "2_2") (pintype "passive"))
      (node (ref "R28") (pin "1") (pinfunction "1_1") (pintype "passive"))
    )
    (net (code "95") (name "Net-(C59-Pad2)") (class "Default")
      (node (ref "C59") (pin "2") (pinfunction "2_2") (pintype "passive"))
      (node (ref "R37") (pin "1") (pinfunction "1_1") (pintype "passive"))
      (node (ref "R39") (pin "1") (pinfunction "1_1") (pintype "passive"))
    )
    (net (code "96") (name "Net-(C60-Pad2)") (class "Default")
      (node (ref "C60") (pin "2") (pinfunction "2_2") (pintype "passive"))
      (node (ref "R38") (pin "2") (pinfunction "2_2") (pintype "passive"))
      (node (ref "R40") (pin "1") (pinfunction "1_1") (pintype "passive"))
    )
    (net (code "97") (name "Net-(C68-Pad2)") (class "Default")
      (node (ref "C68") (pin "2") (pinfunction "2_2") (pintype "passive"))
      (node (ref "R43") (pin "1") (pinfunction "1_1") (pintype "passive"))
      (node (ref "R45") (pin "1") (pinfunction "1_1") (pintype "passive"))
    )
    (net (code "98") (name "Net-(C69-Pad2)") (class "Default")
      (node (ref "C69") (pin "2") (pinfunction "2_2") (pintype "passive"))
      (node (ref "R44") (pin "2") (pinfunction "2_2") (pintype "passive"))
      (node (ref "R46") (pin "1") (pinfunction "1_1") (pintype "passive"))
    )
    (net (code "99") (name "Net-(C77-Pad2)") (class "Default")
      (node (ref "C77") (pin "2") (pinfunction "2_2") (pintype "passive"))
      (node (ref "R49") (pin "1") (pinfunction "1_1") (pintype "passive"))
      (node (ref "R51") (pin "1") (pinfunction "1_1") (pintype "passive"))
    )
    (net (code "100") (name "Net-(C78-Pad2)") (class "Default")
      (node (ref "C78") (pin "2") (pinfunction "2_2") (pintype "passive"))
      (node (ref "R50") (pin "2") (pinfunction "2_2") (pintype "passive"))
      (node (ref "R52") (pin "1") (pinfunction "1_1") (pintype "passive"))
    )
    (net (code "101") (name "Net-(C95-Pad2)") (class "Default")
      (node (ref "C95") (pin "2") (pinfunction "2_2") (pintype "passive"))
      (node (ref "R61") (pin "1") (pinfunction "1_1") (pintype "passive"))
      (node (ref "R63") (pin "1") (pinfunction "1_1") (pintype "passive"))
    )
    (net (code "102") (name "Net-(C96-Pad2)") (class "Default")
      (node (ref "C96") (pin "2") (pinfunction "2_2") (pintype "passive"))
      (node (ref "R62") (pin "2") (pinfunction "2_2") (pintype "passive"))
      (node (ref "R64") (pin "1") (pinfunction "1_1") (pintype "passive"))
    )
    (net (code "103") (name "Net-(C104-Pad2)") (class "Default")
      (node (ref "C104") (pin "2") (pinfunction "2_2") (pintype "passive"))
      (node (ref "R67") (pin "1") (pinfunction "1_1") (pintype "passive"))
      (node (ref "R69") (pin "1") (pinfunction "1_1") (pintype "passive"))
    )
    (net (code "104") (name "Net-(C105-Pad2)") (class "Default")
      (node (ref "C105") (pin "2") (pinfunction "2_2") (pintype "passive"))
      (node (ref "R68") (pin "2") (pinfunction "2_2") (pintype "passive"))
      (node (ref "R70") (pin "1") (pinfunction "1_1") (pintype "passive"))
    )
    (net (code "105") (name "Net-(C113-Pad2)") (class "Default")
      (node (ref "C113") (pin "2") (pinfunction "2_2") (pintype "passive"))
      (node (ref "R73") (pin "1") (pinfunction "1_1") (pintype "passive"))
      (node (ref "R75") (pin "1") (pinfunction "1_1") (pintype "passive"))
    )
    (net (code "106") (name "Net-(C114-Pad2)") (class "Default")
      (node (ref "C114") (pin "2") (pinfunction "2_2") (pintype "passive"))
      (node (ref "R74") (pin "2") (pinfunction "2_2") (pintype "passive"))
      (node (ref "R76") (pin "1") (pinfunction "1_1") (pintype "passive"))
    )
    (net (code "107") (name "Net-(C131-Pad2)") (class "Default")
      (node (ref "C131") (pin "2") (pinfunction "2_2") (pintype "passive"))
      (node (ref "R85") (pin "1") (pinfunction "1_1") (pintype "passive"))
      (node (ref "R87") (pin "1") (pinfunction "1_1") (pintype "passive"))
    )
    (net (code "108") (name "Net-(C132-Pad2)") (class "Default")
      (node (ref "C132") (pin "2") (pinfunction "2_2") (pintype "passive"))
      (node (ref "R86") (pin "2") (pinfunction "2_2") (pintype "passive"))
      (node (ref "R88") (pin "1") (pinfunction "1_1") (pintype "passive"))
    )
    (net (code "109") (name "Net-(C140-Pad2)") (class "Default")
      (node (ref "C140") (pin "2") (pinfunction "2_2") (pintype "passive"))
      (node (ref "R91") (pin "1") (pinfunction "1_1") (pintype "passive"))
      (node (ref "R93") (pin "1") (pinfunction "1_1") (pintype "passive"))
    )
    (net (code "110") (name "Net-(C141-Pad2)") (class "Default")
      (node (ref "C141") (pin "2") (pinfunction "2_2") (pintype "passive"))
      (node (ref "R92") (pin "2") (pinfunction "2_2") (pintype "passive"))
      (node (ref "R94") (pin "1") (pinfunction "1_1") (pintype "passive"))
    )
    (net (code "111") (name "Net-(C158-Pad2)") (class "Default")
      (node (ref "C158") (pin "2") (pinfunction "2_2") (pintype "passive"))
      (node (ref "R103") (pin "1") (pinfunction "1_1") (pintype "passive"))
      (node (ref "R105") (pin "1") (pinfunction "1_1") (pintype "passive"))
    )
    (net (code "112") (name "Net-(C159-Pad2)") (class "Default")
      (node (ref "C159") (pin "2") (pinfunction "2_2") (pintype "passive"))
      (node (ref "R104") (pin "2") (pinfunction "2_2") (pintype "passive"))
      (node (ref "R106") (pin "1") (pinfunction "1_1") (pintype "passive"))
    )
    (net (code "113") (name "Net-(C176-Pad2)") (class "Default")
      (node (ref "C176") (pin "2") (pinfunction "2_2") (pintype "passive"))
      (node (ref "R115") (pin "1") (pinfunction "1_1") (pintype "passive"))
      (node (ref "R117") (pin "1") (pinfunction "1_1") (pintype "passive"))
    )
    (net (code "114") (name "Net-(C177-Pad2)") (class "Default")
      (node (ref "C177") (pin "2") (pinfunction "2_2") (pintype "passive"))
      (node (ref "R116") (pin "2") (pinfunction "2_2") (pintype "passive"))
      (node (ref "R118") (pin "1") (pinfunction "1_1") (pintype "passive"))
    )
    (net (code "115") (name "Net-(C194-Pad2)") (class "Default")
      (node (ref "C194") (pin "2") (pinfunction "2_2") (pintype "passive"))
      (node (ref "R127") (pin "1") (pinfunction "1_1") (pintype "passive"))
      (node (ref "R129") (pin "1") (pinfunction "1_1") (pintype "passive"))
    )
    (net (code "116") (name "Net-(C195-Pad2)") (class "Default")
      (node (ref "C195") (pin "2") (pinfunction "2_2") (pintype "passive"))
      (node (ref "R128") (pin "2") (pinfunction "2_2") (pintype "passive"))
      (node (ref "R130") (pin "1") (pinfunction "1_1") (pintype "passive"))
    )
    (net (code "117") (name "Net-(C212-Pad2)") (class "Default")
      (node (ref "C212") (pin "2") (pinfunction "2_2") (pintype "passive"))
      (node (ref "R139") (pin "1") (pinfunction "1_1") (pintype "passive"))
      (node (ref "R141") (pin "1") (pinfunction "1_1") (pintype "passive"))
    )
    (net (code "118") (name "Net-(C213-Pad2)") (class "Default")
      (node (ref "C213") (pin "2") (pinfunction "2_2") (pintype "passive"))
      (node (ref "R140") (pin "2") (pinfunction "2_2") (pintype "passive"))
      (node (ref "R142") (pin "1") (pinfunction "1_1") (pintype "passive"))
    )
    (net (code "119") (name "Net-(U$1-SW)") (class "Default")
      (node (ref "C15") (pin "2") (pinfunction "2_2") (pintype "passive"))
      (node (ref "L2") (pin "1") (pinfunction "1_1") (pintype "passive"))
      (node (ref "U$1") (pin "2") (pinfunction "SW_2") (pintype "bidirectional"))
    )
    (net (code "120") (name "Net-(U$1-VBST)") (class "Default")
      (node (ref "C15") (pin "1") (pinfunction "1_1") (pintype "passive"))
      (node (ref "U$1") (pin "6") (pinfunction "VBST_6") (pintype "bidirectional"))
    )
    (net (code "121") (name "Net-(U$1-VFB)") (class "Default")
      (node (ref "R3") (pin "1") (pinfunction "1_1") (pintype "passive"))
      (node (ref "R4") (pin "2") (pinfunction "2_2") (pintype "passive"))
      (node (ref "U$1") (pin "4") (pinfunction "VFB_4") (pintype "bidirectional"))
    )
    (net (code "122") (name "Net-(U$2-A)") (class "Default")
      (node (ref "L1") (pin "2") (pinfunction "2_2") (pintype "passive"))
      (node (ref "U$2") (pin "2") (pinfunction "A_2") (pintype "passive"))
      (node (ref "U2") (pin "D2") (pinfunction "SW_D2") (pintype "bidirectional"))
    )
    (net (code "123") (name "Net-(U$2-C)") (class "Default")
      (node (ref "C9") (pin "2") (pinfunction "2_2") (pintype "passive"))
      (node (ref "U$2") (pin "1") (pinfunction "C_1") (pintype "passive"))
      (node (ref "U2") (pin "C1") (pinfunction "VAMP_C1") (pintype "bidirectional"))
      (node (ref "U2") (pin "D1") (pinfunction "VBST_D1") (pintype "bidirectional"))
    )
    (net (code "124") (name "Net-(U$3-A)") (class "Default")
      (node (ref "L5") (pin "2") (pinfunction "2_2") (pintype "passive"))
      (node (ref "U$3") (pin "2") (pinfunction "A_2") (pintype "passive"))
      (node (ref "U5") (pin "D2") (pinfunction "SW_D2") (pintype "bidirectional"))
    )
    (net (code "125") (name "Net-(U$3-C)") (class "Default")
      (node (ref "C25") (pin "2") (pinfunction "2_2") (pintype "passive"))
      (node (ref "U$3") (pin "1") (pinfunction "C_1") (pintype "passive"))
      (node (ref "U5") (pin "C1") (pinfunction "VAMP_C1") (pintype "bidirectional"))
      (node (ref "U5") (pin "D1") (pinfunction "VBST_D1") (pintype "bidirectional"))
    )
    (net (code "126") (name "Net-(U$4-A)") (class "Default")
      (node (ref "L7") (pin "2") (pinfunction "2_2") (pintype "passive"))
      (node (ref "U$4") (pin "2") (pinfunction "A_2") (pintype "passive"))
      (node (ref "U7") (pin "D2") (pinfunction "SW_D2") (pintype "bidirectional"))
    )
    (net (code "127") (name "Net-(U$4-C)") (class "Default")
      (node (ref "C34") (pin "2") (pinfunction "2_2") (pintype "passive"))
      (node (ref "U$4") (pin "1") (pinfunction "C_1") (pintype "passive"))
      (node (ref "U7") (pin "C1") (pinfunction "VAMP_C1") (pintype "bidirectional"))
      (node (ref "U7") (pin "D1") (pinfunction "VBST_D1") (pintype "bidirectional"))
    )
    (net (code "128") (name "Net-(U$5-A)") (class "Default")
      (node (ref "L9") (pin "2") (pinfunction "2_2") (pintype "passive"))
      (node (ref "U$5") (pin "2") (pinfunction "A_2") (pintype "passive"))
      (node (ref "U9") (pin "D2") (pinfunction "SW_D2") (pintype "bidirectional"))
    )
    (net (code "129") (name "Net-(U$5-C)") (class "Default")
      (node (ref "C43") (pin "2") (pinfunction "2_2") (pintype "passive"))
      (node (ref "U$5") (pin "1") (pinfunction "C_1") (pintype "passive"))
      (node (ref "U9") (pin "C1") (pinfunction "VAMP_C1") (pintype "bidirectional"))
      (node (ref "U9") (pin "D1") (pinfunction "VBST_D1") (pintype "bidirectional"))
    )
    (net (code "130") (name "Net-(U$7-A)") (class "Default")
      (node (ref "L13") (pin "2") (pinfunction "2_2") (pintype "passive"))
      (node (ref "U$7") (pin "2") (pinfunction "A_2") (pintype "passive"))
      (node (ref "U13") (pin "D2") (pinfunction "SW_D2") (pintype "bidirectional"))
    )
    (net (code "131") (name "Net-(U$7-C)") (class "Default")
      (node (ref "C61") (pin "2") (pinfunction "2_2") (pintype "passive"))
      (node (ref "U$7") (pin "1") (pinfunction "C_1") (pintype "passive"))
      (node (ref "U13") (pin "C1") (pinfunction "VAMP_C1") (pintype "bidirectional"))
      (node (ref "U13") (pin "D1") (pinfunction "VBST_D1") (pintype "bidirectional"))
    )
    (net (code "132") (name "Net-(U$8-A)") (class "Default")
      (node (ref "L15") (pin "2") (pinfunction "2_2") (pintype "passive"))
      (node (ref "U$8") (pin "2") (pinfunction "A_2") (pintype "passive"))
      (node (ref "U15") (pin "D2") (pinfunction "SW_D2") (pintype "bidirectional"))
    )
    (net (code "133") (name "Net-(U$8-C)") (class "Default")
      (node (ref "C70") (pin "2") (pinfunction "2_2") (pintype "passive"))
      (node (ref "U$8") (pin "1") (pinfunction "C_1") (pintype "passive"))
      (node (ref "U15") (pin "C1") (pinfunction "VAMP_C1") (pintype "bidirectional"))
      (node (ref "U15") (pin "D1") (pinfunction "VBST_D1") (pintype "bidirectional"))
    )
    (net (code "134") (name "Net-(U$9-A)") (class "Default")
      (node (ref "L17") (pin "2") (pinfunction "2_2") (pintype "passive"))
      (node (ref "U$9") (pin "2") (pinfunction "A_2") (pintype "passive"))
      (node (ref "U17") (pin "D2") (pinfunction "SW_D2") (pintype "bidirectional"))
    )
    (net (code "135") (name "Net-(U$9-C)") (class "Default")
      (node (ref "C79") (pin "2") (pinfunction "2_2") (pintype "passive"))
      (node (ref "U$9") (pin "1") (pinfunction "C_1") (pintype "passive"))
      (node (ref "U17") (pin "C1") (pinfunction "VAMP_C1") (pintype "bidirectional"))
      (node (ref "U17") (pin "D1") (pinfunction "VBST_D1") (pintype "bidirectional"))
    )
    (net (code "136") (name "Net-(U$10-SW)") (class "Default")
      (node (ref "C49") (pin "2") (pinfunction "2_2") (pintype "passive"))
      (node (ref "L11") (pin "1") (pinfunction "1_1") (pintype "passive"))
      (node (ref "U$10") (pin "2") (pinfunction "SW_2") (pintype "bidirectional"))
    )
    (net (code "137") (name "Net-(U$10-VBST)") (class "Default")
      (node (ref "C49") (pin "1") (pinfunction "1_1") (pintype "passive"))
      (node (ref "U$10") (pin "6") (pinfunction "VBST_6") (pintype "bidirectional"))
    )
    (net (code "138") (name "Net-(U$10-VFB)") (class "Default")
      (node (ref "R11") (pin "1") (pinfunction "1_1") (pintype "passive"))
      (node (ref "R12") (pin "2") (pinfunction "2_2") (pintype "passive"))
      (node (ref "U$10") (pin "4") (pinfunction "VFB_4") (pintype "bidirectional"))
    )
    (net (code "139") (name "Net-(U$11-A)") (class "Default")
      (node (ref "L21") (pin "2") (pinfunction "2_2") (pintype "passive"))
      (node (ref "U$11") (pin "2") (pinfunction "A_2") (pintype "passive"))
      (node (ref "U21") (pin "D2") (pinfunction "SW_D2") (pintype "bidirectional"))
    )
    (net (code "140") (name "Net-(U$11-C)") (class "Default")
      (node (ref "C97") (pin "2") (pinfunction "2_2") (pintype "passive"))
      (node (ref "U$11") (pin "1") (pinfunction "C_1") (pintype "passive"))
      (node (ref "U21") (pin "C1") (pinfunction "VAMP_C1") (pintype "bidirectional"))
      (node (ref "U21") (pin "D1") (pinfunction "VBST_D1") (pintype "bidirectional"))
    )
    (net (code "141") (name "Net-(U$12-A)") (class "Default")
      (node (ref "L23") (pin "2") (pinfunction "2_2") (pintype "passive"))
      (node (ref "U$12") (pin "2") (pinfunction "A_2") (pintype "passive"))
      (node (ref "U23") (pin "D2") (pinfunction "SW_D2") (pintype "bidirectional"))
    )
    (net (code "142") (name "Net-(U$12-C)") (class "Default")
      (node (ref "C106") (pin "2") (pinfunction "2_2") (pintype "passive"))
      (node (ref "U$12") (pin "1") (pinfunction "C_1") (pintype "passive"))
      (node (ref "U23") (pin "C1") (pinfunction "VAMP_C1") (pintype "bidirectional"))
      (node (ref "U23") (pin "D1") (pinfunction "VBST_D1") (pintype "bidirectional"))
    )
    (net (code "143") (name "Net-(U$13-A)") (class "Default")
      (node (ref "L25") (pin "2") (pinfunction "2_2") (pintype "passive"))
      (node (ref "U$13") (pin "2") (pinfunction "A_2") (pintype "passive"))
      (node (ref "U25") (pin "D2") (pinfunction "SW_D2") (pintype "bidirectional"))
    )
    (net (code "144") (name "Net-(U$13-C)") (class "Default")
      (node (ref "C115") (pin "2") (pinfunction "2_2") (pintype "passive"))
      (node (ref "U$13") (pin "1") (pinfunction "C_1") (pintype "passive"))
      (node (ref "U25") (pin "C1") (pinfunction "VAMP_C1") (pintype "bidirectional"))
      (node (ref "U25") (pin "D1") (pinfunction "VBST_D1") (pintype "bidirectional"))
    )
    (net (code "145") (name "Net-(U$15-A)") (class "Default")
      (node (ref "L29") (pin "2") (pinfunction "2_2") (pintype "passive"))
      (node (ref "U$15") (pin "2") (pinfunction "A_2") (pintype "passive"))
      (node (ref "U29") (pin "D2") (pinfunction "SW_D2") (pintype "bidirectional"))
    )
    (net (code "146") (name "Net-(U$15-C)") (class "Default")
      (node (ref "C133") (pin "2") (pinfunction "2_2") (pintype "passive"))
      (node (ref "U$15") (pin "1") (pinfunction "C_1") (pintype "passive"))
      (node (ref "U29") (pin "C1") (pinfunction "VAMP_C1") (pintype "bidirectional"))
      (node (ref "U29") (pin "D1") (pinfunction "VBST_D1") (pintype "bidirectional"))
    )
    (net (code "147") (name "Net-(U$16-A)") (class "Default")
      (node (ref "L31") (pin "2") (pinfunction "2_2") (pintype "passive"))
      (node (ref "U$16") (pin "2") (pinfunction "A_2") (pintype "passive"))
      (node (ref "U31") (pin "D2") (pinfunction "SW_D2") (pintype "bidirectional"))
    )
    (net (code "148") (name "Net-(U$16-C)") (class "Default")
      (node (ref "C142") (pin "2") (pinfunction "2_2") (pintype "passive"))
      (node (ref "U$16") (pin "1") (pinfunction "C_1") (pintype "passive"))
      (node (ref "U31") (pin "C1") (pinfunction "VAMP_C1") (pintype "bidirectional"))
      (node (ref "U31") (pin "D1") (pinfunction "VBST_D1") (pintype "bidirectional"))
    )
    (net (code "149") (name "Net-(U$17-SW)") (class "Default")
      (node (ref "C86") (pin "2") (pinfunction "2_2") (pintype "passive"))
      (node (ref "L19") (pin "1") (pinfunction "1_1") (pintype "passive"))
      (node (ref "U$17") (pin "2") (pinfunction "SW_2") (pintype "bidirectional"))
    )
    (net (code "150") (name "Net-(U$17-VBST)") (class "Default")
      (node (ref "C86") (pin "1") (pinfunction "1_1") (pintype "passive"))
      (node (ref "U$17") (pin "6") (pinfunction "VBST_6") (pintype "bidirectional"))
    )
    (net (code "151") (name "Net-(U$17-VFB)") (class "Default")
      (node (ref "R33") (pin "1") (pinfunction "1_1") (pintype "passive"))
      (node (ref "R34") (pin "2") (pinfunction "2_2") (pintype "passive"))
      (node (ref "U$17") (pin "4") (pinfunction "VFB_4") (pintype "bidirectional"))
    )
    (net (code "152") (name "Net-(U$18-A)") (class "Default")
      (node (ref "L35") (pin "2") (pinfunction "2_2") (pintype "passive"))
      (node (ref "U$18") (pin "2") (pinfunction "A_2") (pintype "passive"))
      (node (ref "U35") (pin "D2") (pinfunction "SW_D2") (pintype "bidirectional"))
    )
    (net (code "153") (name "Net-(U$18-C)") (class "Default")
      (node (ref "C160") (pin "2") (pinfunction "2_2") (pintype "passive"))
      (node (ref "U$18") (pin "1") (pinfunction "C_1") (pintype "passive"))
      (node (ref "U35") (pin "C1") (pinfunction "VAMP_C1") (pintype "bidirectional"))
      (node (ref "U35") (pin "D1") (pinfunction "VBST_D1") (pintype "bidirectional"))
    )
    (net (code "154") (name "Net-(U$20-A)") (class "Default")
      (node (ref "L39") (pin "2") (pinfunction "2_2") (pintype "passive"))
      (node (ref "U$20") (pin "2") (pinfunction "A_2") (pintype "passive"))
      (node (ref "U39") (pin "D2") (pinfunction "SW_D2") (pintype "bidirectional"))
    )
    (net (code "155") (name "Net-(U$20-C)") (class "Default")
      (node (ref "C178") (pin "2") (pinfunction "2_2") (pintype "passive"))
      (node (ref "U$20") (pin "1") (pinfunction "C_1") (pintype "passive"))
      (node (ref "U39") (pin "C1") (pinfunction "VAMP_C1") (pintype "bidirectional"))
      (node (ref "U39") (pin "D1") (pinfunction "VBST_D1") (pintype "bidirectional"))
    )
    (net (code "156") (name "Net-(U$21-SW)") (class "Default")
      (node (ref "C123") (pin "2") (pinfunction "2_2") (pintype "passive"))
      (node (ref "L27") (pin "1") (pinfunction "1_1") (pintype "passive"))
      (node (ref "U$21") (pin "2") (pinfunction "SW_2") (pintype "bidirectional"))
    )
    (net (code "157") (name "Net-(U$21-VBST)") (class "Default")
      (node (ref "C123") (pin "1") (pinfunction "1_1") (pintype "passive"))
      (node (ref "U$21") (pin "6") (pinfunction "VBST_6") (pintype "bidirectional"))
    )
    (net (code "158") (name "Net-(U$21-VFB)") (class "Default")
      (node (ref "R55") (pin "1") (pinfunction "1_1") (pintype "passive"))
      (node (ref "R56") (pin "2") (pinfunction "2_2") (pintype "passive"))
      (node (ref "U$21") (pin "4") (pinfunction "VFB_4") (pintype "bidirectional"))
    )
    (net (code "159") (name "Net-(U$22-A)") (class "Default")
      (node (ref "L43") (pin "2") (pinfunction "2_2") (pintype "passive"))
      (node (ref "U$22") (pin "2") (pinfunction "A_2") (pintype "passive"))
      (node (ref "U43") (pin "D2") (pinfunction "SW_D2") (pintype "bidirectional"))
    )
    (net (code "160") (name "Net-(U$22-C)") (class "Default")
      (node (ref "C196") (pin "2") (pinfunction "2_2") (pintype "passive"))
      (node (ref "U$22") (pin "1") (pinfunction "C_1") (pintype "passive"))
      (node (ref "U43") (pin "C1") (pinfunction "VAMP_C1") (pintype "bidirectional"))
      (node (ref "U43") (pin "D1") (pinfunction "VBST_D1") (pintype "bidirectional"))
    )
    (net (code "161") (name "Net-(U$24-A)") (class "Default")
      (node (ref "L47") (pin "2") (pinfunction "2_2") (pintype "passive"))
      (node (ref "U$24") (pin "2") (pinfunction "A_2") (pintype "passive"))
      (node (ref "U47") (pin "D2") (pinfunction "SW_D2") (pintype "bidirectional"))
    )
    (net (code "162") (name "Net-(U$24-C)") (class "Default")
      (node (ref "C214") (pin "2") (pinfunction "2_2") (pintype "passive"))
      (node (ref "U$24") (pin "1") (pinfunction "C_1") (pintype "passive"))
      (node (ref "U47") (pin "C1") (pinfunction "VAMP_C1") (pintype "bidirectional"))
      (node (ref "U47") (pin "D1") (pinfunction "VBST_D1") (pintype "bidirectional"))
    )
    (net (code "163") (name "Net-(U1-FB)") (class "Default")
      (node (ref "R7") (pin "1") (pinfunction "1_1") (pintype "passive"))
      (node (ref "R8") (pin "2") (pinfunction "2_2") (pintype "passive"))
      (node (ref "U1") (pin "3") (pinfunction "FB_3") (pintype "input"))
    )
    (net (code "164") (name "Net-(U1-SW)") (class "Default")
      (node (ref "L3") (pin "2") (pinfunction "2_2") (pintype "passive"))
      (node (ref "U1") (pin "1") (pinfunction "SW_1") (pintype "output"))
    )
    (net (code "165") (name "Net-(U2-GAIN)") (class "Default")
      (node (ref "SJ3") (pin "2") (pinfunction "2_2") (pintype "passive"))
      (node (ref "U2") (pin "B2") (pinfunction "GAIN_B2") (pintype "bidirectional"))
    )
    (net (code "166") (name "Net-(U2-IN+)") (class "Default")
      (node (ref "C1") (pin "2") (pinfunction "2_2") (pintype "passive"))
      (node (ref "U2") (pin "A3") (pinfunction "IN+_A3") (pintype "bidirectional"))
    )
    (net (code "167") (name "Net-(U2-IN-)") (class "Default")
      (node (ref "C2") (pin "2") (pinfunction "2_2") (pintype "passive"))
      (node (ref "U2") (pin "B3") (pinfunction "IN-_B3") (pintype "bidirectional"))
    )
    (net (code "168") (name "Net-(U2-OUT+)") (class "Default")
      (node (ref "C7") (pin "1") (pinfunction "1_1") (pintype "passive"))
      (node (ref "U2") (pin "A1") (pinfunction "OUT+_A1") (pintype "bidirectional"))
    )
    (net (code "169") (name "Net-(U2-OUT-)") (class "Default")
      (node (ref "C8") (pin "1") (pinfunction "1_1") (pintype "passive"))
      (node (ref "U2") (pin "B1") (pinfunction "OUT-_B1") (pintype "bidirectional"))
    )
    (net (code "170") (name "Net-(U5-GAIN)") (class "Default")
      (node (ref "SJ6") (pin "2") (pinfunction "2_2") (pintype "passive"))
      (node (ref "U5") (pin "B2") (pinfunction "GAIN_B2") (pintype "bidirectional"))
    )
    (net (code "171") (name "Net-(U5-IN+)") (class "Default")
      (node (ref "C19") (pin "2") (pinfunction "2_2") (pintype "passive"))
      (node (ref "U5") (pin "A3") (pinfunction "IN+_A3") (pintype "bidirectional"))
    )
    (net (code "172") (name "Net-(U5-IN-)") (class "Default")
      (node (ref "C20") (pin "2") (pinfunction "2_2") (pintype "passive"))
      (node (ref "U5") (pin "B3") (pinfunction "IN-_B3") (pintype "bidirectional"))
    )
    (net (code "173") (name "Net-(U5-OUT+)") (class "Default")
      (node (ref "C23") (pin "1") (pinfunction "1_1") (pintype "passive"))
      (node (ref "U5") (pin "A1") (pinfunction "OUT+_A1") (pintype "bidirectional"))
    )
    (net (code "174") (name "Net-(U5-OUT-)") (class "Default")
      (node (ref "C24") (pin "1") (pinfunction "1_1") (pintype "passive"))
      (node (ref "U5") (pin "B1") (pinfunction "OUT-_B1") (pintype "bidirectional"))
    )
    (net (code "175") (name "Net-(U6-FB)") (class "Default")
      (node (ref "R17") (pin "1") (pinfunction "1_1") (pintype "passive"))
      (node (ref "R18") (pin "2") (pinfunction "2_2") (pintype "passive"))
      (node (ref "U6") (pin "3") (pinfunction "FB_3") (pintype "input"))
    )
    (net (code "176") (name "Net-(U6-SW)") (class "Default")
      (node (ref "L6") (pin "2") (pinfunction "2_2") (pintype "passive"))
      (node (ref "U6") (pin "1") (pinfunction "SW_1") (pintype "output"))
    )
    (net (code "177") (name "Net-(U7-GAIN)") (class "Default")
      (node (ref "SJ8") (pin "2") (pinfunction "2_2") (pintype "passive"))
      (node (ref "U7") (pin "B2") (pinfunction "GAIN_B2") (pintype "bidirectional"))
    )
    (net (code "178") (name "Net-(U7-IN+)") (class "Default")
      (node (ref "C28") (pin "2") (pinfunction "2_2") (pintype "passive"))
      (node (ref "U7") (pin "A3") (pinfunction "IN+_A3") (pintype "bidirectional"))
    )
    (net (code "179") (name "Net-(U7-IN-)") (class "Default")
      (node (ref "C29") (pin "2") (pinfunction "2_2") (pintype "passive"))
      (node (ref "U7") (pin "B3") (pinfunction "IN-_B3") (pintype "bidirectional"))
    )
    (net (code "180") (name "Net-(U7-OUT+)") (class "Default")
      (node (ref "C32") (pin "1") (pinfunction "1_1") (pintype "passive"))
      (node (ref "U7") (pin "A1") (pinfunction "OUT+_A1") (pintype "bidirectional"))
    )
    (net (code "181") (name "Net-(U7-OUT-)") (class "Default")
      (node (ref "C33") (pin "1") (pinfunction "1_1") (pintype "passive"))
      (node (ref "U7") (pin "B1") (pinfunction "OUT-_B1") (pintype "bidirectional"))
    )
    (net (code "182") (name "Net-(U8-FB)") (class "Default")
      (node (ref "R23") (pin "1") (pinfunction "1_1") (pintype "passive"))
      (node (ref "R24") (pin "2") (pinfunction "2_2") (pintype "passive"))
      (node (ref "U8") (pin "3") (pinfunction "FB_3") (pintype "input"))
    )
    (net (code "183") (name "Net-(U8-SW)") (class "Default")
      (node (ref "L8") (pin "2") (pinfunction "2_2") (pintype "passive"))
      (node (ref "U8") (pin "1") (pinfunction "SW_1") (pintype "output"))
    )
    (net (code "184") (name "Net-(U9-GAIN)") (class "Default")
      (node (ref "SJ10") (pin "2") (pinfunction "2_2") (pintype "passive"))
      (node (ref "U9") (pin "B2") (pinfunction "GAIN_B2") (pintype "bidirectional"))
    )
    (net (code "185") (name "Net-(U9-IN+)") (class "Default")
      (node (ref "C37") (pin "2") (pinfunction "2_2") (pintype "passive"))
      (node (ref "U9") (pin "A3") (pinfunction "IN+_A3") (pintype "bidirectional"))
    )
    (net (code "186") (name "Net-(U9-IN-)") (class "Default")
      (node (ref "C38") (pin "2") (pinfunction "2_2") (pintype "passive"))
      (node (ref "U9") (pin "B3") (pinfunction "IN-_B3") (pintype "bidirectional"))
    )
    (net (code "187") (name "Net-(U9-OUT+)") (class "Default")
      (node (ref "C41") (pin "1") (pinfunction "1_1") (pintype "passive"))
      (node (ref "U9") (pin "A1") (pinfunction "OUT+_A1") (pintype "bidirectional"))
    )
    (net (code "188") (name "Net-(U9-OUT-)") (class "Default")
      (node (ref "C42") (pin "1") (pinfunction "1_1") (pintype "passive"))
      (node (ref "U9") (pin "B1") (pinfunction "OUT-_B1") (pintype "bidirectional"))
    )
    (net (code "189") (name "Net-(U10-FB)") (class "Default")
      (node (ref "R29") (pin "1") (pinfunction "1_1") (pintype "passive"))
      (node (ref "R30") (pin "2") (pinfunction "2_2") (pintype "passive"))
      (node (ref "U10") (pin "3") (pinfunction "FB_3") (pintype "input"))
    )
    (net (code "190") (name "Net-(U10-SW)") (class "Default")
      (node (ref "L10") (pin "2") (pinfunction "2_2") (pintype "passive"))
      (node (ref "U10") (pin "1") (pinfunction "SW_1") (pintype "output"))
    )
    (net (code "191") (name "Net-(U13-GAIN)") (class "Default")
      (node (ref "SJ14") (pin "2") (pinfunction "2_2") (pintype "passive"))
      (node (ref "U13") (pin "B2") (pinfunction "GAIN_B2") (pintype "bidirectional"))
    )
    (net (code "192") (name "Net-(U13-IN+)") (class "Default")
      (node (ref "C55") (pin "2") (pinfunction "2_2") (pintype "passive"))
      (node (ref "U13") (pin "A3") (pinfunction "IN+_A3") (pintype "bidirectional"))
    )
    (net (code "193") (name "Net-(U13-IN-)") (class "Default")
      (node (ref "C56") (pin "2") (pinfunction "2_2") (pintype "passive"))
      (node (ref "U13") (pin "B3") (pinfunction "IN-_B3") (pintype "bidirectional"))
    )
    (net (code "194") (name "Net-(U13-OUT+)") (class "Default")
      (node (ref "C59") (pin "1") (pinfunction "1_1") (pintype "passive"))
      (node (ref "U13") (pin "A1") (pinfunction "OUT+_A1") (pintype "bidirectional"))
    )
    (net (code "195") (name "Net-(U13-OUT-)") (class "Default")
      (node (ref "C60") (pin "1") (pinfunction "1_1") (pintype "passive"))
      (node (ref "U13") (pin "B1") (pinfunction "OUT-_B1") (pintype "bidirectional"))
    )
    (net (code "196") (name "Net-(U14-FB)") (class "Default")
      (node (ref "R41") (pin "1") (pinfunction "1_1") (pintype "passive"))
      (node (ref "R42") (pin "2") (pinfunction "2_2") (pintype "passive"))
      (node (ref "U14") (pin "3") (pinfunction "FB_3") (pintype "input"))
    )
    (net (code "197") (name "Net-(U14-SW)") (class "Default")
      (node (ref "L14") (pin "2") (pinfunction "2_2") (pintype "passive"))
      (node (ref "U14") (pin "1") (pinfunction "SW_1") (pintype "output"))
    )
    (net (code "198") (name "Net-(U15-GAIN)") (class "Default")
      (node (ref "SJ16") (pin "2") (pinfunction "2_2") (pintype "passive"))
      (node (ref "U15") (pin "B2") (pinfunction "GAIN_B2") (pintype "bidirectional"))
    )
    (net (code "199") (name "Net-(U15-IN+)") (class "Default")
      (node (ref "C64") (pin "2") (pinfunction "2_2") (pintype "passive"))
      (node (ref "U15") (pin "A3") (pinfunction "IN+_A3") (pintype "bidirectional"))
    )
    (net (code "200") (name "Net-(U15-IN-)") (class "Default")
      (node (ref "C65") (pin "2") (pinfunction "2_2") (pintype "passive"))
      (node (ref "U15") (pin "B3") (pinfunction "IN-_B3") (pintype "bidirectional"))
    )
    (net (code "201") (name "Net-(U15-OUT+)") (class "Default")
      (node (ref "C68") (pin "1") (pinfunction "1_1") (pintype "passive"))
      (node (ref "U15") (pin "A1") (pinfunction "OUT+_A1") (pintype "bidirectional"))
    )
    (net (code "202") (name "Net-(U15-OUT-)") (class "Default")
      (node (ref "C69") (pin "1") (pinfunction "1_1") (pintype "passive"))
      (node (ref "U15") (pin "B1") (pinfunction "OUT-_B1") (pintype "bidirectional"))
    )
    (net (code "203") (name "Net-(U16-FB)") (class "Default")
      (node (ref "R47") (pin "1") (pinfunction "1_1") (pintype "passive"))
      (node (ref "R48") (pin "2") (pinfunction "2_2") (pintype "passive"))
      (node (ref "U16") (pin "3") (pinfunction "FB_3") (pintype "input"))
    )
    (net (code "204") (name "Net-(U16-SW)") (class "Default")
      (node (ref "L16") (pin "2") (pinfunction "2_2") (pintype "passive"))
      (node (ref "U16") (pin "1") (pinfunction "SW_1") (pintype "output"))
    )
    (net (code "205") (name "Net-(U17-GAIN)") (class "Default")
      (node (ref "SJ18") (pin "2") (pinfunction "2_2") (pintype "passive"))
      (node (ref "U17") (pin "B2") (pinfunction "GAIN_B2") (pintype "bidirectional"))
    )
    (net (code "206") (name "Net-(U17-IN+)") (class "Default")
      (node (ref "C73") (pin "2") (pinfunction "2_2") (pintype "passive"))
      (node (ref "U17") (pin "A3") (pinfunction "IN+_A3") (pintype "bidirectional"))
    )
    (net (code "207") (name "Net-(U17-IN-)") (class "Default")
      (node (ref "C74") (pin "2") (pinfunction "2_2") (pintype "passive"))
      (node (ref "U17") (pin "B3") (pinfunction "IN-_B3") (pintype "bidirectional"))
    )
    (net (code "208") (name "Net-(U17-OUT+)") (class "Default")
      (node (ref "C77") (pin "1") (pinfunction "1_1") (pintype "passive"))
      (node (ref "U17") (pin "A1") (pinfunction "OUT+_A1") (pintype "bidirectional"))
    )
    (net (code "209") (name "Net-(U17-OUT-)") (class "Default")
      (node (ref "C78") (pin "1") (pinfunction "1_1") (pintype "passive"))
      (node (ref "U17") (pin "B1") (pinfunction "OUT-_B1") (pintype "bidirectional"))
    )
    (net (code "210") (name "Net-(U18-FB)") (class "Default")
      (node (ref "R53") (pin "1") (pinfunction "1_1") (pintype "passive"))
      (node (ref "R54") (pin "2") (pinfunction "2_2") (pintype "passive"))
      (node (ref "U18") (pin "3") (pinfunction "FB_3") (pintype "input"))
    )
    (net (code "211") (name "Net-(U18-SW)") (class "Default")
      (node (ref "L18") (pin "2") (pinfunction "2_2") (pintype "passive"))
      (node (ref "U18") (pin "1") (pinfunction "SW_1") (pintype "output"))
    )
    (net (code "212") (name "Net-(U21-GAIN)") (class "Default")
      (node (ref "SJ22") (pin "2") (pinfunction "2_2") (pintype "passive"))
      (node (ref "U21") (pin "B2") (pinfunction "GAIN_B2") (pintype "bidirectional"))
    )
    (net (code "213") (name "Net-(U21-IN+)") (class "Default")
      (node (ref "C91") (pin "2") (pinfunction "2_2") (pintype "passive"))
      (node (ref "U21") (pin "A3") (pinfunction "IN+_A3") (pintype "bidirectional"))
    )
    (net (code "214") (name "Net-(U21-IN-)") (class "Default")
      (node (ref "C92") (pin "2") (pinfunction "2_2") (pintype "passive"))
      (node (ref "U21") (pin "B3") (pinfunction "IN-_B3") (pintype "bidirectional"))
    )
    (net (code "215") (name "Net-(U21-OUT+)") (class "Default")
      (node (ref "C95") (pin "1") (pinfunction "1_1") (pintype "passive"))
      (node (ref "U21") (pin "A1") (pinfunction "OUT+_A1") (pintype "bidirectional"))
    )
    (net (code "216") (name "Net-(U21-OUT-)") (class "Default")
      (node (ref "C96") (pin "1") (pinfunction "1_1") (pintype "passive"))
      (node (ref "U21") (pin "B1") (pinfunction "OUT-_B1") (pintype "bidirectional"))
    )
    (net (code "217") (name "Net-(U22-FB)") (class "Default")
      (node (ref "R65") (pin "1") (pinfunction "1_1") (pintype "passive"))
      (node (ref "R66") (pin "2") (pinfunction "2_2") (pintype "passive"))
      (node (ref "U22") (pin "3") (pinfunction "FB_3") (pintype "input"))
    )
    (net (code "218") (name "Net-(U22-SW)") (class "Default")
      (node (ref "L22") (pin "2") (pinfunction "2_2") (pintype "passive"))
      (node (ref "U22") (pin "1") (pinfunction "SW_1") (pintype "output"))
    )
    (net (code "219") (name "Net-(U23-GAIN)") (class "Default")
      (node (ref "SJ24") (pin "2") (pinfunction "2_2") (pintype "passive"))
      (node (ref "U23") (pin "B2") (pinfunction "GAIN_B2") (pintype "bidirectional"))
    )
    (net (code "220") (name "Net-(U23-IN+)") (class "Default")
      (node (ref "C100") (pin "2") (pinfunction "2_2") (pintype "passive"))
      (node (ref "U23") (pin "A3") (pinfunction "IN+_A3") (pintype "bidirectional"))
    )
    (net (code "221") (name "Net-(U23-IN-)") (class "Default")
      (node (ref "C101") (pin "2") (pinfunction "2_2") (pintype "passive"))
      (node (ref "U23") (pin "B3") (pinfunction "IN-_B3") (pintype "bidirectional"))
    )
    (net (code "222") (name "Net-(U23-OUT+)") (class "Default")
      (node (ref "C104") (pin "1") (pinfunction "1_1") (pintype "passive"))
      (node (ref "U23") (pin "A1") (pinfunction "OUT+_A1") (pintype "bidirectional"))
    )
    (net (code "223") (name "Net-(U23-OUT-)") (class "Default")
      (node (ref "C105") (pin "1") (pinfunction "1_1") (pintype "passive"))
      (node (ref "U23") (pin "B1") (pinfunction "OUT-_B1") (pintype "bidirectional"))
    )
    (net (code "224") (name "Net-(U24-FB)") (class "Default")
      (node (ref "R71") (pin "1") (pinfunction "1_1") (pintype "passive"))
      (node (ref "R72") (pin "2") (pinfunction "2_2") (pintype "passive"))
      (node (ref "U24") (pin "3") (pinfunction "FB_3") (pintype "input"))
    )
    (net (code "225") (name "Net-(U24-SW)") (class "Default")
      (node (ref "L24") (pin "2") (pinfunction "2_2") (pintype "passive"))
      (node (ref "U24") (pin "1") (pinfunction "SW_1") (pintype "output"))
    )
    (net (code "226") (name "Net-(U25-GAIN)") (class "Default")
      (node (ref "SJ26") (pin "2") (pinfunction "2_2") (pintype "passive"))
      (node (ref "U25") (pin "B2") (pinfunction "GAIN_B2") (pintype "bidirectional"))
    )
    (net (code "227") (name "Net-(U25-IN+)") (class "Default")
      (node (ref "C109") (pin "2") (pinfunction "2_2") (pintype "passive"))
      (node (ref "U25") (pin "A3") (pinfunction "IN+_A3") (pintype "bidirectional"))
    )
    (net (code "228") (name "Net-(U25-IN-)") (class "Default")
      (node (ref "C110") (pin "2") (pinfunction "2_2") (pintype "passive"))
      (node (ref "U25") (pin "B3") (pinfunction "IN-_B3") (pintype "bidirectional"))
    )
    (net (code "229") (name "Net-(U25-OUT+)") (class "Default")
      (node (ref "C113") (pin "1") (pinfunction "1_1") (pintype "passive"))
      (node (ref "U25") (pin "A1") (pinfunction "OUT+_A1") (pintype "bidirectional"))
    )
    (net (code "230") (name "Net-(U25-OUT-)") (class "Default")
      (node (ref "C114") (pin "1") (pinfunction "1_1") (pintype "passive"))
      (node (ref "U25") (pin "B1") (pinfunction "OUT-_B1") (pintype "bidirectional"))
    )
    (net (code "231") (name "Net-(U26-FB)") (class "Default")
      (node (ref "R77") (pin "1") (pinfunction "1_1") (pintype "passive"))
      (node (ref "R78") (pin "2") (pinfunction "2_2") (pintype "passive"))
      (node (ref "U26") (pin "3") (pinfunction "FB_3") (pintype "input"))
    )
    (net (code "232") (name "Net-(U26-SW)") (class "Default")
      (node (ref "L26") (pin "2") (pinfunction "2_2") (pintype "passive"))
      (node (ref "U26") (pin "1") (pinfunction "SW_1") (pintype "output"))
    )
    (net (code "233") (name "Net-(U29-GAIN)") (class "Default")
      (node (ref "SJ30") (pin "2") (pinfunction "2_2") (pintype "passive"))
      (node (ref "U29") (pin "B2") (pinfunction "GAIN_B2") (pintype "bidirectional"))
    )
    (net (code "234") (name "Net-(U29-IN+)") (class "Default")
      (node (ref "C127") (pin "2") (pinfunction "2_2") (pintype "passive"))
      (node (ref "U29") (pin "A3") (pinfunction "IN+_A3") (pintype "bidirectional"))
    )
    (net (code "235") (name "Net-(U29-IN-)") (class "Default")
      (node (ref "C128") (pin "2") (pinfunction "2_2") (pintype "passive"))
      (node (ref "U29") (pin "B3") (pinfunction "IN-_B3") (pintype "bidirectional"))
    )
    (net (code "236") (name "Net-(U29-OUT+)") (class "Default")
      (node (ref "C131") (pin "1") (pinfunction "1_1") (pintype "passive"))
      (node (ref "U29") (pin "A1") (pinfunction "OUT+_A1") (pintype "bidirectional"))
    )
    (net (code "237") (name "Net-(U29-OUT-)") (class "Default")
      (node (ref "C132") (pin "1") (pinfunction "1_1") (pintype "passive"))
      (node (ref "U29") (pin "B1") (pinfunction "OUT-_B1") (pintype "bidirectional"))
    )
    (net (code "238") (name "Net-(U30-FB)") (class "Default")
      (node (ref "R89") (pin "1") (pinfunction "1_1") (pintype "passive"))
      (node (ref "R90") (pin "2") (pinfunction "2_2") (pintype "passive"))
      (node (ref "U30") (pin "3") (pinfunction "FB_3") (pintype "input"))
    )
    (net (code "239") (name "Net-(U30-SW)") (class "Default")
      (node (ref "L30") (pin "2") (pinfunction "2_2") (pintype "passive"))
      (node (ref "U30") (pin "1") (pinfunction "SW_1") (pintype "output"))
    )
    (net (code "240") (name "Net-(U31-GAIN)") (class "Default")
      (node (ref "SJ32") (pin "2") (pinfunction "2_2") (pintype "passive"))
      (node (ref "U31") (pin "B2") (pinfunction "GAIN_B2") (pintype "bidirectional"))
    )
    (net (code "241") (name "Net-(U31-IN+)") (class "Default")
      (node (ref "C136") (pin "2") (pinfunction "2_2") (pintype "passive"))
      (node (ref "U31") (pin "A3") (pinfunction "IN+_A3") (pintype "bidirectional"))
    )
    (net (code "242") (name "Net-(U31-IN-)") (class "Default")
      (node (ref "C137") (pin "2") (pinfunction "2_2") (pintype "passive"))
      (node (ref "U31") (pin "B3") (pinfunction "IN-_B3") (pintype "bidirectional"))
    )
    (net (code "243") (name "Net-(U31-OUT+)") (class "Default")
      (node (ref "C140") (pin "1") (pinfunction "1_1") (pintype "passive"))
      (node (ref "U31") (pin "A1") (pinfunction "OUT+_A1") (pintype "bidirectional"))
    )
    (net (code "244") (name "Net-(U31-OUT-)") (class "Default")
      (node (ref "C141") (pin "1") (pinfunction "1_1") (pintype "passive"))
      (node (ref "U31") (pin "B1") (pinfunction "OUT-_B1") (pintype "bidirectional"))
    )
    (net (code "245") (name "Net-(U32-FB)") (class "Default")
      (node (ref "R95") (pin "1") (pinfunction "1_1") (pintype "passive"))
      (node (ref "R96") (pin "2") (pinfunction "2_2") (pintype "passive"))
      (node (ref "U32") (pin "3") (pinfunction "FB_3") (pintype "input"))
    )
    (net (code "246") (name "Net-(U32-SW)") (class "Default")
      (node (ref "L32") (pin "2") (pinfunction "2_2") (pintype "passive"))
      (node (ref "U32") (pin "1") (pinfunction "SW_1") (pintype "output"))
    )
    (net (code "247") (name "Net-(U35-GAIN)") (class "Default")
      (node (ref "SJ36") (pin "2") (pinfunction "2_2") (pintype "passive"))
      (node (ref "U35") (pin "B2") (pinfunction "GAIN_B2") (pintype "bidirectional"))
    )
    (net (code "248") (name "Net-(U35-IN+)") (class "Default")
      (node (ref "C154") (pin "2") (pinfunction "2_2") (pintype "passive"))
      (node (ref "U35") (pin "A3") (pinfunction "IN+_A3") (pintype "bidirectional"))
    )
    (net (code "249") (name "Net-(U35-IN-)") (class "Default")
      (node (ref "C155") (pin "2") (pinfunction "2_2") (pintype "passive"))
      (node (ref "U35") (pin "B3") (pinfunction "IN-_B3") (pintype "bidirectional"))
    )
    (net (code "250") (name "Net-(U35-OUT+)") (class "Default")
      (node (ref "C158") (pin "1") (pinfunction "1_1") (pintype "passive"))
      (node (ref "U35") (pin "A1") (pinfunction "OUT+_A1") (pintype "bidirectional"))
    )
    (net (code "251") (name "Net-(U35-OUT-)") (class "Default")
      (node (ref "C159") (pin "1") (pinfunction "1_1") (pintype "passive"))
      (node (ref "U35") (pin "B1") (pinfunction "OUT-_B1") (pintype "bidirectional"))
    )
    (net (code "252") (name "Net-(U36-FB)") (class "Default")
      (node (ref "R107") (pin "1") (pinfunction "1_1") (pintype "passive"))
      (node (ref "R108") (pin "2") (pinfunction "2_2") (pintype "passive"))
      (node (ref "U36") (pin "3") (pinfunction "FB_3") (pintype "input"))
    )
    (net (code "253") (name "Net-(U36-SW)") (class "Default")
      (node (ref "L36") (pin "2") (pinfunction "2_2") (pintype "passive"))
      (node (ref "U36") (pin "1") (pinfunction "SW_1") (pintype "output"))
    )
    (net (code "254") (name "Net-(U39-GAIN)") (class "Default")
      (node (ref "SJ40") (pin "2") (pinfunction "2_2") (pintype "passive"))
      (node (ref "U39") (pin "B2") (pinfunction "GAIN_B2") (pintype "bidirectional"))
    )
    (net (code "255") (name "Net-(U39-IN+)") (class "Default")
      (node (ref "C172") (pin "2") (pinfunction "2_2") (pintype "passive"))
      (node (ref "U39") (pin "A3") (pinfunction "IN+_A3") (pintype "bidirectional"))
    )
    (net (code "256") (name "Net-(U39-IN-)") (class "Default")
      (node (ref "C173") (pin "2") (pinfunction "2_2") (pintype "passive"))
      (node (ref "U39") (pin "B3") (pinfunction "IN-_B3") (pintype "bidirectional"))
    )
    (net (code "257") (name "Net-(U39-OUT+)") (class "Default")
      (node (ref "C176") (pin "1") (pinfunction "1_1") (pintype "passive"))
      (node (ref "U39") (pin "A1") (pinfunction "OUT+_A1") (pintype "bidirectional"))
    )
    (net (code "258") (name "Net-(U39-OUT-)") (class "Default")
      (node (ref "C177") (pin "1") (pinfunction "1_1") (pintype "passive"))
      (node (ref "U39") (pin "B1") (pinfunction "OUT-_B1") (pintype "bidirectional"))
    )
    (net (code "259") (name "Net-(U40-FB)") (class "Default")
      (node (ref "R119") (pin "1") (pinfunction "1_1") (pintype "passive"))
      (node (ref "R120") (pin "2") (pinfunction "2_2") (pintype "passive"))
      (node (ref "U40") (pin "3") (pinfunction "FB_3") (pintype "input"))
    )
    (net (code "260") (name "Net-(U40-SW)") (class "Default")
      (node (ref "L40") (pin "2") (pinfunction "2_2") (pintype "passive"))
      (node (ref "U40") (pin "1") (pinfunction "SW_1") (pintype "output"))
    )
    (net (code "261") (name "Net-(U43-GAIN)") (class "Default")
      (node (ref "SJ44") (pin "2") (pinfunction "2_2") (pintype "passive"))
      (node (ref "U43") (pin "B2") (pinfunction "GAIN_B2") (pintype "bidirectional"))
    )
    (net (code "262") (name "Net-(U43-IN+)") (class "Default")
      (node (ref "C190") (pin "2") (pinfunction "2_2") (pintype "passive"))
      (node (ref "U43") (pin "A3") (pinfunction "IN+_A3") (pintype "bidirectional"))
    )
    (net (code "263") (name "Net-(U43-IN-)") (class "Default")
      (node (ref "C191") (pin "2") (pinfunction "2_2") (pintype "passive"))
      (node (ref "U43") (pin "B3") (pinfunction "IN-_B3") (pintype "bidirectional"))
    )
    (net (code "264") (name "Net-(U43-OUT+)") (class "Default")
      (node (ref "C194") (pin "1") (pinfunction "1_1") (pintype "passive"))
      (node (ref "U43") (pin "A1") (pinfunction "OUT+_A1") (pintype "bidirectional"))
    )
    (net (code "265") (name "Net-(U43-OUT-)") (class "Default")
      (node (ref "C195") (pin "1") (pinfunction "1_1") (pintype "passive"))
      (node (ref "U43") (pin "B1") (pinfunction "OUT-_B1") (pintype "bidirectional"))
    )
    (net (code "266") (name "Net-(U44-FB)") (class "Default")
      (node (ref "R131") (pin "1") (pinfunction "1_1") (pintype "passive"))
      (node (ref "R132") (pin "2") (pinfunction "2_2") (pintype "passive"))
      (node (ref "U44") (pin "3") (pinfunction "FB_3") (pintype "input"))
    )
    (net (code "267") (name "Net-(U44-SW)") (class "Default")
      (node (ref "L44") (pin "2") (pinfunction "2_2") (pintype "passive"))
      (node (ref "U44") (pin "1") (pinfunction "SW_1") (pintype "output"))
    )
    (net (code "268") (name "Net-(U47-GAIN)") (class "Default")
      (node (ref "SJ48") (pin "2") (pinfunction "2_2") (pintype "passive"))
      (node (ref "U47") (pin "B2") (pinfunction "GAIN_B2") (pintype "bidirectional"))
    )
    (net (code "269") (name "Net-(U47-IN+)") (class "Default")
      (node (ref "C208") (pin "2") (pinfunction "2_2") (pintype "passive"))
      (node (ref "U47") (pin "A3") (pinfunction "IN+_A3") (pintype "bidirectional"))
    )
    (net (code "270") (name "Net-(U47-IN-)") (class "Default")
      (node (ref "C209") (pin "2") (pinfunction "2_2") (pintype "passive"))
      (node (ref "U47") (pin "B3") (pinfunction "IN-_B3") (pintype "bidirectional"))
    )
    (net (code "271") (name "Net-(U47-OUT+)") (class "Default")
      (node (ref "C212") (pin "1") (pinfunction "1_1") (pintype "passive"))
      (node (ref "U47") (pin "A1") (pinfunction "OUT+_A1") (pintype "bidirectional"))
    )
    (net (code "272") (name "Net-(U47-OUT-)") (class "Default")
      (node (ref "C213") (pin "1") (pinfunction "1_1") (pintype "passive"))
      (node (ref "U47") (pin "B1") (pinfunction "OUT-_B1") (pintype "bidirectional"))
    )
    (net (code "273") (name "Net-(U48-FB)") (class "Default")
      (node (ref "R143") (pin "1") (pinfunction "1_1") (pintype "passive"))
      (node (ref "R144") (pin "2") (pinfunction "2_2") (pintype "passive"))
      (node (ref "U48") (pin "3") (pinfunction "FB_3") (pintype "input"))
    )
    (net (code "274") (name "Net-(U48-SW)") (class "Default")
      (node (ref "L48") (pin "2") (pinfunction "2_2") (pintype "passive"))
      (node (ref "U48") (pin "1") (pinfunction "SW_1") (pintype "output"))
    )
    (net (code "275") (name "unconnected-(JP1-Pad2)") (class "Default")
      (node (ref "JP1") (pin "2") (pinfunction "2_2") (pintype "passive"))
    )
    (net (code "276") (name "unconnected-(JP5-Pad2)") (class "Default")
      (node (ref "JP5") (pin "2") (pinfunction "2_2") (pintype "passive"))
    )
    (net (code "277") (name "unconnected-(JP7-Pad2)") (class "Default")
      (node (ref "JP7") (pin "2") (pinfunction "2_2") (pintype "passive"))
    )
    (net (code "278") (name "unconnected-(JP9-Pad2)") (class "Default")
      (node (ref "JP9") (pin "2") (pinfunction "2_2") (pintype "passive"))
    )
    (net (code "279") (name "unconnected-(JP13-Pad2)") (class "Default")
      (node (ref "JP13") (pin "2") (pinfunction "2_2") (pintype "passive"))
    )
    (net (code "280") (name "unconnected-(JP15-Pad2)") (class "Default")
      (node (ref "JP15") (pin "2") (pinfunction "2_2") (pintype "passive"))
    )
    (net (code "281") (name "unconnected-(JP17-Pad2)") (class "Default")
      (node (ref "JP17") (pin "2") (pinfunction "2_2") (pintype "passive"))
    )
    (net (code "282") (name "unconnected-(JP21-Pad2)") (class "Default")
      (node (ref "JP21") (pin "2") (pinfunction "2_2") (pintype "passive"))
    )
    (net (code "283") (name "unconnected-(JP23-Pad2)") (class "Default")
      (node (ref "JP23") (pin "2") (pinfunction "2_2") (pintype "passive"))
    )
    (net (code "284") (name "unconnected-(JP25-Pad2)") (class "Default")
      (node (ref "JP25") (pin "2") (pinfunction "2_2") (pintype "passive"))
    )
    (net (code "285") (name "unconnected-(JP29-Pad2)") (class "Default")
      (node (ref "JP29") (pin "2") (pinfunction "2_2") (pintype "passive"))
    )
    (net (code "286") (name "unconnected-(JP31-Pad2)") (class "Default")
      (node (ref "JP31") (pin "2") (pinfunction "2_2") (pintype "passive"))
    )
    (net (code "287") (name "unconnected-(JP35-Pad2)") (class "Default")
      (node (ref "JP35") (pin "2") (pinfunction "2_2") (pintype "passive"))
    )
    (net (code "288") (name "unconnected-(JP39-Pad2)") (class "Default")
      (node (ref "JP39") (pin "2") (pinfunction "2_2") (pintype "passive"))
    )
    (net (code "289") (name "unconnected-(JP43-Pad2)") (class "Default")
      (node (ref "JP43") (pin "2") (pinfunction "2_2") (pintype "passive"))
    )
    (net (code "290") (name "unconnected-(JP47-Pad2)") (class "Default")
      (node (ref "JP47") (pin "2") (pinfunction "2_2") (pintype "passive"))
    )
  )
)
